# PCB_KioskMB_r3_3-05.net
KiCad netlist of a schematic drawn in EAGLE
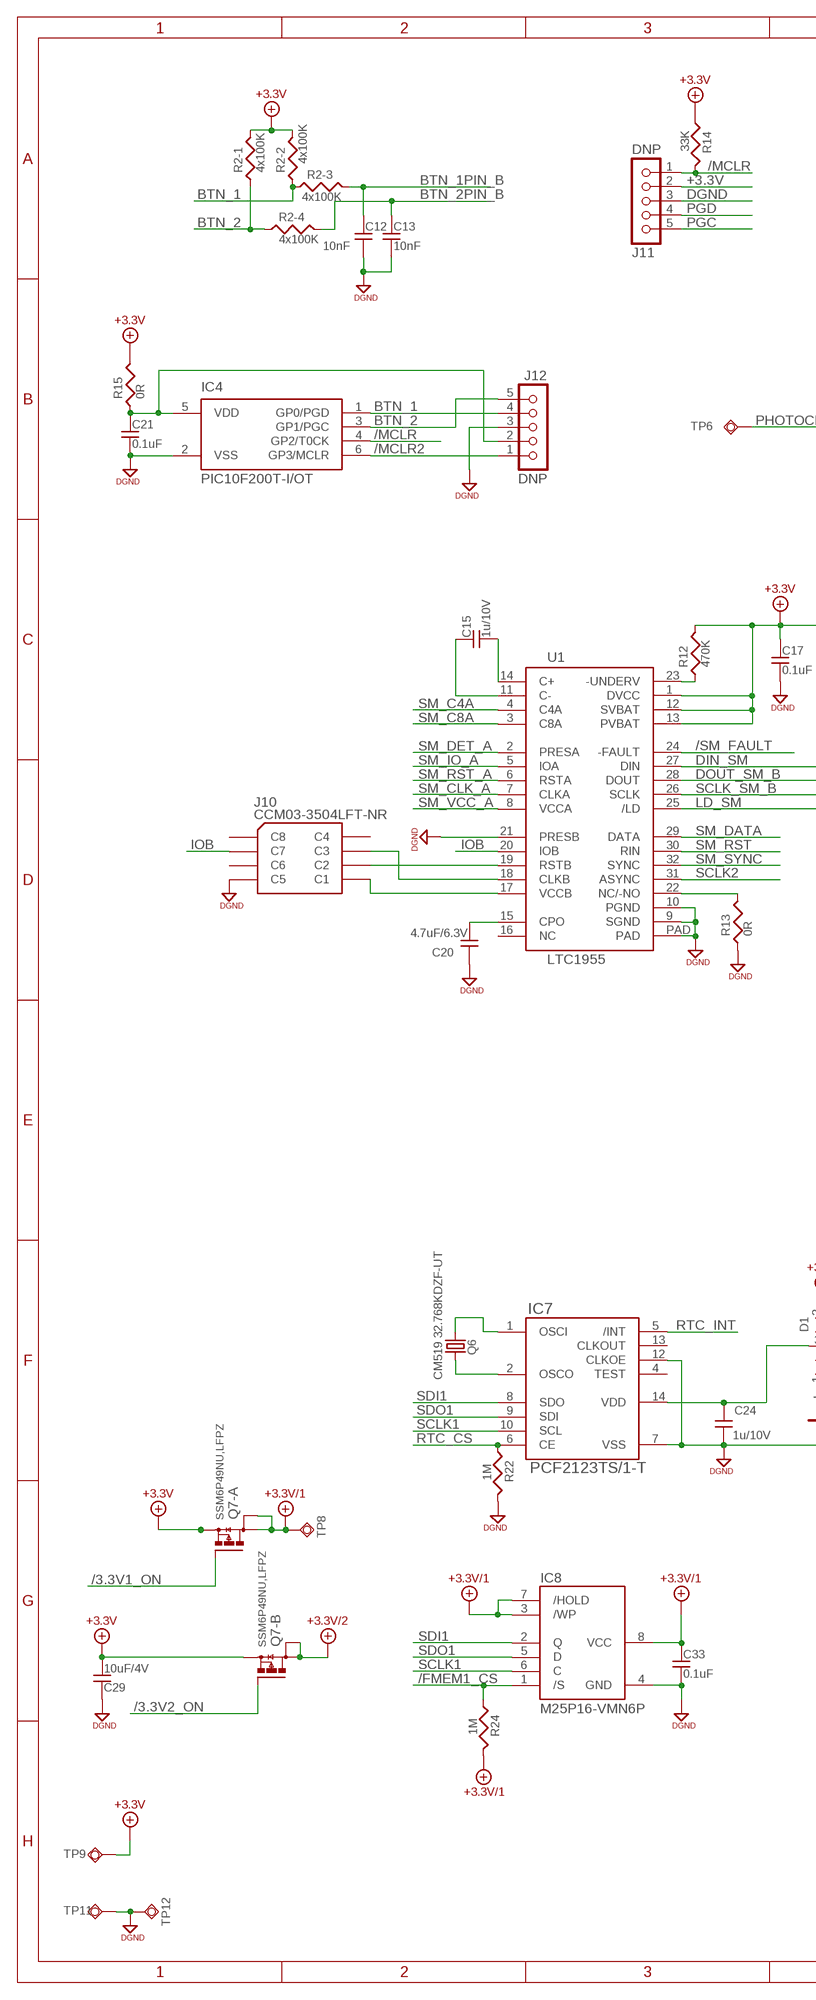
[diagram p0: schematic, sheet 1, part 1 of 2]
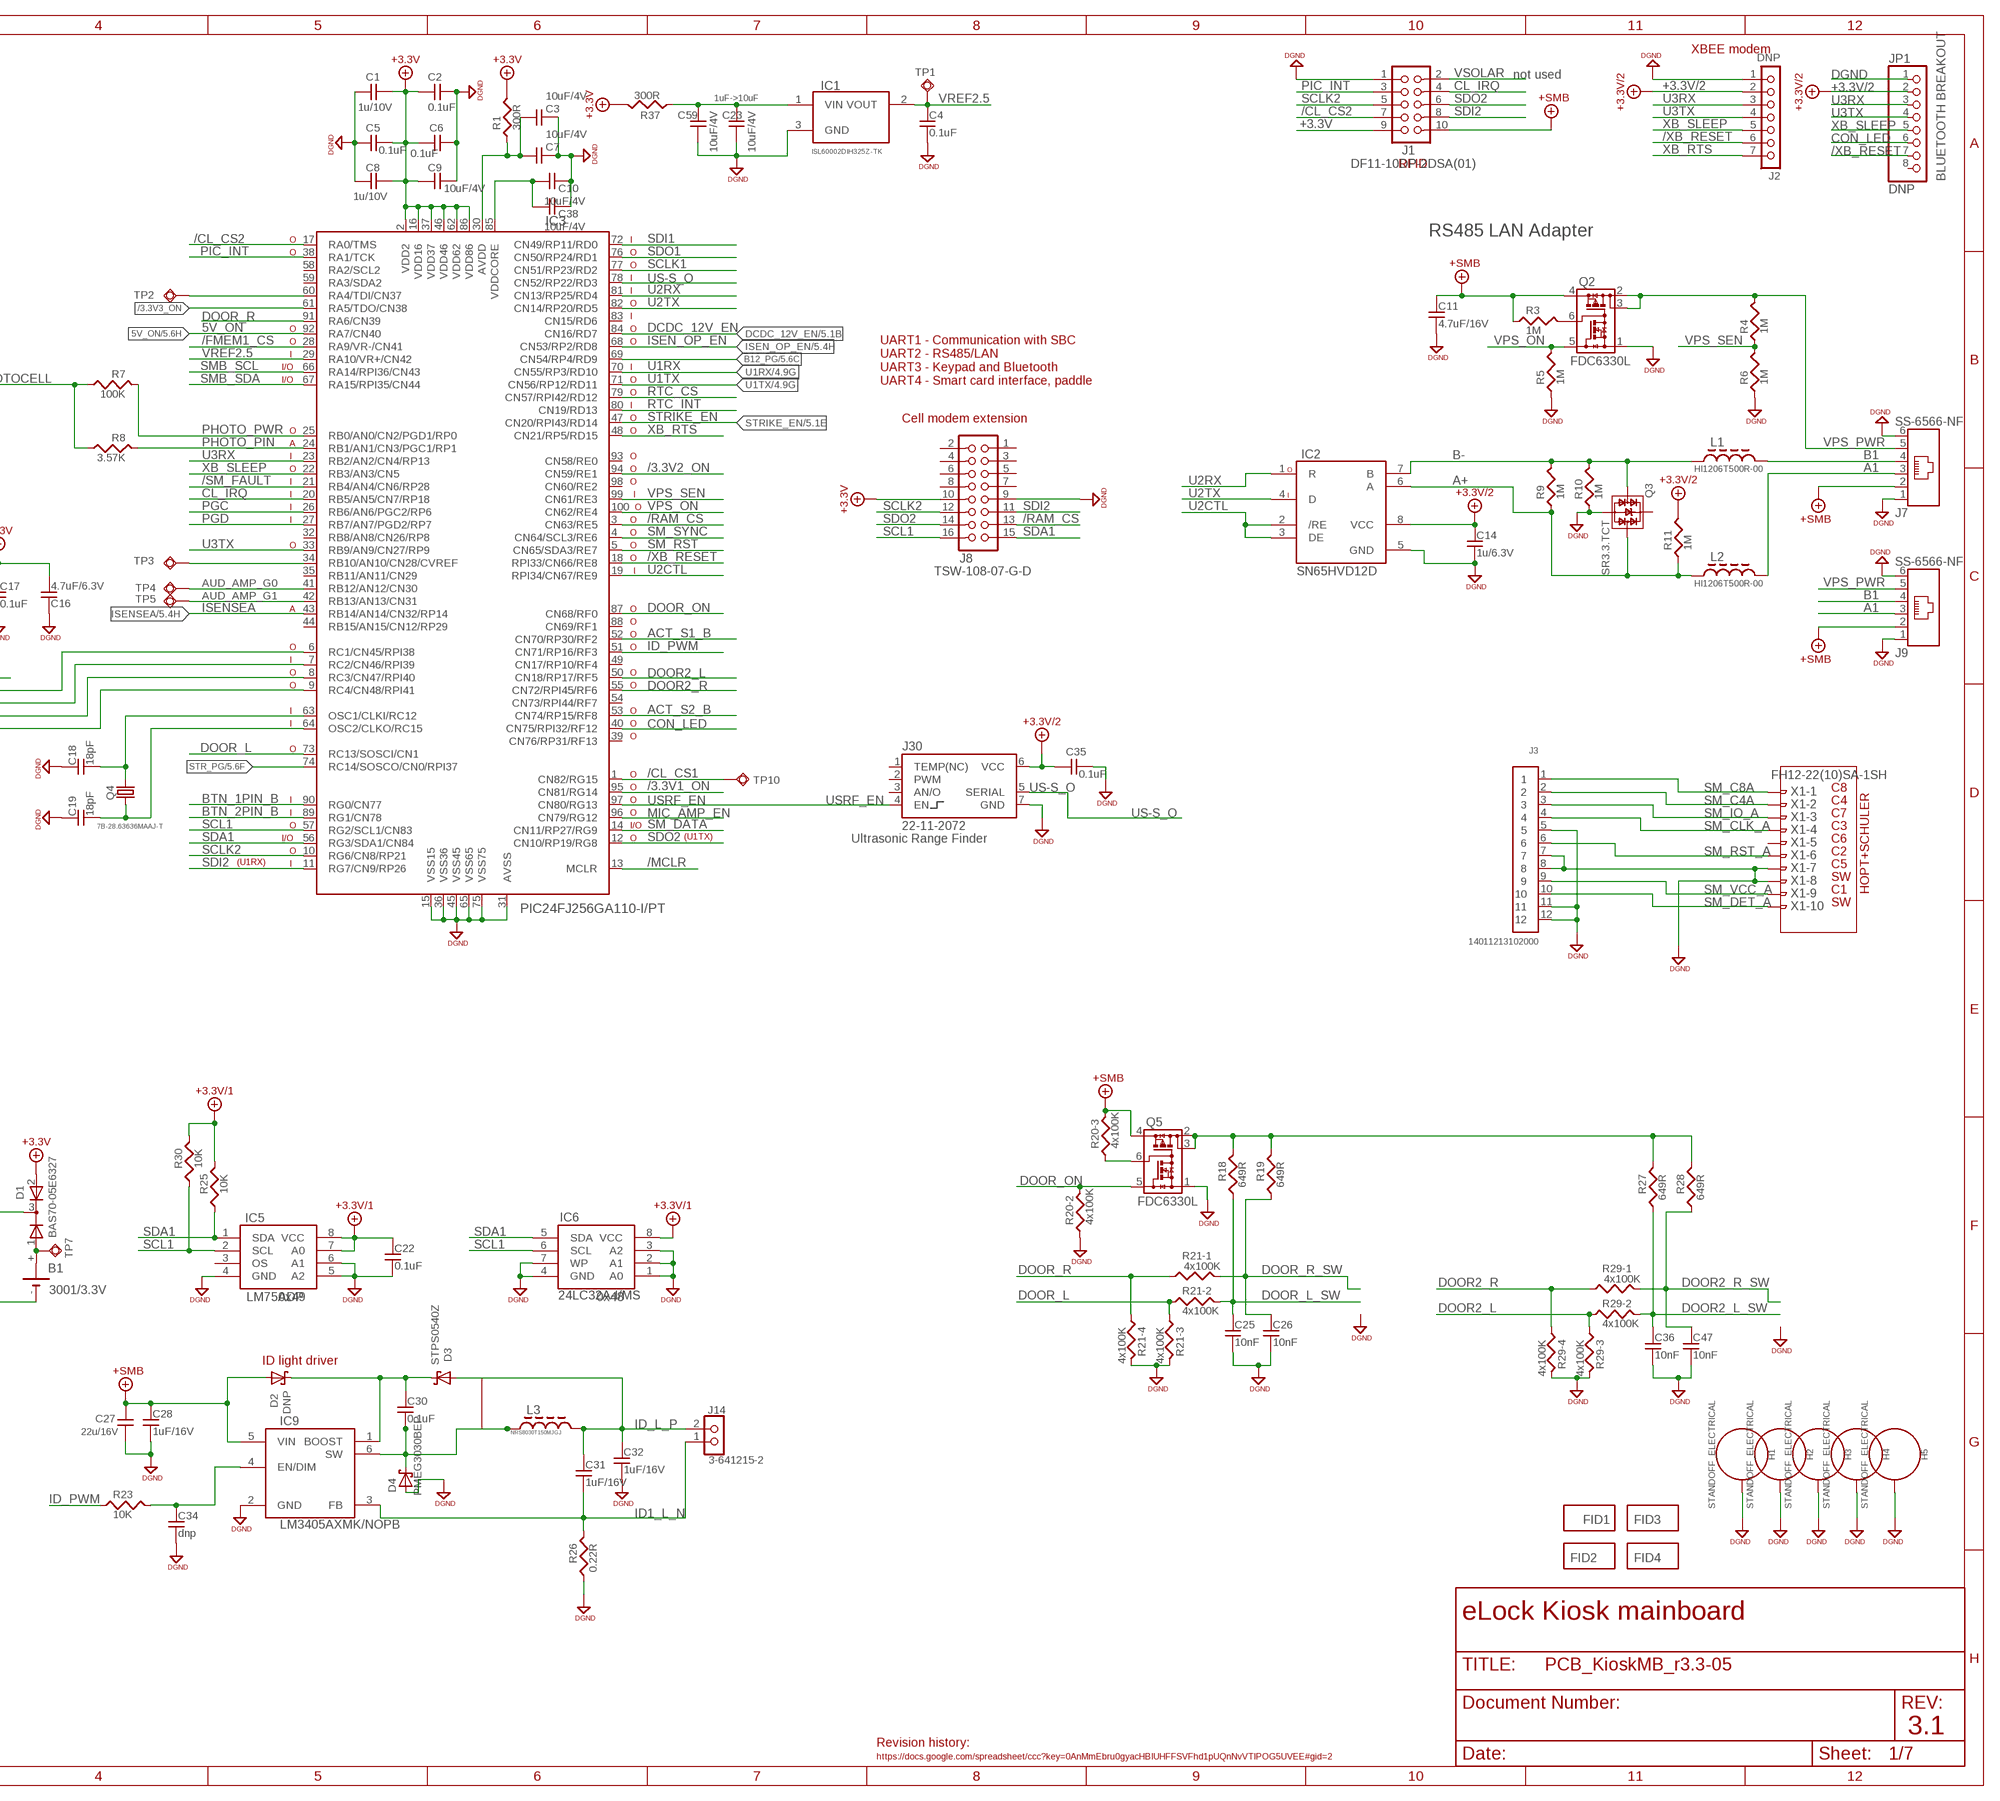
[diagram p1: schematic, sheet 1, part 2 of 2]
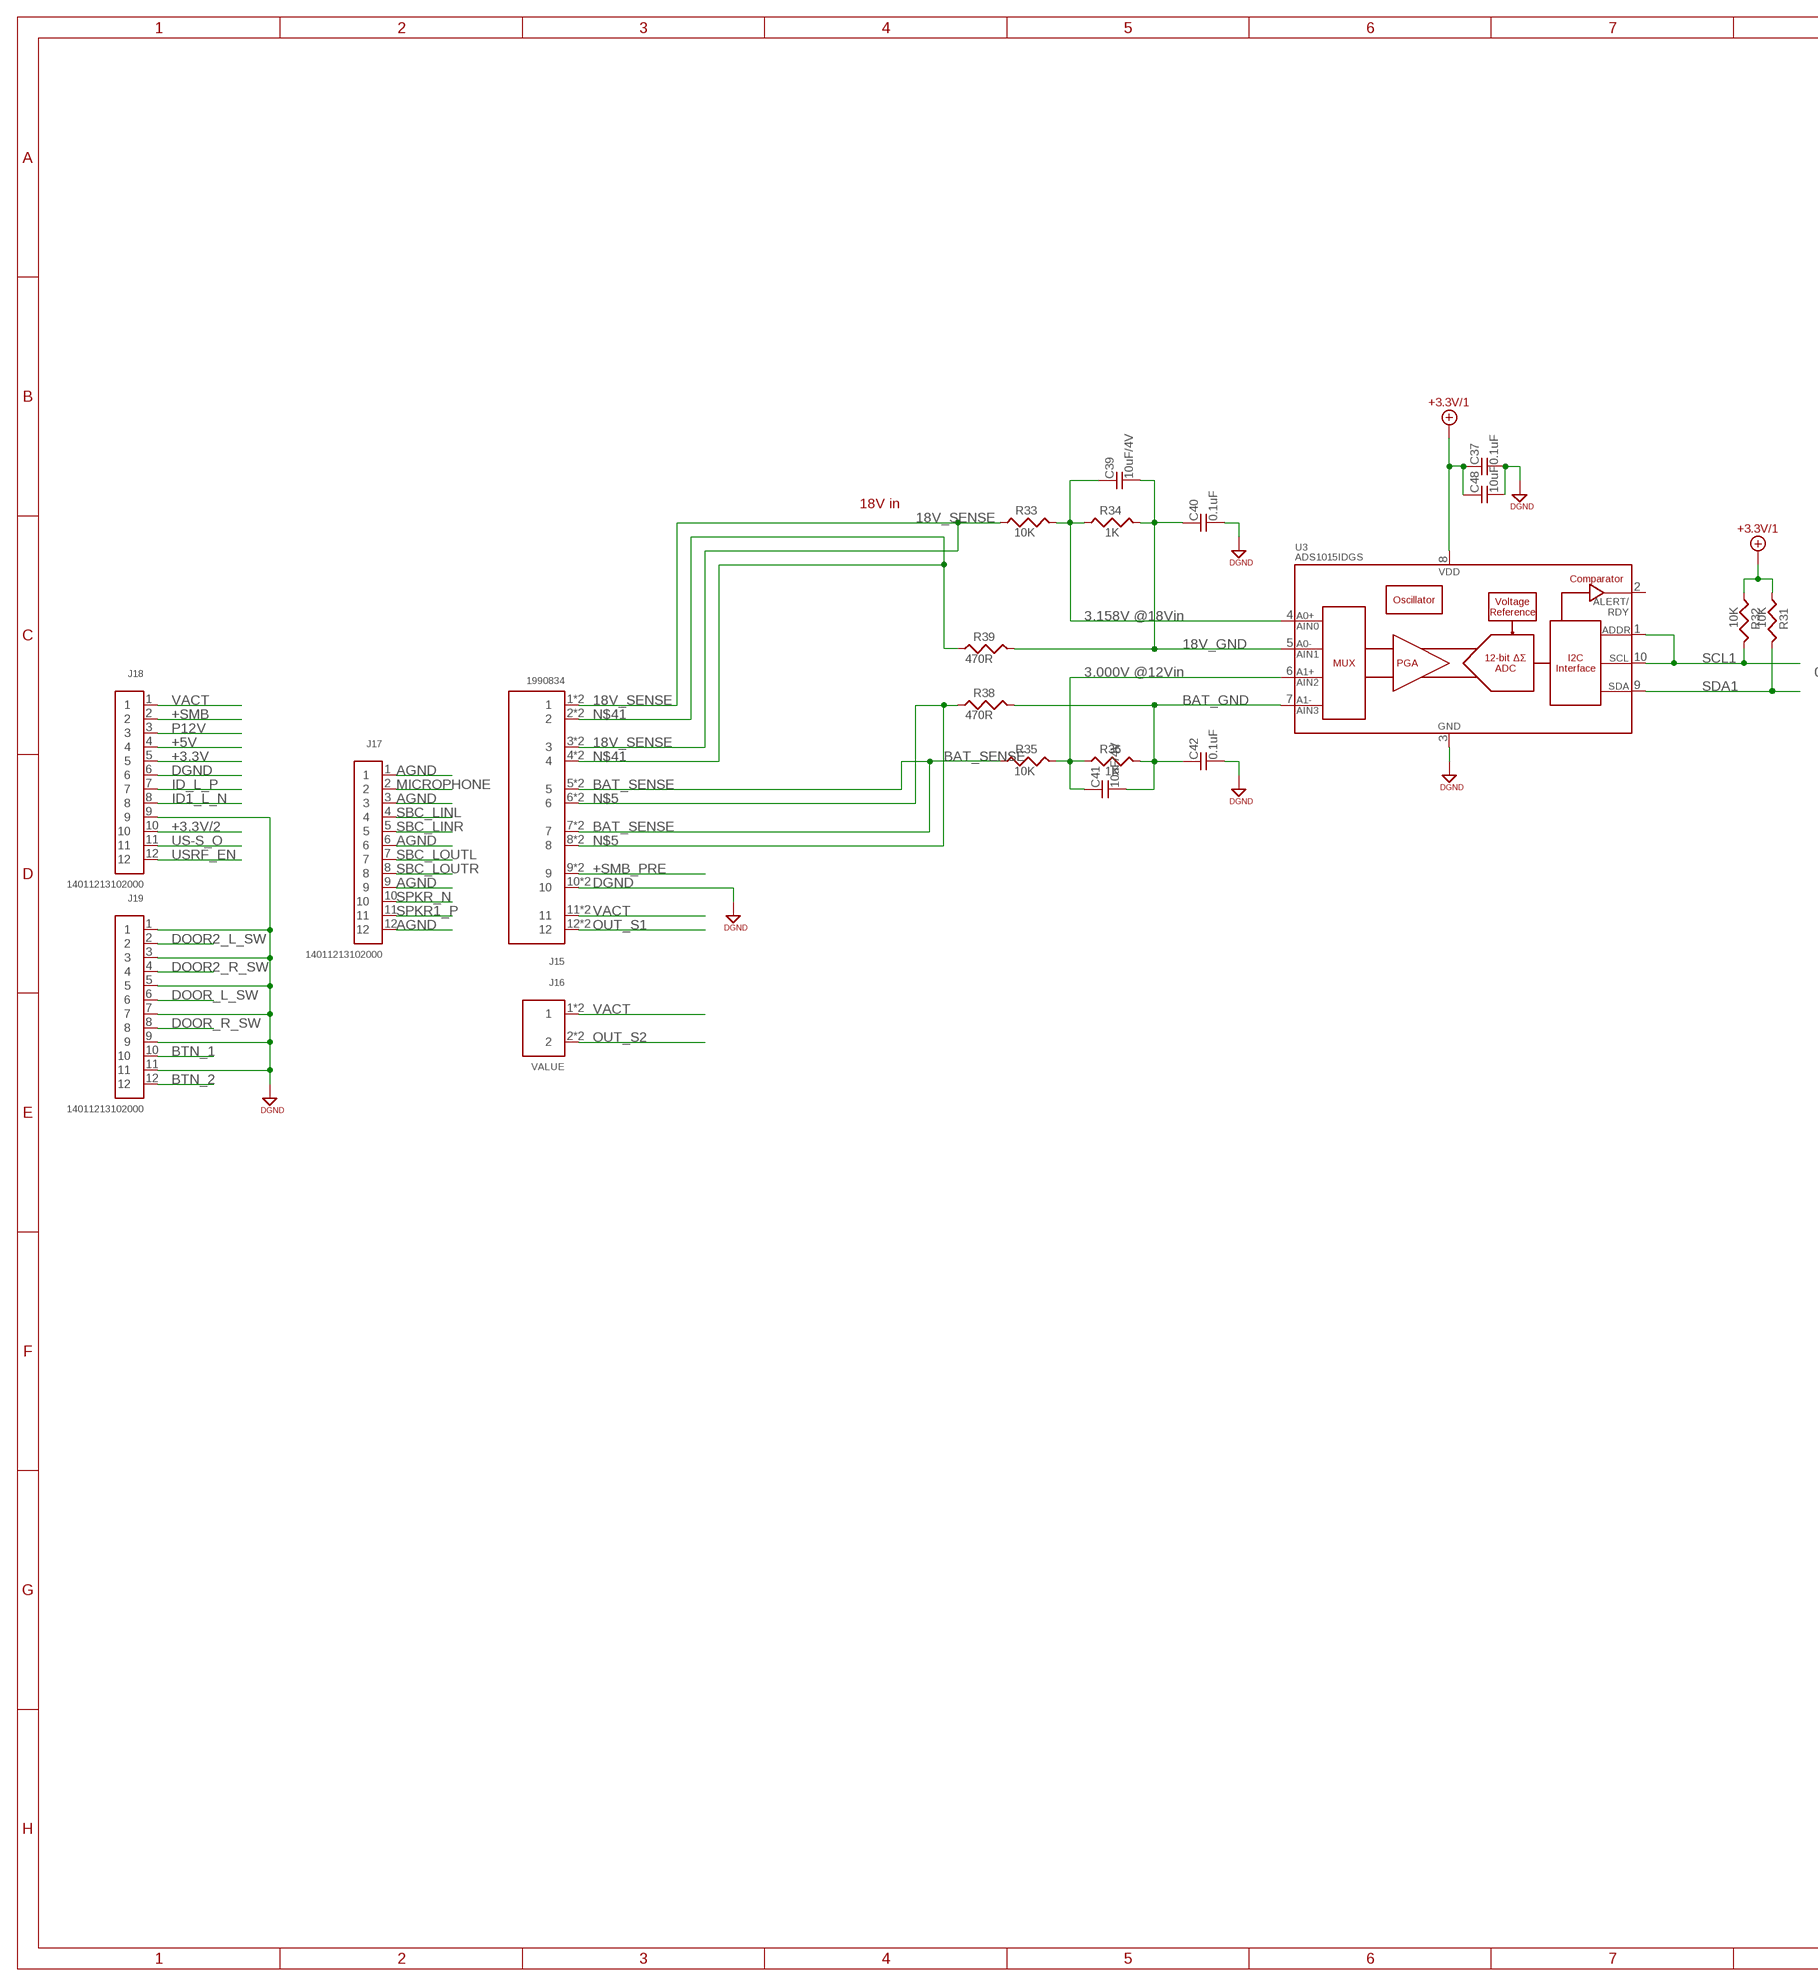
[diagram p2: schematic, sheet 2, part 1 of 2]
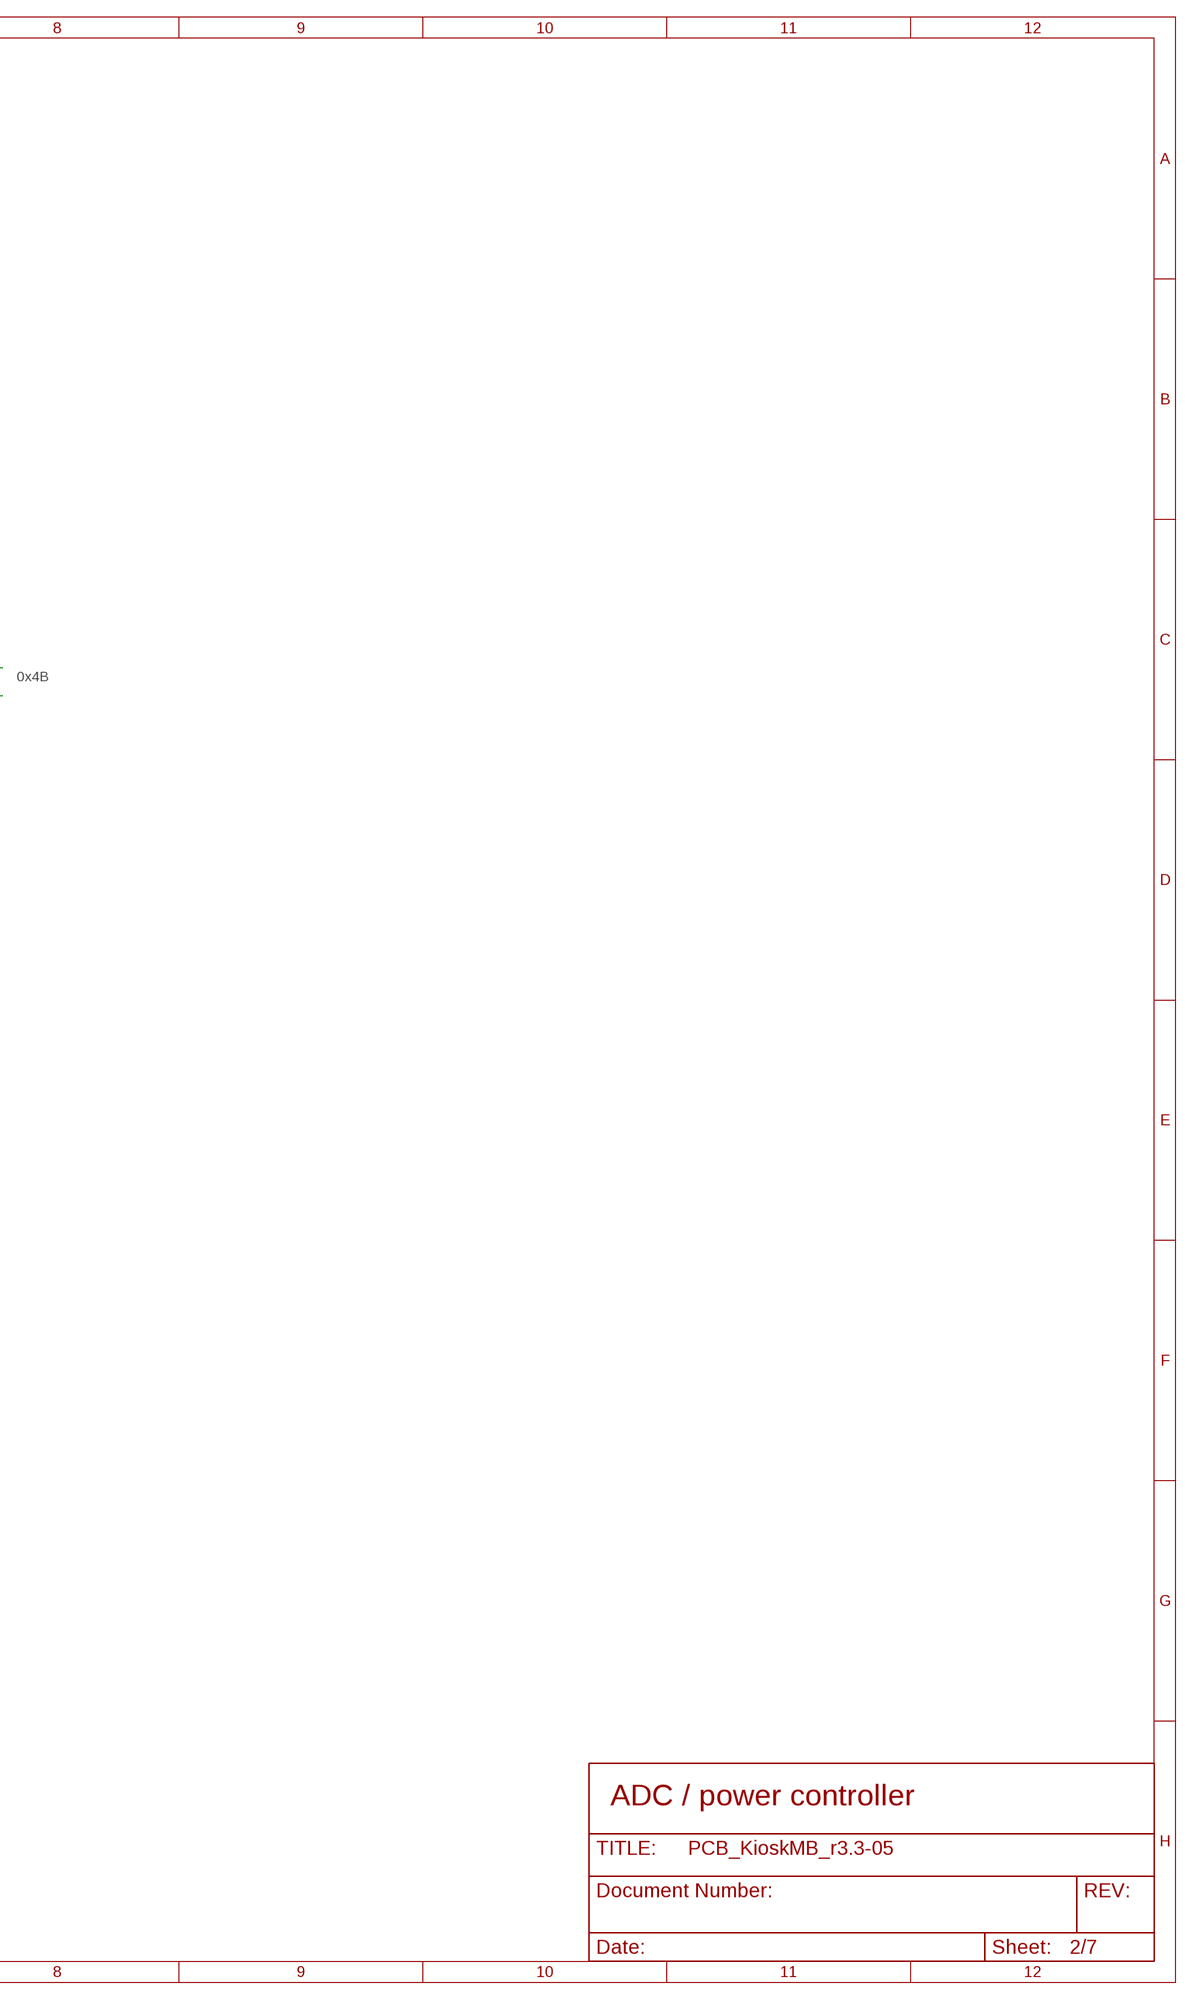
[diagram p3: schematic, sheet 2, part 2 of 2]
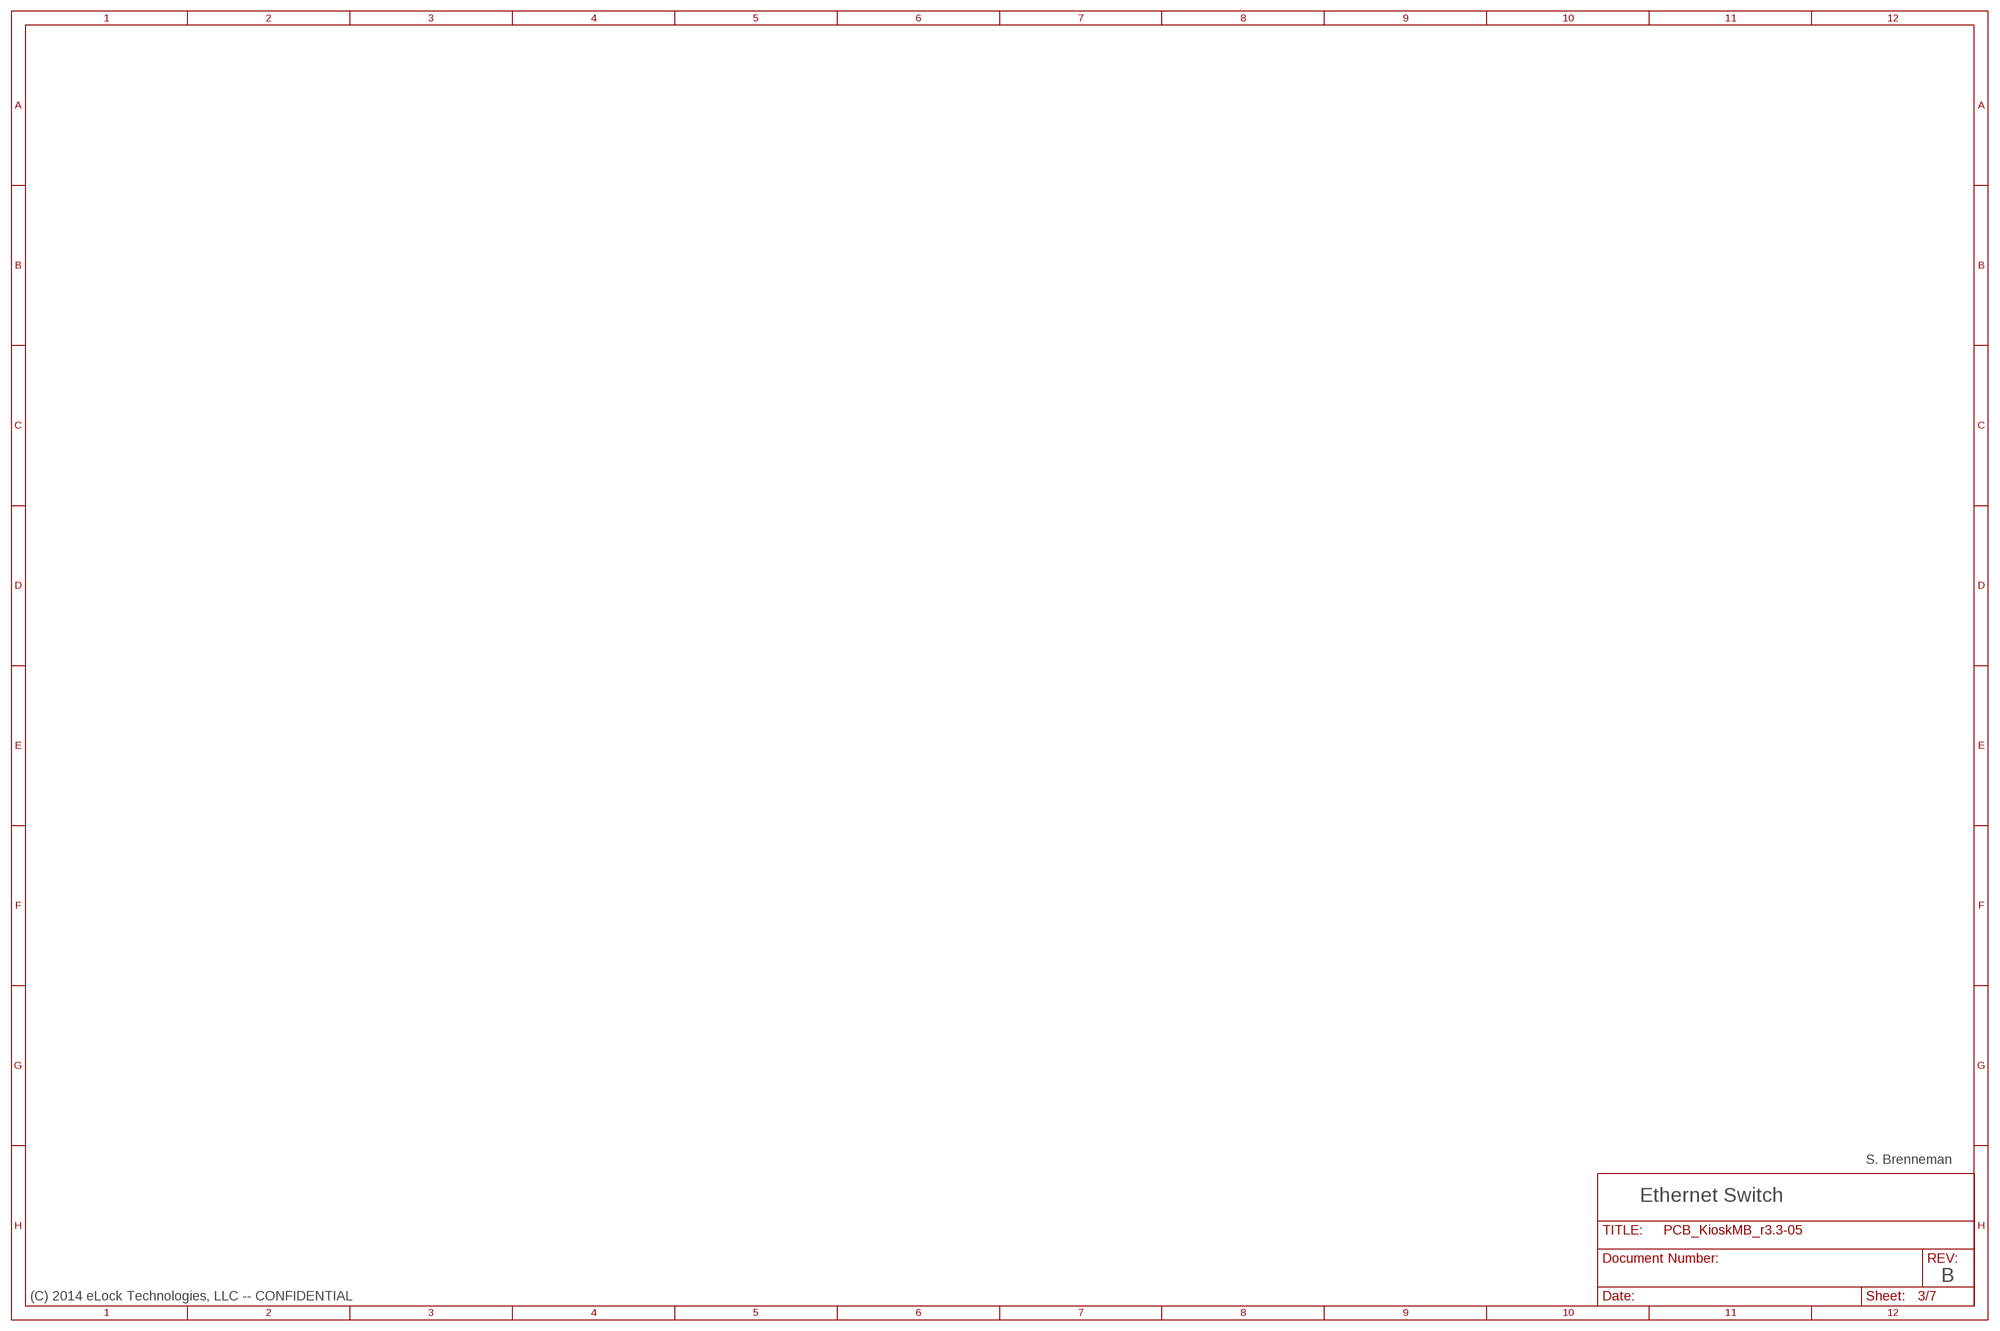
[diagram p4: schematic, sheet 3]
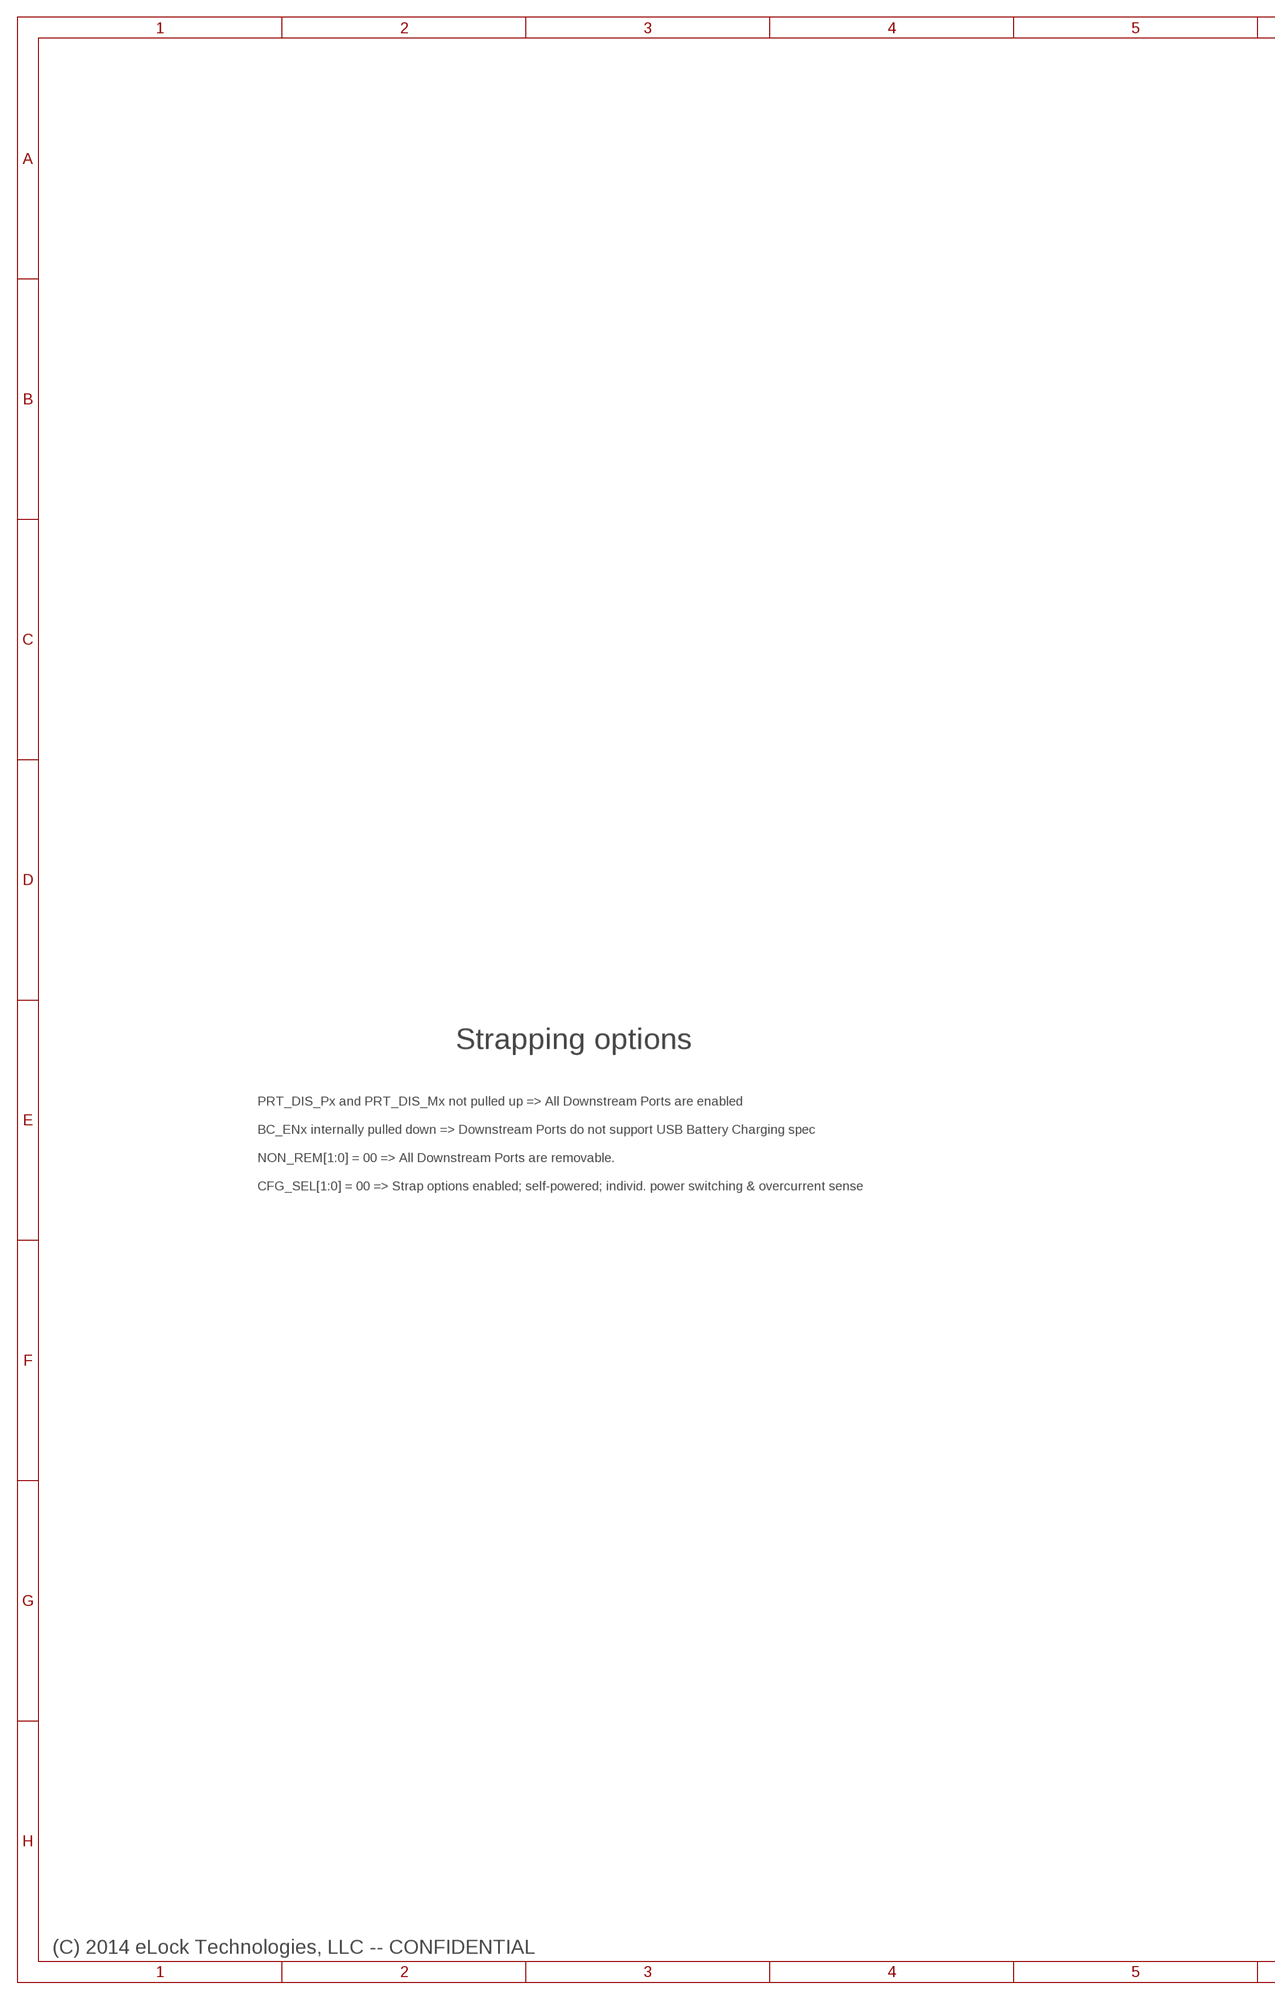
[diagram p5: schematic, sheet 4, part 1 of 2]
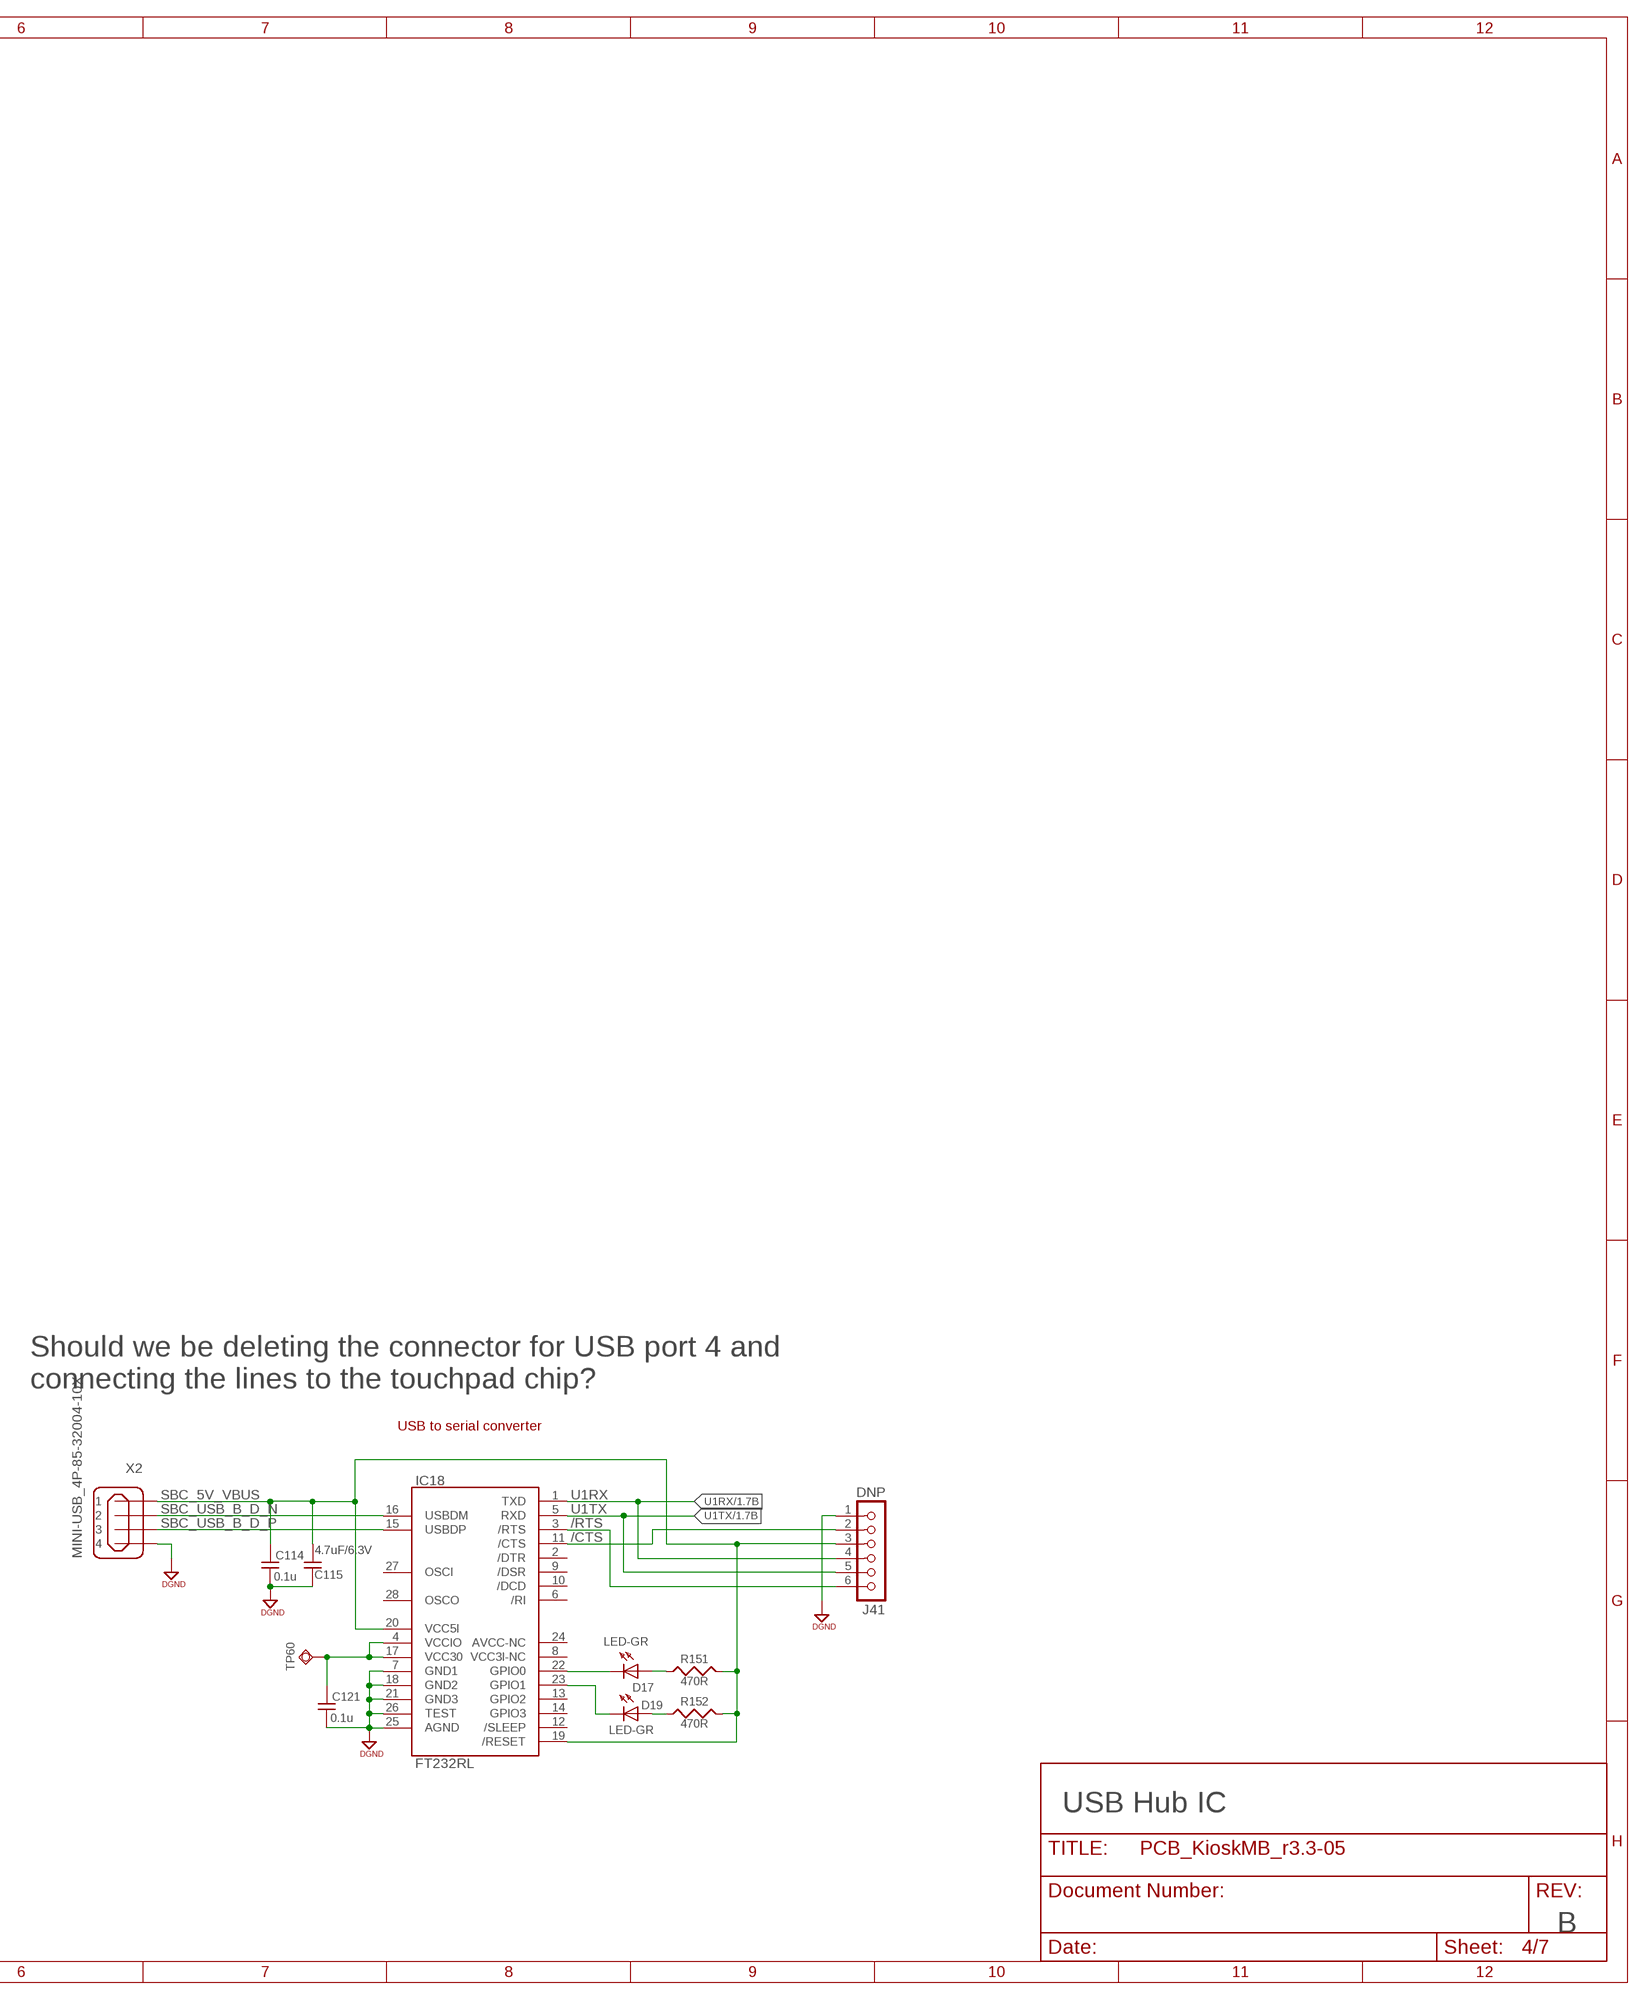
[diagram p6: schematic, sheet 4, part 2 of 2]
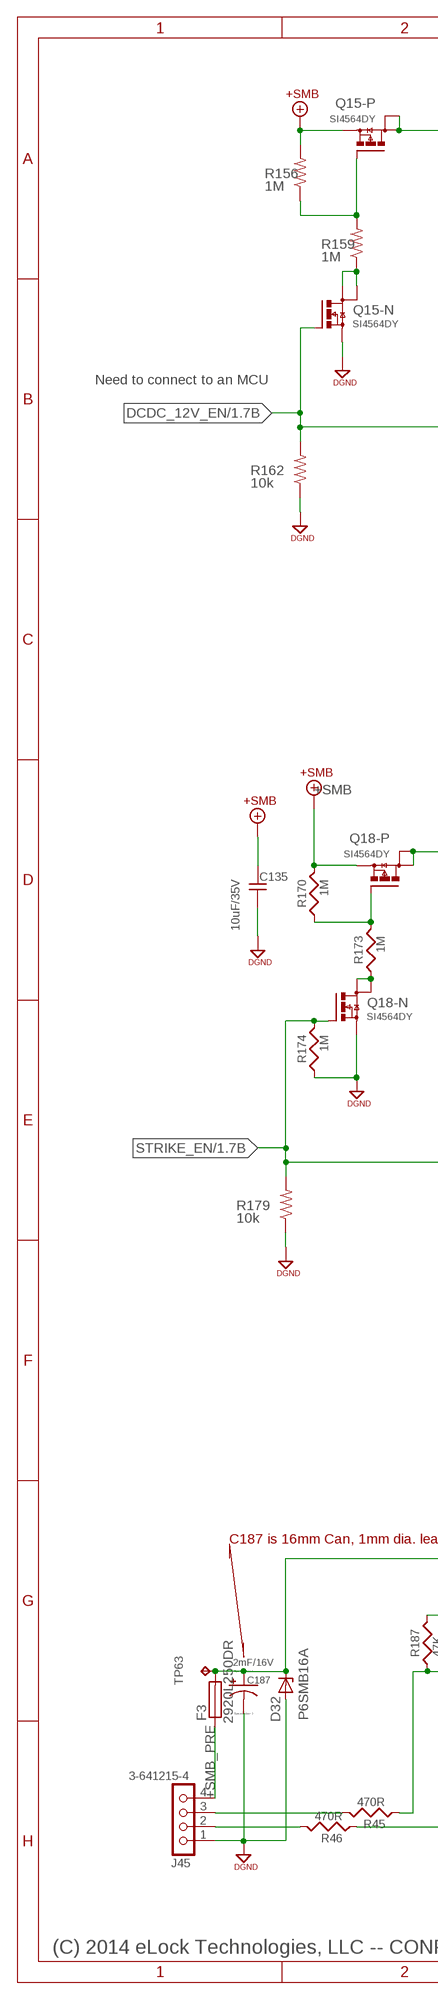
[diagram p7: schematic, sheet 5, part 1 of 2]
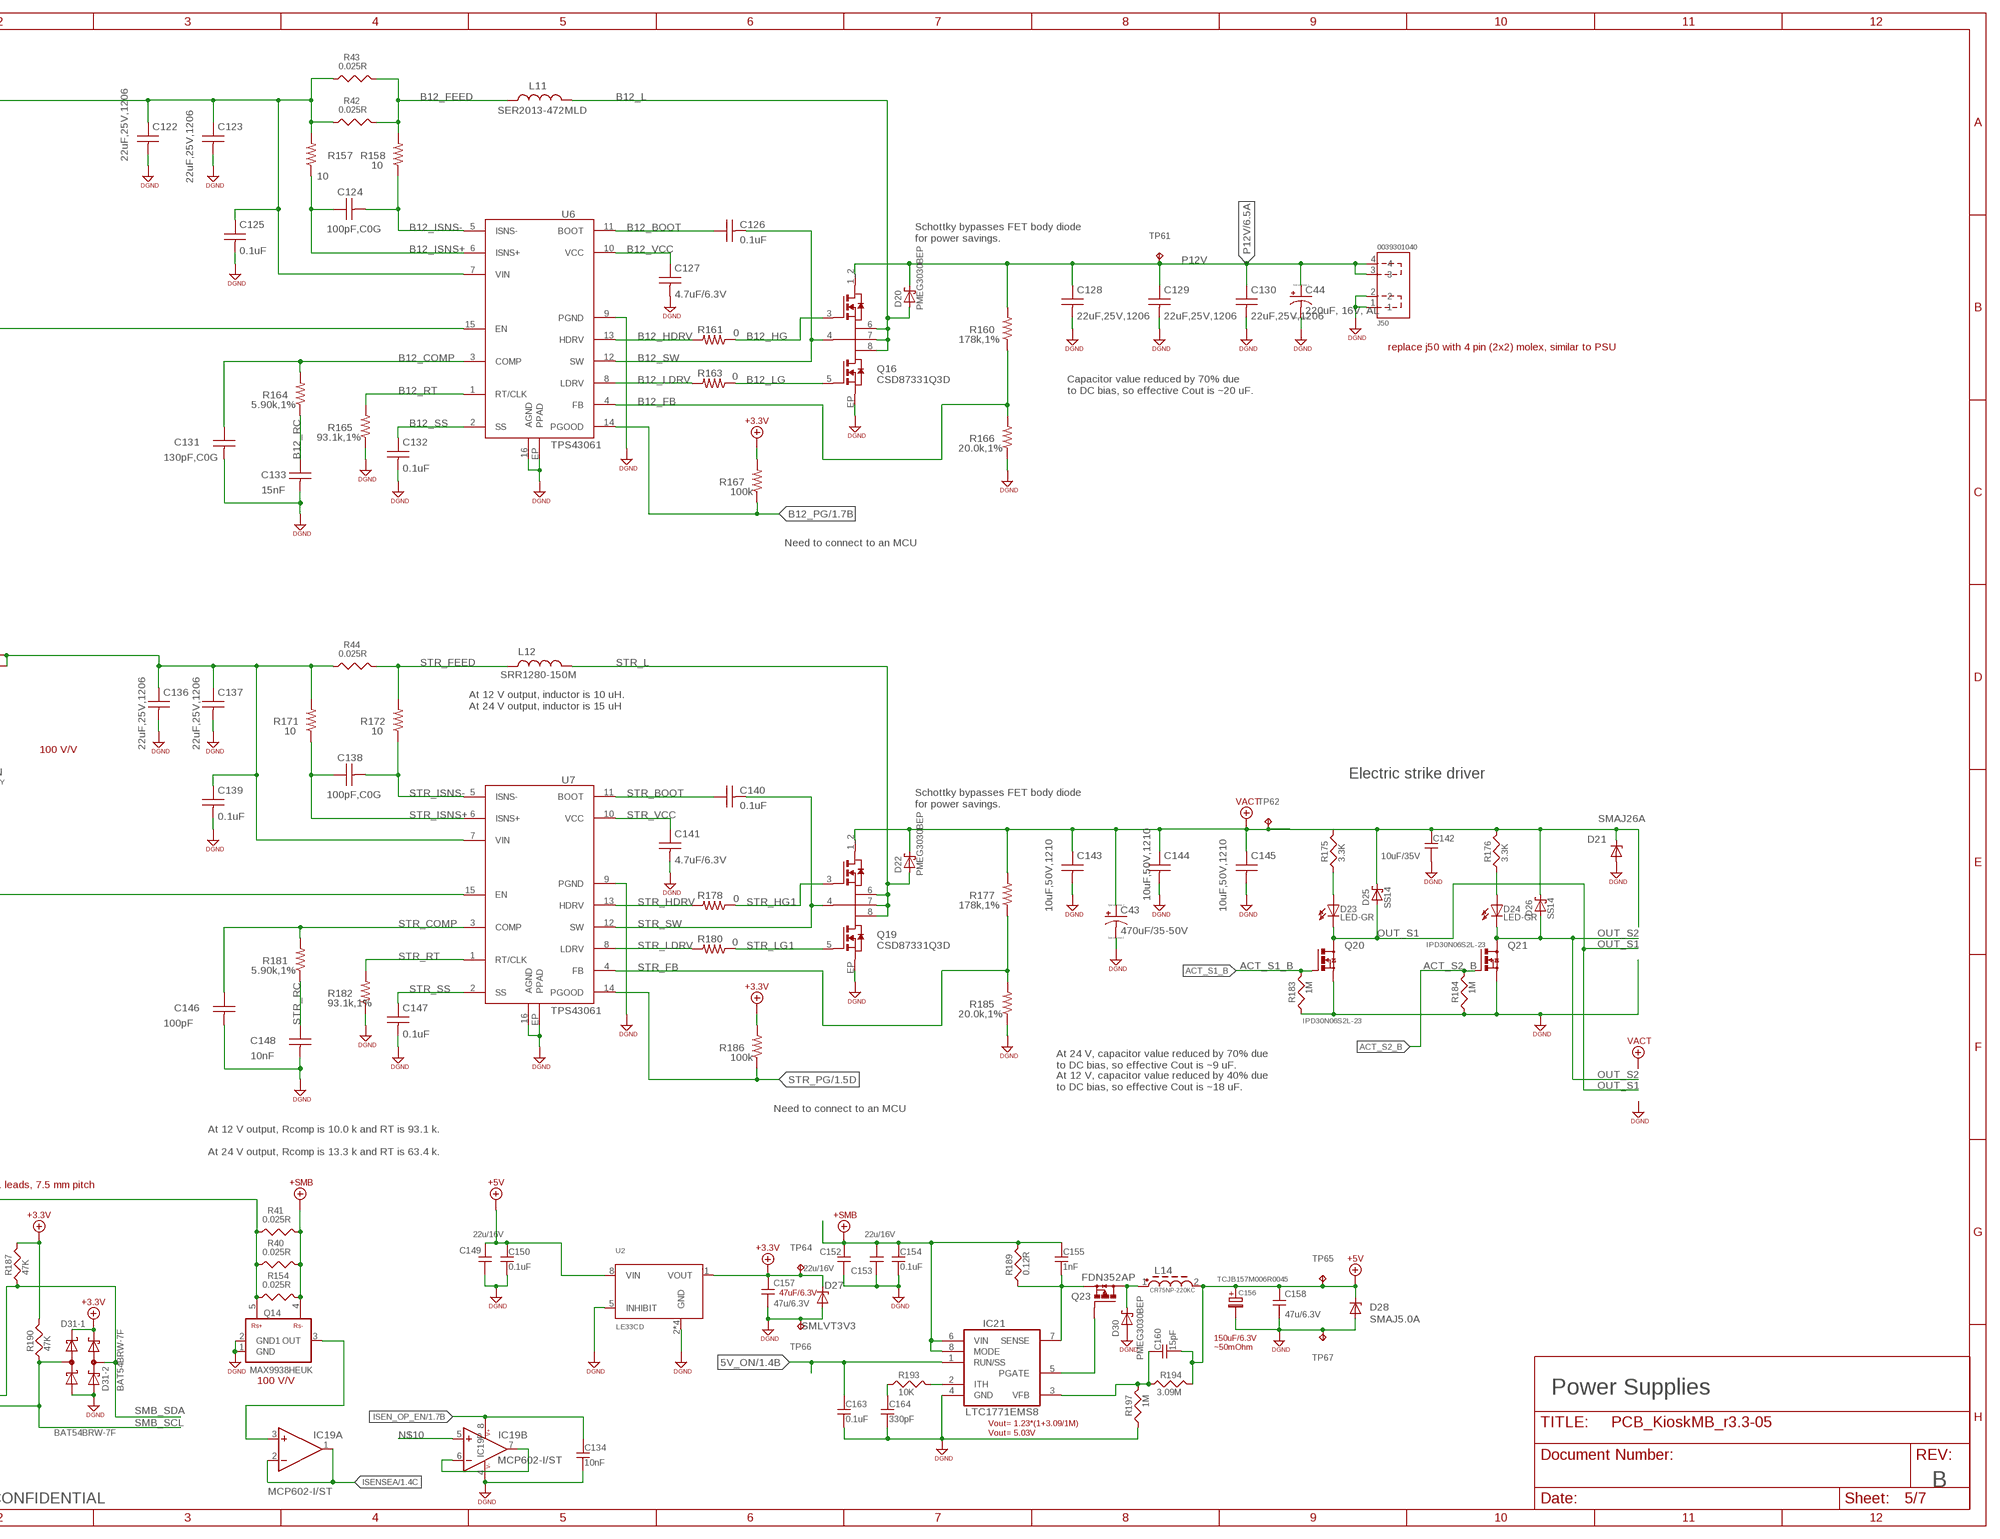
[diagram p8: schematic, sheet 5, part 2 of 2]
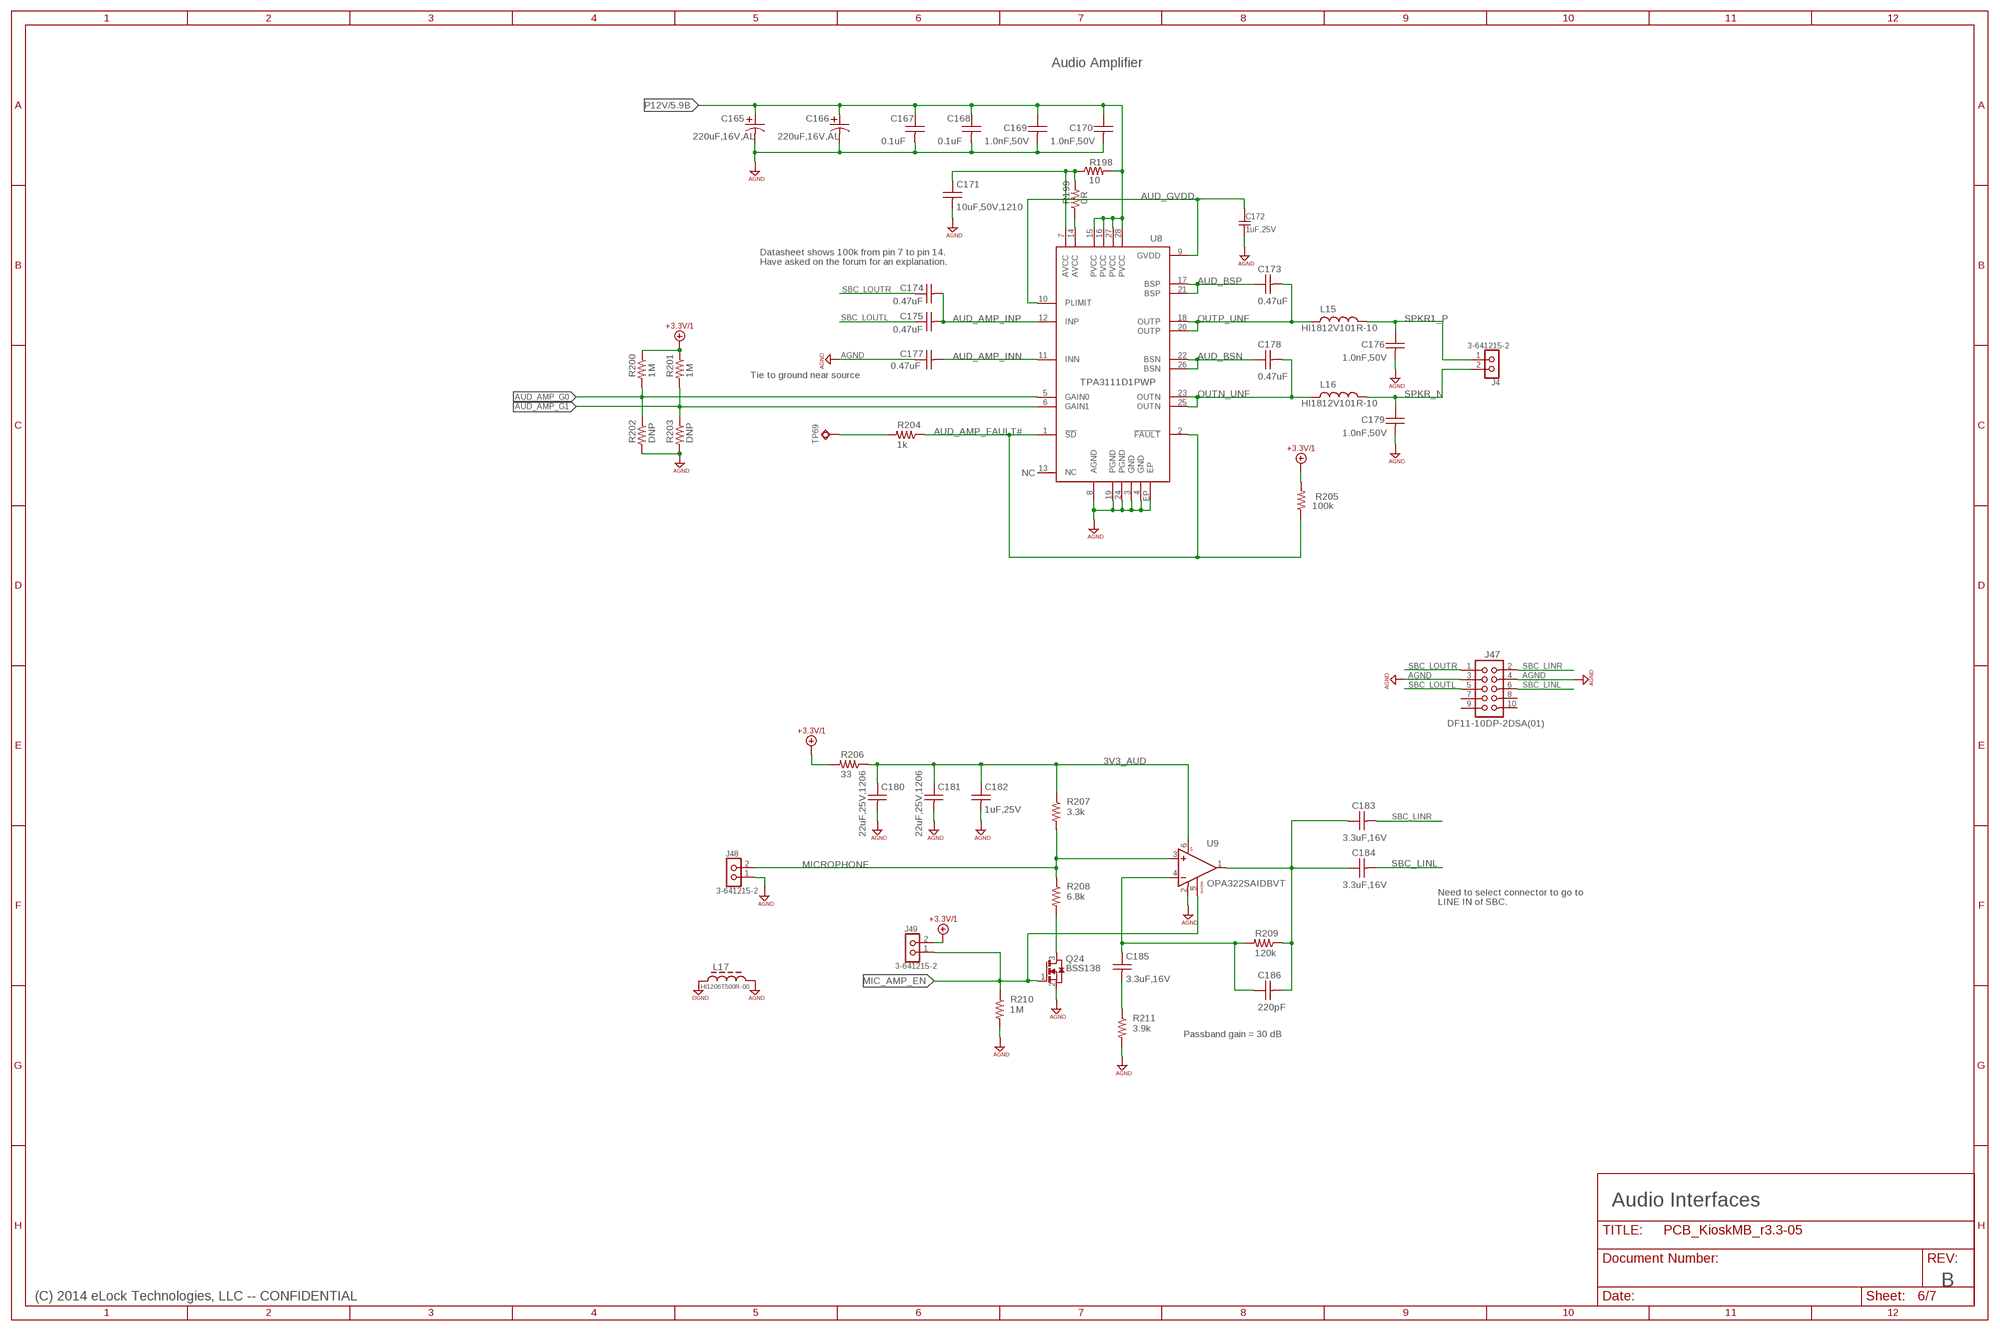
[diagram p9: schematic, sheet 6]
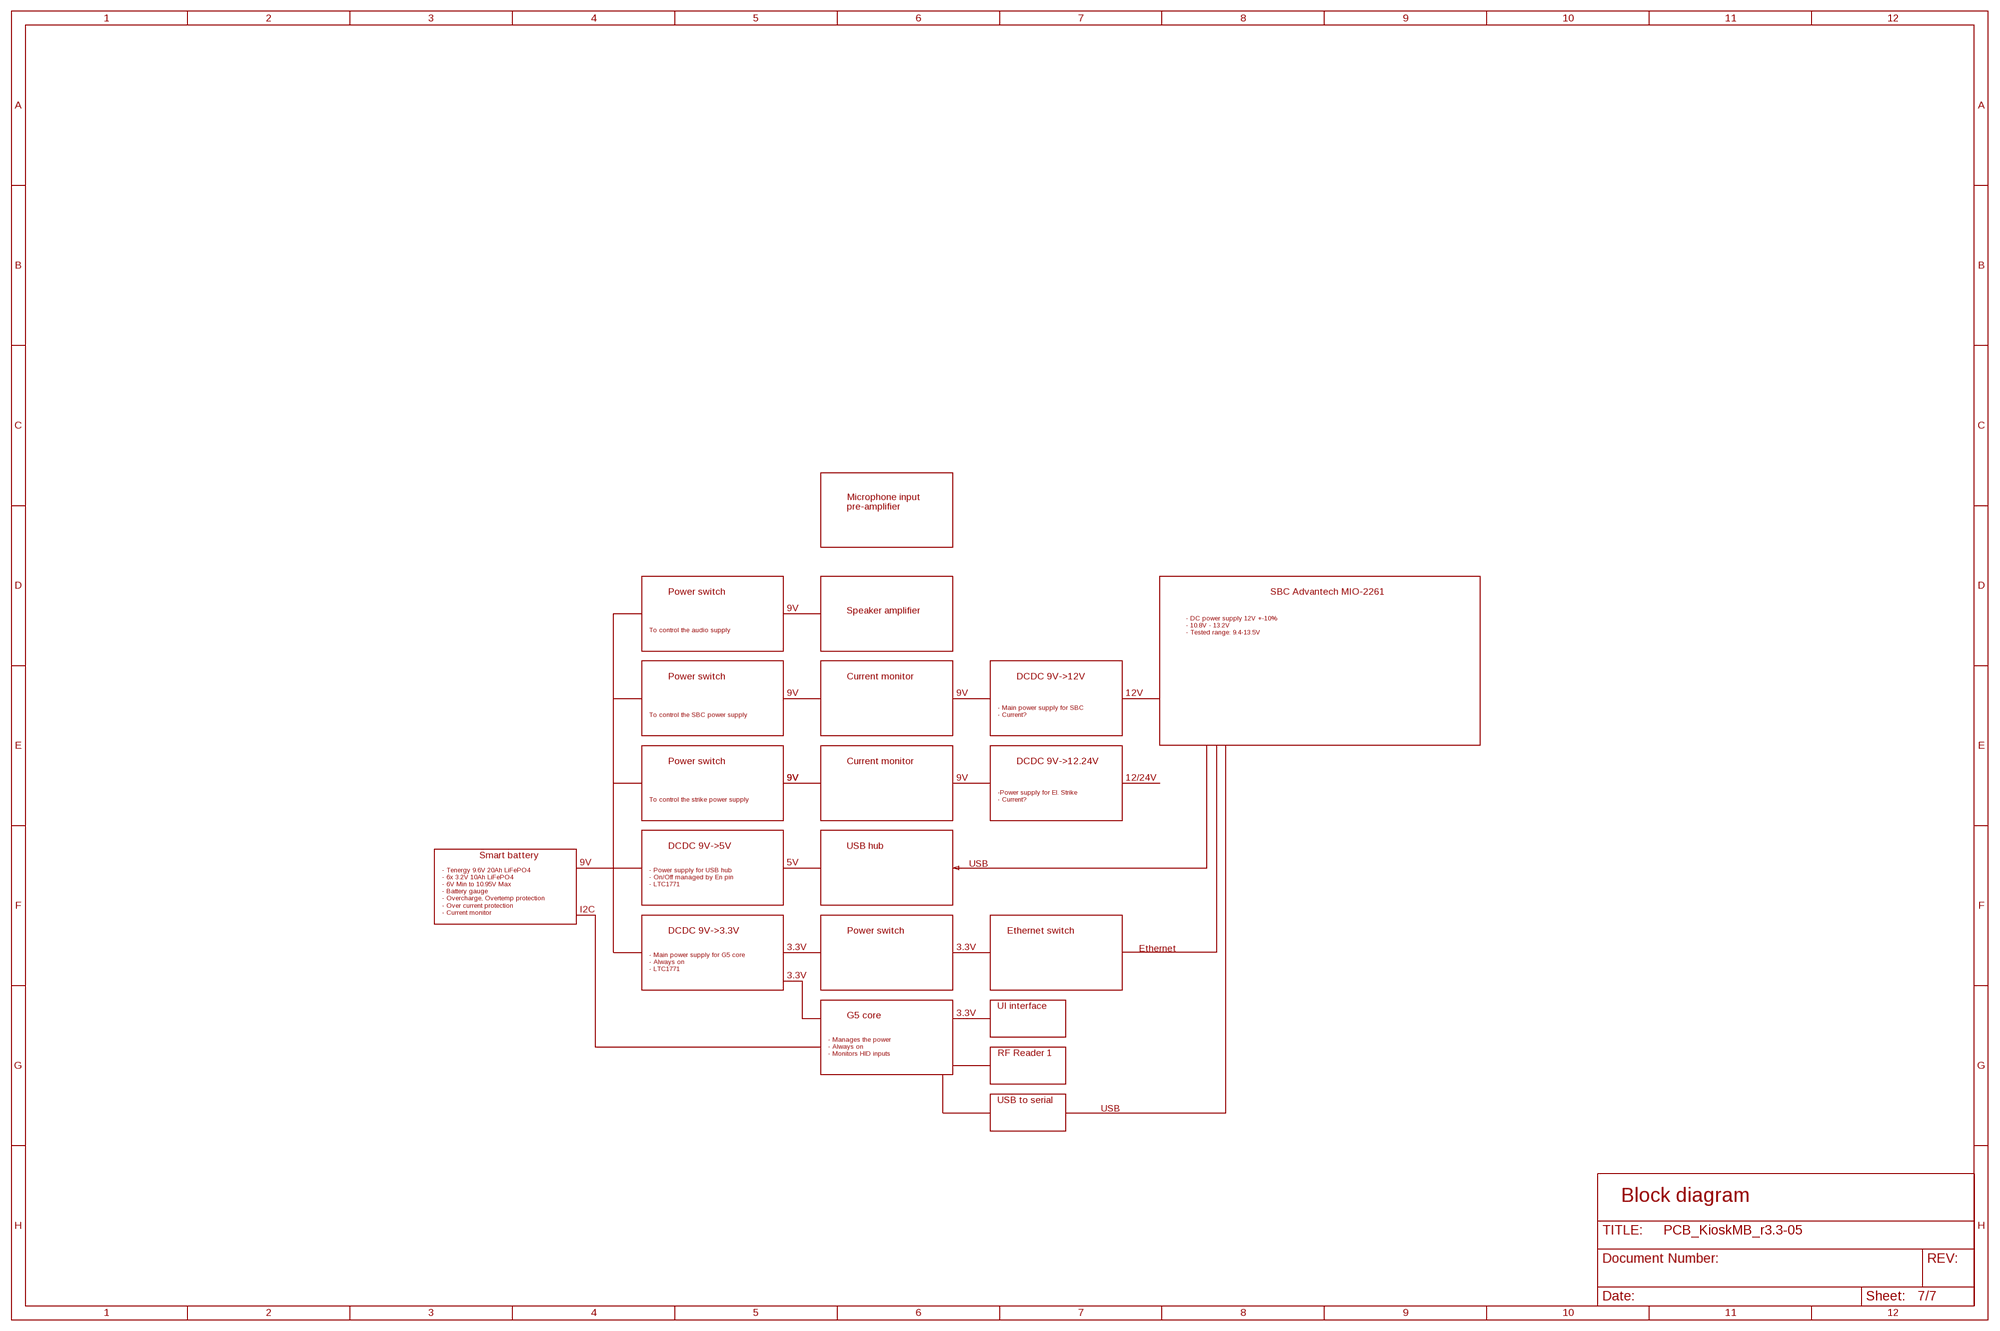
[diagram p10: schematic, sheet 7]

(export (version "E")
  (design (tool "Eeschema 10.0.6"))
  (components
    (comp (ref "C165")
      (value "220uF,16V,AL")
      (footprint "eagle-import:CAP_6.3MM_DIA_SMT")
      (fields (field (name "MANUFACTURER") "Kemet") (field (name "MFR_PN") "EEV227M016A9HAA"))
      (libsource (lib "eagle-import") (part "CAP_ELEC_6.3MM_SMD"))
    )
    (comp (ref "C166")
      (value "220uF,16V,AL")
      (footprint "eagle-import:CAP_6.3MM_DIA_SMT")
      (fields (field (name "MANUFACTURER") "Kemet") (field (name "MFR_PN") "EEV227M016A9HAA"))
      (libsource (lib "eagle-import") (part "CAP_ELEC_6.3MM_SMD"))
    )
    (comp (ref "C167")
      (value "0.1uF")
      (footprint "eagle-import:C0603")
      (libsource (lib "eagle-import") (part "C-US-NP0603"))
    )
    (comp (ref "C168")
      (value "0.1uF")
      (footprint "eagle-import:C0603")
      (libsource (lib "eagle-import") (part "C-US-NP0603"))
    )
    (comp (ref "C169")
      (value "1.0nF,50V")
      (footprint "eagle-import:C0603")
      (fields (field (name "MANUFACTURER") "Samsung"))
      (libsource (lib "eagle-import") (part "C-US-NP0603"))
    )
    (comp (ref "C170")
      (value "1.0nF,50V")
      (footprint "eagle-import:C0603")
      (fields (field (name "MANUFACTURER") "Samsung"))
      (libsource (lib "eagle-import") (part "C-US-NP0603"))
    )
    (comp (ref "C171")
      (value "10uF,50V,1210")
      (footprint "eagle-import:C1210")
      (fields (field (name "MANUFACTURER") "Samsung"))
      (libsource (lib "eagle-import") (part "C-US-NP1210"))
    )
    (comp (ref "C172")
      (value "1uF,25V")
      (footprint "eagle-import:0603")
      (libsource (lib "eagle-import") (part "C-0603"))
    )
    (comp (ref "C173")
      (value "0.47uF")
      (footprint "eagle-import:C0603")
      (fields (field (name "MANUFACTURER") "Taiyo Yuden"))
      (libsource (lib "eagle-import") (part "C-US-NP0603"))
    )
    (comp (ref "C174")
      (value "0.47uF")
      (footprint "eagle-import:C0603")
      (fields (field (name "MANUFACTURER") "Samsung"))
      (libsource (lib "eagle-import") (part "C-US-NP0603"))
    )
    (comp (ref "C175")
      (value "0.47uF")
      (footprint "eagle-import:C0603")
      (fields (field (name "MANUFACTURER") "Samsung"))
      (libsource (lib "eagle-import") (part "C-US-NP0603"))
    )
    (comp (ref "C176")
      (value "1.0nF,50V")
      (footprint "eagle-import:C0603")
      (fields (field (name "MANUFACTURER") "Samsung"))
      (libsource (lib "eagle-import") (part "C-US-NP0603"))
    )
    (comp (ref "C177")
      (value "0.47uF")
      (footprint "eagle-import:C0603")
      (fields (field (name "MANUFACTURER") "Samsung"))
      (libsource (lib "eagle-import") (part "C-US-NP0603"))
    )
    (comp (ref "C178")
      (value "0.47uF")
      (footprint "eagle-import:C0603")
      (fields (field (name "MANUFACTURER") "Taiyo Yuden"))
      (libsource (lib "eagle-import") (part "C-US-NP0603"))
    )
    (comp (ref "C179")
      (value "1.0nF,50V")
      (footprint "eagle-import:C0603")
      (fields (field (name "MANUFACTURER") "Samsung"))
      (libsource (lib "eagle-import") (part "C-US-NP0603"))
    )
    (comp (ref "C180")
      (value "22uF,25V,1206")
      (footprint "eagle-import:C1206")
      (fields (field (name "MANUFACTURER") "Samsung"))
      (libsource (lib "eagle-import") (part "C-US-NP1206"))
    )
    (comp (ref "C181")
      (value "22uF,25V,1206")
      (footprint "eagle-import:C1206")
      (fields (field (name "MANUFACTURER") "Samsung"))
      (libsource (lib "eagle-import") (part "C-US-NP1206"))
    )
    (comp (ref "C182")
      (value "1uF,25V")
      (footprint "eagle-import:C0603")
      (libsource (lib "eagle-import") (part "C-US-NP0603"))
    )
    (comp (ref "C183")
      (value "3.3uF,16V")
      (footprint "eagle-import:C0603")
      (libsource (lib "eagle-import") (part "C-US-NP0603"))
    )
    (comp (ref "C184")
      (value "3.3uF,16V")
      (footprint "eagle-import:C0603")
      (libsource (lib "eagle-import") (part "C-US-NP0603"))
    )
    (comp (ref "C185")
      (value "3.3uF,16V")
      (footprint "eagle-import:C0603")
      (libsource (lib "eagle-import") (part "C-US-NP0603"))
    )
    (comp (ref "C186")
      (value "220pF")
      (footprint "eagle-import:C0603")
      (libsource (lib "eagle-import") (part "C-US-NP0603"))
    )
    (comp (ref "J4")
      (value "3-641215-2")
      (footprint "eagle-import:3-641215-2")
      (libsource (lib "eagle-import") (part "3-641215-2"))
    )
    (comp (ref "J47")
      (value "DF11-10DP-2DSA(01)")
      (footprint "eagle-import:DF11-10DP-2DSA")
      (libsource (lib "eagle-import") (part "DF11-10DP-2DSA(01)"))
    )
    (comp (ref "J48")
      (value "3-641215-2")
      (footprint "eagle-import:3-641215-2")
      (libsource (lib "eagle-import") (part "3-641215-2"))
    )
    (comp (ref "J49")
      (value "3-641215-2")
      (footprint "eagle-import:3-641215-2")
      (libsource (lib "eagle-import") (part "3-641215-2"))
    )
    (comp (ref "L15")
      (value "HI1812V101R-10")
      (footprint "eagle-import:L1812")
      (fields (field (name "MANUFACTURER") "Laird") (field (name "MFR_PN") "HI1812V101R-10"))
      (libsource (lib "eagle-import") (part "L1812"))
    )
    (comp (ref "L16")
      (value "HI1812V101R-10")
      (footprint "eagle-import:L1812")
      (fields (field (name "MANUFACTURER") "Laird") (field (name "MFR_PN") "HI1812V101R-10"))
      (libsource (lib "eagle-import") (part "L1812"))
    )
    (comp (ref "L17")
      (value "HI1206T500R-00")
      (footprint "eagle-import:1206")
      (libsource (lib "eagle-import") (part "L-1206"))
    )
    (comp (ref "Q24")
      (value "BSS138")
      (footprint "eagle-import:SOT23")
      (libsource (lib "eagle-import") (part "BSS138"))
    )
    (comp (ref "R198")
      (value "10")
      (footprint "eagle-import:R0603")
      (fields (field (name "MANUFACTURER") "Rohm"))
      (libsource (lib "eagle-import") (part "R-US_R0603"))
    )
    (comp (ref "R199")
      (value "0R")
      (footprint "eagle-import:R0603")
      (fields (field (name "MANUFACTURER") "Rohm"))
      (libsource (lib "eagle-import") (part "R-US_R0603"))
    )
    (comp (ref "R200")
      (value "1M")
      (footprint "eagle-import:R0603")
      (libsource (lib "eagle-import") (part "R-US_R0603"))
    )
    (comp (ref "R201")
      (value "1M")
      (footprint "eagle-import:R0603")
      (libsource (lib "eagle-import") (part "R-US_R0603"))
    )
    (comp (ref "R202")
      (value "DNP")
      (footprint "eagle-import:R0603")
      (libsource (lib "eagle-import") (part "R-US_R0603"))
    )
    (comp (ref "R203")
      (value "DNP")
      (footprint "eagle-import:R0603")
      (libsource (lib "eagle-import") (part "R-US_R0603"))
    )
    (comp (ref "R204")
      (value "1k")
      (footprint "eagle-import:R0603")
      (libsource (lib "eagle-import") (part "R-US_R0603"))
    )
    (comp (ref "R205")
      (value "100k")
      (footprint "eagle-import:R0603")
      (libsource (lib "eagle-import") (part "R-US_R0603"))
    )
    (comp (ref "R206")
      (value "33")
      (footprint "eagle-import:R0603")
      (libsource (lib "eagle-import") (part "R-US_R0603"))
    )
    (comp (ref "R207")
      (value "3.3k")
      (footprint "eagle-import:R0603")
      (libsource (lib "eagle-import") (part "R-US_R0603"))
    )
    (comp (ref "R208")
      (value "6.8k")
      (footprint "eagle-import:R0603")
      (libsource (lib "eagle-import") (part "R-US_R0603"))
    )
    (comp (ref "R209")
      (value "120k")
      (footprint "eagle-import:R0603")
      (libsource (lib "eagle-import") (part "R-US_R0603"))
    )
    (comp (ref "R210")
      (value "1M")
      (footprint "eagle-import:R0603")
      (libsource (lib "eagle-import") (part "R-US_R0603"))
    )
    (comp (ref "R211")
      (value "3.9k")
      (footprint "eagle-import:R0603")
      (libsource (lib "eagle-import") (part "R-US_R0603"))
    )
    (comp (ref "TP69")
      (value "P1-13")
      (footprint "eagle-import:P1-13@1")
      (libsource (lib "eagle-import") (part "P1-13"))
    )
    (comp (ref "U8")
      (value "TPA3111D1PWP")
      (footprint "eagle-import:TSSOP28_EP")
      (fields (field (name "MANUFACTURER") "TI"))
      (libsource (lib "eagle-import") (part "IC_TI_TPA3111D1PWP"))
    )
    (comp (ref "U9")
      (value "OPA322SAIDBVT")
      (footprint "eagle-import:SOT23-6")
      (fields (field (name "MANUFACTURER") "TI"))
      (libsource (lib "eagle-import") (part "IC_TI_OPA322SDBVAI"))
    )
    (comp (ref "C37")
      (value "0.1uF")
      (footprint "eagle-import:0603")
      (libsource (lib "eagle-import") (part "C-0603"))
    )
    (comp (ref "C39")
      (value "10uF/4V")
      (footprint "eagle-import:0603")
      (libsource (lib "eagle-import") (part "C-0603"))
    )
    (comp (ref "C40")
      (value "0.1uF")
      (footprint "eagle-import:0603")
      (libsource (lib "eagle-import") (part "C-0603"))
    )
    (comp (ref "C41")
      (value "10uF/4V")
      (footprint "eagle-import:0603")
      (libsource (lib "eagle-import") (part "C-0603"))
    )
    (comp (ref "C42")
      (value "0.1uF")
      (footprint "eagle-import:0603")
      (libsource (lib "eagle-import") (part "C-0603"))
    )
    (comp (ref "C48")
      (value "10uF")
      (footprint "eagle-import:0603")
      (libsource (lib "eagle-import") (part "C-0603"))
    )
    (comp (ref "J15")
      (value "1990834")
      (footprint "eagle-import:1990834")
      (libsource (lib "eagle-import") (part "1990834"))
    )
    (comp (ref "J16")
      (value "1990737")
      (footprint "eagle-import:1990737")
      (libsource (lib "eagle-import") (part "1990737"))
    )
    (comp (ref "J17")
      (value "14011213102000")
      (footprint "eagle-import:14011213102000")
      (libsource (lib "eagle-import") (part "14011213102000"))
    )
    (comp (ref "J18")
      (value "14011213102000")
      (footprint "eagle-import:14011213102000")
      (libsource (lib "eagle-import") (part "14011213102000"))
    )
    (comp (ref "J19")
      (value "14011213102000")
      (footprint "eagle-import:14011213102000")
      (libsource (lib "eagle-import") (part "14011213102000"))
    )
    (comp (ref "R31")
      (value "10K")
      (footprint "eagle-import:0603")
      (libsource (lib "eagle-import") (part "R-0603"))
    )
    (comp (ref "R32")
      (value "10K")
      (footprint "eagle-import:0603")
      (libsource (lib "eagle-import") (part "R-0603"))
    )
    (comp (ref "R33")
      (value "10K")
      (footprint "eagle-import:0603")
      (libsource (lib "eagle-import") (part "R-0603"))
    )
    (comp (ref "R34")
      (value "1K")
      (footprint "eagle-import:0603")
      (libsource (lib "eagle-import") (part "R-0603"))
    )
    (comp (ref "R35")
      (value "10K")
      (footprint "eagle-import:0603")
      (libsource (lib "eagle-import") (part "R-0603"))
    )
    (comp (ref "R36")
      (value "1K")
      (footprint "eagle-import:0603")
      (libsource (lib "eagle-import") (part "R-0603"))
    )
    (comp (ref "R38")
      (value "470R")
      (footprint "eagle-import:0603")
      (libsource (lib "eagle-import") (part "R-0603"))
    )
    (comp (ref "R39")
      (value "470R")
      (footprint "eagle-import:0603")
      (libsource (lib "eagle-import") (part "R-0603"))
    )
    (comp (ref "U3")
      (value "ADS1015IDGS")
      (footprint "eagle-import:MSOP10")
      (libsource (lib "eagle-import") (part "ADS1015"))
    )
    (comp (ref "B1")
      (value "3001/3.3V")
      (footprint "eagle-import:3001")
      (libsource (lib "eagle-import") (part "3001"))
    )
    (comp (ref "C1")
      (value "1u/10V")
      (footprint "eagle-import:0603")
      (libsource (lib "eagle-import") (part "C-0603"))
    )
    (comp (ref "C2")
      (value "0.1uF")
      (footprint "eagle-import:0603")
      (libsource (lib "eagle-import") (part "C-0603"))
    )
    (comp (ref "C3")
      (value "10uF/4V")
      (footprint "eagle-import:0603")
      (libsource (lib "eagle-import") (part "C-0603"))
    )
    (comp (ref "C4")
      (value "0.1uF")
      (footprint "eagle-import:0603")
      (libsource (lib "eagle-import") (part "C-0603"))
    )
    (comp (ref "C5")
      (value "0.1uF")
      (footprint "eagle-import:0603")
      (libsource (lib "eagle-import") (part "C-0603"))
    )
    (comp (ref "C6")
      (value "0.1uF")
      (footprint "eagle-import:0603")
      (libsource (lib "eagle-import") (part "C-0603"))
    )
    (comp (ref "C7")
      (value "10uF/4V")
      (footprint "eagle-import:0603")
      (libsource (lib "eagle-import") (part "C-0603"))
    )
    (comp (ref "C8")
      (value "1u/10V")
      (footprint "eagle-import:0603")
      (libsource (lib "eagle-import") (part "C-0603"))
    )
    (comp (ref "C9")
      (value "10uF/4V")
      (footprint "eagle-import:0603")
      (libsource (lib "eagle-import") (part "C-0603"))
    )
    (comp (ref "C10")
      (value "10uF/4V")
      (footprint "eagle-import:0603")
      (libsource (lib "eagle-import") (part "C-0603"))
    )
    (comp (ref "C11")
      (value "4.7uF/16V")
      (footprint "eagle-import:0805")
      (libsource (lib "eagle-import") (part "C-0805"))
    )
    (comp (ref "C12")
      (value "10nF")
      (footprint "eagle-import:0603")
      (libsource (lib "eagle-import") (part "C-0603"))
    )
    (comp (ref "C13")
      (value "10nF")
      (footprint "eagle-import:0603")
      (libsource (lib "eagle-import") (part "C-0603"))
    )
    (comp (ref "C14")
      (value "1u/6.3V")
      (footprint "eagle-import:0603")
      (libsource (lib "eagle-import") (part "C-0603"))
    )
    (comp (ref "C15")
      (value "1u/10V")
      (footprint "eagle-import:0603")
      (libsource (lib "eagle-import") (part "C-0603"))
    )
    (comp (ref "C16")
      (value "4.7uF/6.3V")
      (footprint "eagle-import:0603")
      (libsource (lib "eagle-import") (part "C-0603"))
    )
    (comp (ref "C17")
      (value "0.1uF")
      (footprint "eagle-import:0603")
      (libsource (lib "eagle-import") (part "C-0603"))
    )
    (comp (ref "C18")
      (value "18pF")
      (footprint "eagle-import:0603")
      (libsource (lib "eagle-import") (part "C-0603"))
    )
    (comp (ref "C19")
      (value "18pF")
      (footprint "eagle-import:0603")
      (libsource (lib "eagle-import") (part "C-0603"))
    )
    (comp (ref "C20")
      (value "4.7uF/6.3V")
      (footprint "eagle-import:0603")
      (libsource (lib "eagle-import") (part "C-0603"))
    )
    (comp (ref "C21")
      (value "0.1uF")
      (footprint "eagle-import:0603")
      (libsource (lib "eagle-import") (part "C-0603"))
    )
    (comp (ref "C22")
      (value "0.1uF")
      (footprint "eagle-import:0603")
      (libsource (lib "eagle-import") (part "C-0603"))
    )
    (comp (ref "C23")
      (value "10uF/4V")
      (footprint "eagle-import:0603")
      (libsource (lib "eagle-import") (part "C-0603"))
    )
    (comp (ref "C24")
      (value "1u/10V")
      (footprint "eagle-import:0603")
      (libsource (lib "eagle-import") (part "C-0603"))
    )
    (comp (ref "C25")
      (value "10nF")
      (footprint "eagle-import:0603")
      (libsource (lib "eagle-import") (part "C-0603"))
    )
    (comp (ref "C26")
      (value "10nF")
      (footprint "eagle-import:0603")
      (libsource (lib "eagle-import") (part "C-0603"))
    )
    (comp (ref "C27")
      (value "22u/16V")
      (footprint "eagle-import:1210")
      (libsource (lib "eagle-import") (part "C-1210"))
    )
    (comp (ref "C28")
      (value "1uF/16V")
      (footprint "eagle-import:0603")
      (libsource (lib "eagle-import") (part "C-0603"))
    )
    (comp (ref "C29")
      (value "10uF/4V")
      (footprint "eagle-import:0603")
      (libsource (lib "eagle-import") (part "C-0603"))
    )
    (comp (ref "C30")
      (value "0.1uF")
      (footprint "eagle-import:0603")
      (libsource (lib "eagle-import") (part "C-0603"))
    )
    (comp (ref "C31")
      (value "1uF/16V")
      (footprint "eagle-import:0603")
      (libsource (lib "eagle-import") (part "C-0603"))
    )
    (comp (ref "C32")
      (value "1uF/16V")
      (footprint "eagle-import:0603")
      (libsource (lib "eagle-import") (part "C-0603"))
    )
    (comp (ref "C33")
      (value "0.1uF")
      (footprint "eagle-import:0603")
      (libsource (lib "eagle-import") (part "C-0603"))
    )
    (comp (ref "C34")
      (value "dnp")
      (footprint "eagle-import:0603")
      (libsource (lib "eagle-import") (part "C-0603"))
    )
    (comp (ref "C35")
      (value "0.1uF")
      (footprint "eagle-import:0603")
      (libsource (lib "eagle-import") (part "C-0603"))
    )
    (comp (ref "C36")
      (value "10nF")
      (footprint "eagle-import:0603")
      (libsource (lib "eagle-import") (part "C-0603"))
    )
    (comp (ref "C38")
      (value "10uF/4V")
      (footprint "eagle-import:0603")
      (libsource (lib "eagle-import") (part "C-0603"))
    )
    (comp (ref "C47")
      (value "10nF")
      (footprint "eagle-import:0603")
      (libsource (lib "eagle-import") (part "C-0603"))
    )
    (comp (ref "C59")
      (value "10uF/4V")
      (footprint "eagle-import:0603")
      (libsource (lib "eagle-import") (part "C-0603"))
    )
    (comp (ref "D1")
      (value "BAS70-05E6327")
      (footprint "eagle-import:SOT-23")
      (libsource (lib "eagle-import") (part "BAS70-05E6327"))
    )
    (comp (ref "D2")
      (value "DNP")
      (footprint "eagle-import:SOD-123")
      (libsource (lib "eagle-import") (part "STPS0540Z"))
    )
    (comp (ref "D3")
      (value "STPS0540Z")
      (footprint "eagle-import:SOD-123")
      (libsource (lib "eagle-import") (part "STPS0540Z"))
    )
    (comp (ref "D4")
      (value "PMEG3030BEP")
      (footprint "eagle-import:SOD-128")
      (libsource (lib "eagle-import") (part "PMEG3030BEP"))
    )
    (comp (ref "FID1")
      (value "REF")
      (footprint "eagle-import:REF")
      (libsource (lib "eagle-import") (part "REF"))
    )
    (comp (ref "FID2")
      (value "REF")
      (footprint "eagle-import:REF")
      (libsource (lib "eagle-import") (part "REF"))
    )
    (comp (ref "FID3")
      (value "REF")
      (footprint "eagle-import:REF")
      (libsource (lib "eagle-import") (part "REF"))
    )
    (comp (ref "FID4")
      (value "REF")
      (footprint "eagle-import:REF")
      (libsource (lib "eagle-import") (part "REF"))
    )
    (comp (ref "H1")
      (value "STANDOFF_ELECTRICAL")
      (footprint "eagle-import:STANDOFF-ELECTRICAL")
      (libsource (lib "eagle-import") (part "STANDOFF_ELECTRICAL"))
    )
    (comp (ref "H2")
      (value "STANDOFF_ELECTRICAL")
      (footprint "eagle-import:STANDOFF-ELECTRICAL")
      (libsource (lib "eagle-import") (part "STANDOFF_ELECTRICAL"))
    )
    (comp (ref "H3")
      (value "STANDOFF_ELECTRICAL")
      (footprint "eagle-import:STANDOFF-ELECTRICAL")
      (libsource (lib "eagle-import") (part "STANDOFF_ELECTRICAL"))
    )
    (comp (ref "H4")
      (value "STANDOFF_ELECTRICAL")
      (footprint "eagle-import:STANDOFF-ELECTRICAL")
      (libsource (lib "eagle-import") (part "STANDOFF_ELECTRICAL"))
    )
    (comp (ref "H5")
      (value "STANDOFF_ELECTRICAL")
      (footprint "eagle-import:STANDOFF-ELECTRICAL")
      (libsource (lib "eagle-import") (part "STANDOFF_ELECTRICAL"))
    )
    (comp (ref "IC1")
      (value "ISL60002DIH325Z-TK")
      (footprint "eagle-import:SOT-23")
      (libsource (lib "eagle-import") (part "ISL60002DIH325Z-TK"))
    )
    (comp (ref "IC2")
      (value "SN65HVD12D")
      (footprint "eagle-import:SO08")
      (libsource (lib "eagle-import") (part "SN65HVD3082ED"))
    )
    (comp (ref "IC3")
      (value "PIC24FJ256GA110-I/PT")
      (footprint "eagle-import:SQFP-S-12X12-100")
      (libsource (lib "eagle-import") (part "PIC24FJ256GA110-I/PT"))
    )
    (comp (ref "IC4")
      (value "PIC10F200T-I/OT")
      (footprint "eagle-import:SOT23-6")
      (libsource (lib "eagle-import") (part "PIC10F200T-I/OT"))
    )
    (comp (ref "IC5")
      (value "LM75ADP")
      (footprint "eagle-import:TSSOP08-3")
      (libsource (lib "eagle-import") (part "LM75ADP"))
    )
    (comp (ref "IC6")
      (value "24LC32A-I/MS")
      (footprint "eagle-import:MSOP-08")
      (libsource (lib "eagle-import") (part "24-I/MS"))
    )
    (comp (ref "IC7")
      (value "PCF2123TS/1-T")
      (footprint "eagle-import:TSSOP014")
      (libsource (lib "eagle-import") (part "PCF2123TS/1-T"))
    )
    (comp (ref "IC8")
      (value "M25P16-VMN6P")
      (footprint "eagle-import:SO-08")
      (libsource (lib "eagle-import") (part "M25P16-VMN6P"))
    )
    (comp (ref "IC9")
      (value "LM3405AXMK/NOPB")
      (footprint "eagle-import:SOT23-6")
      (libsource (lib "eagle-import") (part "LM3405AXMK/NOPB"))
    )
    (comp (ref "J1")
      (value "DF11-10DP-2DSA(01)")
      (footprint "eagle-import:DF11-10DP-2DSA")
      (libsource (lib "eagle-import") (part "DF11-10DP-2DSA(01)"))
    )
    (comp (ref "J2")
      (value "DNP")
      (footprint "eagle-import:MA07-1")
      (libsource (lib "eagle-import") (part "MA07-1"))
    )
    (comp (ref "J3")
      (value "14011213102000")
      (footprint "eagle-import:14011213102000")
      (libsource (lib "eagle-import") (part "14011213102000"))
    )
    (comp (ref "J7")
      (value "SS-6566-NF")
      (footprint "eagle-import:SS-6566-NF")
      (libsource (lib "eagle-import") (part "SS-6566-NF"))
    )
    (comp (ref "J8")
      (value "TSW-108-07-G-D")
      (footprint "eagle-import:MA08-2")
      (libsource (lib "eagle-import") (part "MA08-2"))
    )
    (comp (ref "J9")
      (value "SS-6566-NF")
      (footprint "eagle-import:SS-6566-NF")
      (libsource (lib "eagle-import") (part "SS-6566-NF"))
    )
    (comp (ref "J10")
      (value "CCM03-3504LFT-NR")
      (footprint "eagle-import:CCM03-3504LFT-NR")
      (libsource (lib "eagle-import") (part "CCM03-3504LFT-NR"))
    )
    (comp (ref "J11")
      (value "DNP")
      (footprint "eagle-import:MA05-1")
      (libsource (lib "eagle-import") (part "MA05-1"))
    )
    (comp (ref "J12")
      (value "DNP")
      (footprint "eagle-import:MA05-1")
      (libsource (lib "eagle-import") (part "MA05-1"))
    )
    (comp (ref "J14")
      (value "3-641215-2")
      (footprint "eagle-import:3-641215-2")
      (libsource (lib "eagle-import") (part "3-641215-2"))
    )
    (comp (ref "J30")
      (value "22-11-2072")
      (footprint "eagle-import:HRXL-MAXSONAR-WRC-MB7387")
      (libsource (lib "eagle-import") (part "HRXL-MAXSONAR-WRC-MB7387"))
    )
    (comp (ref "JP1")
      (value "DNP")
      (footprint "eagle-import:1X08-LOCK")
      (libsource (lib "eagle-import") (part "PINHD-1X8LOCK"))
    )
    (comp (ref "L1")
      (value "HI1206T500R-00")
      (footprint "eagle-import:1206")
      (libsource (lib "eagle-import") (part "L-1206"))
    )
    (comp (ref "L2")
      (value "HI1206T500R-00")
      (footprint "eagle-import:1206")
      (libsource (lib "eagle-import") (part "L-1206"))
    )
    (comp (ref "L3")
      (value "NRS8030T150MJGJ")
      (footprint "eagle-import:NRS8030")
      (libsource (lib "eagle-import") (part "NRS8030T150MJGJ"))
    )
    (comp (ref "Q2")
      (value "FDC6330L")
      (footprint "eagle-import:SSOT-6")
      (libsource (lib "eagle-import") (part "FDC6330L"))
    )
    (comp (ref "Q3")
      (value "SR3.3.TCT")
      (footprint "eagle-import:SOT-143")
      (libsource (lib "eagle-import") (part "SR05.TCT"))
    )
    (comp (ref "Q4")
      (value "7B-28.63636MAAJ-T")
      (footprint "eagle-import:7B")
      (libsource (lib "eagle-import") (part "7B-27.120MAAJ-T"))
    )
    (comp (ref "Q5")
      (value "FDC6330L")
      (footprint "eagle-import:SSOT-6")
      (libsource (lib "eagle-import") (part "FDC6324L"))
    )
    (comp (ref "Q6")
      (value "CM519 32.768KDZF-UT")
      (footprint "eagle-import:CM519")
      (libsource (lib "eagle-import") (part "CM519"))
    )
    (comp (ref "Q7")
      (value "SSM6P49NU,LFPZ")
      (footprint "eagle-import:MICRO_FET")
      (libsource (lib "eagle-import") (part "SSM6P49PZNU,LF"))
    )
    (comp (ref "R1")
      (value "300R")
      (footprint "eagle-import:0603")
      (libsource (lib "eagle-import") (part "R-0603"))
    )
    (comp (ref "R2")
      (value "4x100K")
      (footprint "eagle-import:0603-ARRAY")
      (libsource (lib "eagle-import") (part "EXB-38"))
    )
    (comp (ref "R3")
      (value "1M")
      (footprint "eagle-import:0603")
      (libsource (lib "eagle-import") (part "R-0603"))
    )
    (comp (ref "R4")
      (value "1M")
      (footprint "eagle-import:0603")
      (libsource (lib "eagle-import") (part "R-0603"))
    )
    (comp (ref "R5")
      (value "1M")
      (footprint "eagle-import:0603")
      (libsource (lib "eagle-import") (part "R-0603"))
    )
    (comp (ref "R6")
      (value "1M")
      (footprint "eagle-import:0603")
      (libsource (lib "eagle-import") (part "R-0603"))
    )
    (comp (ref "R7")
      (value "100K")
      (footprint "eagle-import:0603")
      (libsource (lib "eagle-import") (part "R-0603"))
    )
    (comp (ref "R8")
      (value "3.57K")
      (footprint "eagle-import:0603")
      (libsource (lib "eagle-import") (part "R-0603"))
    )
    (comp (ref "R9")
      (value "1M")
      (footprint "eagle-import:0603")
      (libsource (lib "eagle-import") (part "R-0603"))
    )
    (comp (ref "R10")
      (value "1M")
      (footprint "eagle-import:0603")
      (libsource (lib "eagle-import") (part "R-0603"))
    )
    (comp (ref "R11")
      (value "1M")
      (footprint "eagle-import:0603")
      (libsource (lib "eagle-import") (part "R-0603"))
    )
    (comp (ref "R12")
      (value "470K")
      (footprint "eagle-import:0603-0RTOP")
      (libsource (lib "eagle-import") (part "R-0603-0RTOP"))
    )
    (comp (ref "R13")
      (value "0R")
      (footprint "eagle-import:0603-0RTOP")
      (libsource (lib "eagle-import") (part "R-0603-0RTOP"))
    )
    (comp (ref "R14")
      (value "33K")
      (footprint "eagle-import:0603")
      (libsource (lib "eagle-import") (part "R-0603"))
    )
    (comp (ref "R15")
      (value "0R")
      (footprint "eagle-import:0603-0RTOP")
      (libsource (lib "eagle-import") (part "R-0603-0RTOP"))
    )
    (comp (ref "R18")
      (value "649R")
      (footprint "eagle-import:0603")
      (libsource (lib "eagle-import") (part "R-0603"))
    )
    (comp (ref "R19")
      (value "649R")
      (footprint "eagle-import:0603")
      (libsource (lib "eagle-import") (part "R-0603"))
    )
    (comp (ref "R20")
      (value "4x100K")
      (footprint "eagle-import:0603-ARRAY")
      (libsource (lib "eagle-import") (part "EXB-38"))
    )
    (comp (ref "R21")
      (value "4x100K")
      (footprint "eagle-import:0603-ARRAY")
      (libsource (lib "eagle-import") (part "EXB-38"))
    )
    (comp (ref "R22")
      (value "1M")
      (footprint "eagle-import:0603")
      (libsource (lib "eagle-import") (part "R-0603"))
    )
    (comp (ref "R23")
      (value "10K")
      (footprint "eagle-import:0603-0RTOP")
      (libsource (lib "eagle-import") (part "R-0603-0RTOP"))
    )
    (comp (ref "R24")
      (value "1M")
      (footprint "eagle-import:0603")
      (libsource (lib "eagle-import") (part "R-0603"))
    )
    (comp (ref "R25")
      (value "10K")
      (footprint "eagle-import:0603")
      (libsource (lib "eagle-import") (part "R-0603"))
    )
    (comp (ref "R26")
      (value "0.22R")
      (footprint "eagle-import:0603")
      (libsource (lib "eagle-import") (part "R-0603"))
    )
    (comp (ref "R27")
      (value "649R")
      (footprint "eagle-import:0603")
      (libsource (lib "eagle-import") (part "R-0603"))
    )
    (comp (ref "R28")
      (value "649R")
      (footprint "eagle-import:0603")
      (libsource (lib "eagle-import") (part "R-0603"))
    )
    (comp (ref "R29")
      (value "4x100K")
      (footprint "eagle-import:0603-ARRAY")
      (libsource (lib "eagle-import") (part "EXB-38"))
    )
    (comp (ref "R30")
      (value "10K")
      (footprint "eagle-import:0603")
      (libsource (lib "eagle-import") (part "R-0603"))
    )
    (comp (ref "R37")
      (value "300R")
      (footprint "eagle-import:0603")
      (libsource (lib "eagle-import") (part "R-0603"))
    )
    (comp (ref "TP1")
      (value "ROUND_SMD1MM")
      (footprint "eagle-import:SMD_ROUND_1MM")
      (libsource (lib "eagle-import") (part "ROUND_SMD1MM"))
    )
    (comp (ref "TP2")
      (value "ROUND_SMD1MM")
      (footprint "eagle-import:SMD_ROUND_1MM")
      (libsource (lib "eagle-import") (part "ROUND_SMD1MM"))
    )
    (comp (ref "TP3")
      (value "ROUND_SMD1MM")
      (footprint "eagle-import:SMD_ROUND_1MM")
      (libsource (lib "eagle-import") (part "ROUND_SMD1MM"))
    )
    (comp (ref "TP4")
      (value "ROUND_SMD1MM")
      (footprint "eagle-import:SMD_ROUND_1MM")
      (libsource (lib "eagle-import") (part "ROUND_SMD1MM"))
    )
    (comp (ref "TP5")
      (value "ROUND_SMD1MM")
      (footprint "eagle-import:SMD_ROUND_1MM")
      (libsource (lib "eagle-import") (part "ROUND_SMD1MM"))
    )
    (comp (ref "TP6")
      (value "ROUND_SMD1MM")
      (footprint "eagle-import:SMD_ROUND_1MM")
      (libsource (lib "eagle-import") (part "ROUND_SMD1MM"))
    )
    (comp (ref "TP7")
      (value "ROUND_SMD1MM")
      (footprint "eagle-import:SMD_ROUND_1MM")
      (libsource (lib "eagle-import") (part "ROUND_SMD1MM"))
    )
    (comp (ref "TP8")
      (value "ROUND_SMD1MM")
      (footprint "eagle-import:SMD_ROUND_1MM")
      (libsource (lib "eagle-import") (part "ROUND_SMD1MM"))
    )
    (comp (ref "TP9")
      (value "ROUND_SMD0.7MM")
      (footprint "eagle-import:SMD_ROUND_07MM")
      (libsource (lib "eagle-import") (part "ROUND_SMD0.7MM"))
    )
    (comp (ref "TP10")
      (value "ROUND_SMD1MM")
      (footprint "eagle-import:SMD_ROUND_1MM")
      (libsource (lib "eagle-import") (part "ROUND_SMD1MM"))
    )
    (comp (ref "TP11")
      (value "ROUND_SMD0.7MM")
      (footprint "eagle-import:SMD_ROUND_07MM")
      (libsource (lib "eagle-import") (part "ROUND_SMD0.7MM"))
    )
    (comp (ref "TP12")
      (value "TP_0812")
      (footprint "eagle-import:TP_0.8_1.2")
      (libsource (lib "eagle-import") (part "TP_0812"))
    )
    (comp (ref "U1")
      (value "LTC1955")
      (footprint "eagle-import:LFCSP_5X5_032")
      (libsource (lib "eagle-import") (part "LTC1955"))
    )
    (comp (ref "X1")
      (value "FH12-22(10)SA-1SH")
      (footprint "eagle-import:CON-FPC-1.0MM-10POS")
      (libsource (lib "eagle-import") (part "FH12-10S-0.5S1.00MM"))
    )
    (comp (ref "C43")
      (value "470uF/35-50V")
      (footprint "eagle-import:E5-13")
      (libsource (lib "eagle-import") (part "CPOL-USE5-13"))
    )
    (comp (ref "C44")
      (value "220uF, 16V, AL")
      (footprint "eagle-import:153CLV-0605")
      (libsource (lib "eagle-import") (part "CPOL-US153CLV-0605"))
    )
    (comp (ref "C122")
      (value "22uF,25V,1206")
      (footprint "eagle-import:C1206")
      (fields (field (name "MANUFACTURER") "Samsung"))
      (libsource (lib "eagle-import") (part "C-US-NP1206"))
    )
    (comp (ref "C123")
      (value "22uF,25V,1206")
      (footprint "eagle-import:C1206")
      (fields (field (name "MANUFACTURER") "Samsung"))
      (libsource (lib "eagle-import") (part "C-US-NP1206"))
    )
    (comp (ref "C124")
      (value "100pF,C0G")
      (footprint "eagle-import:C0603")
      (fields (field (name "MANUFACTURER") "Samsung"))
      (libsource (lib "eagle-import") (part "C-US-NP0603"))
    )
    (comp (ref "C125")
      (value "0.1uF")
      (footprint "eagle-import:C0603")
      (fields (field (name "MANUFACTURER") "Murata"))
      (libsource (lib "eagle-import") (part "C-US-NP0603"))
    )
    (comp (ref "C126")
      (value "0.1uF")
      (footprint "eagle-import:C0603")
      (fields (field (name "MANUFACTURER") "Murata"))
      (libsource (lib "eagle-import") (part "C-US-NP0603"))
    )
    (comp (ref "C127")
      (value "4.7uF/6.3V")
      (footprint "eagle-import:C0603")
      (fields (field (name "MANUFACTURER") "Samsung"))
      (libsource (lib "eagle-import") (part "C-US-NP0603"))
    )
    (comp (ref "C128")
      (value "22uF,25V,1206")
      (footprint "eagle-import:C1206")
      (fields (field (name "MANUFACTURER") "Samsung"))
      (libsource (lib "eagle-import") (part "C-US-NP1206"))
    )
    (comp (ref "C129")
      (value "22uF,25V,1206")
      (footprint "eagle-import:C1206")
      (fields (field (name "MANUFACTURER") "Samsung"))
      (libsource (lib "eagle-import") (part "C-US-NP1206"))
    )
    (comp (ref "C130")
      (value "22uF,25V,1206")
      (footprint "eagle-import:C1206")
      (fields (field (name "MANUFACTURER") "Samsung"))
      (libsource (lib "eagle-import") (part "C-US-NP1206"))
    )
    (comp (ref "C131")
      (value "130pF,C0G")
      (footprint "eagle-import:C0603")
      (fields (field (name "MANUFACTURER") "Samsung"))
      (libsource (lib "eagle-import") (part "C-US-NP0603"))
    )
    (comp (ref "C132")
      (value "0.1uF")
      (footprint "eagle-import:C0603")
      (fields (field (name "MANUFACTURER") "Murata"))
      (libsource (lib "eagle-import") (part "C-US-NP0603"))
    )
    (comp (ref "C133")
      (value "15nF")
      (footprint "eagle-import:C0603")
      (fields (field (name "MANUFACTURER") "Samsung"))
      (libsource (lib "eagle-import") (part "C-US-NP0603"))
    )
    (comp (ref "C134")
      (value "10nF")
      (footprint "eagle-import:0603")
      (libsource (lib "eagle-import") (part "C-0603"))
    )
    (comp (ref "C135")
      (value "10uF/35V")
      (footprint "eagle-import:1206")
      (libsource (lib "eagle-import") (part "C-1206"))
    )
    (comp (ref "C136")
      (value "22uF,25V,1206")
      (footprint "eagle-import:C1206")
      (fields (field (name "MANUFACTURER") "Samsung"))
      (libsource (lib "eagle-import") (part "C-US-NP1206"))
    )
    (comp (ref "C137")
      (value "22uF,25V,1206")
      (footprint "eagle-import:C1206")
      (fields (field (name "MANUFACTURER") "Samsung"))
      (libsource (lib "eagle-import") (part "C-US-NP1206"))
    )
    (comp (ref "C138")
      (value "100pF,C0G")
      (footprint "eagle-import:C0603")
      (fields (field (name "MANUFACTURER") "Samsung"))
      (libsource (lib "eagle-import") (part "C-US-NP0603"))
    )
    (comp (ref "C139")
      (value "0.1uF")
      (footprint "eagle-import:C0603")
      (fields (field (name "MANUFACTURER") "Murata"))
      (libsource (lib "eagle-import") (part "C-US-NP0603"))
    )
    (comp (ref "C140")
      (value "0.1uF")
      (footprint "eagle-import:C0603")
      (fields (field (name "MANUFACTURER") "Murata"))
      (libsource (lib "eagle-import") (part "C-US-NP0603"))
    )
    (comp (ref "C141")
      (value "4.7uF/6.3V")
      (footprint "eagle-import:C0603")
      (fields (field (name "MANUFACTURER") "Samsung"))
      (libsource (lib "eagle-import") (part "C-US-NP0603"))
    )
    (comp (ref "C142")
      (value "10uF/35V")
      (footprint "eagle-import:1206")
      (libsource (lib "eagle-import") (part "C-1206"))
    )
    (comp (ref "C143")
      (value "10uF,50V,1210")
      (footprint "eagle-import:C1210")
      (fields (field (name "MANUFACTURER") "Samsung"))
      (libsource (lib "eagle-import") (part "C-US-NP1210"))
    )
    (comp (ref "C144")
      (value "10uF,50V,1210")
      (footprint "eagle-import:C1210")
      (fields (field (name "MANUFACTURER") "Samsung"))
      (libsource (lib "eagle-import") (part "C-US-NP1210"))
    )
    (comp (ref "C145")
      (value "10uF,50V,1210")
      (footprint "eagle-import:C1210")
      (fields (field (name "MANUFACTURER") "Samsung"))
      (libsource (lib "eagle-import") (part "C-US-NP1210"))
    )
    (comp (ref "C146")
      (value "100pF")
      (footprint "eagle-import:C0603")
      (fields (field (name "MANUFACTURER") "Samsung"))
      (libsource (lib "eagle-import") (part "C-US-NP0603"))
    )
    (comp (ref "C147")
      (value "0.1uF")
      (footprint "eagle-import:C0603")
      (fields (field (name "MANUFACTURER") "Murata"))
      (libsource (lib "eagle-import") (part "C-US-NP0603"))
    )
    (comp (ref "C148")
      (value "10nF")
      (footprint "eagle-import:C0603")
      (fields (field (name "MANUFACTURER") "Samsung"))
      (libsource (lib "eagle-import") (part "C-US-NP0603"))
    )
    (comp (ref "C149")
      (value "22u/16V")
      (footprint "eagle-import:1210")
      (libsource (lib "eagle-import") (part "C-1210"))
    )
    (comp (ref "C150")
      (value "0.1uF")
      (footprint "eagle-import:0603")
      (libsource (lib "eagle-import") (part "C-0603"))
    )
    (comp (ref "C152")
      (value "22u/16V")
      (footprint "eagle-import:1210")
      (libsource (lib "eagle-import") (part "C-1210"))
    )
    (comp (ref "C153")
      (value "22u/16V")
      (footprint "eagle-import:1210")
      (libsource (lib "eagle-import") (part "C-1210"))
    )
    (comp (ref "C154")
      (value "0.1uF")
      (footprint "eagle-import:0603")
      (libsource (lib "eagle-import") (part "C-0603"))
    )
    (comp (ref "C155")
      (value "1nF")
      (footprint "eagle-import:0603")
      (libsource (lib "eagle-import") (part "C-0603"))
    )
    (comp (ref "C156")
      (value "TCJB157M006R0045")
      (footprint "eagle-import:3528-POL")
      (libsource (lib "eagle-import") (part "C-POL-3528"))
    )
    (comp (ref "C157")
      (value "47u/6.3V")
      (footprint "eagle-import:1210")
      (libsource (lib "eagle-import") (part "C-1210"))
    )
    (comp (ref "C158")
      (value "47u/6.3V")
      (footprint "eagle-import:1210")
      (libsource (lib "eagle-import") (part "C-1210"))
    )
    (comp (ref "C160")
      (value "15pF")
      (footprint "eagle-import:0603")
      (libsource (lib "eagle-import") (part "C-0603"))
    )
    (comp (ref "C163")
      (value "0.1uF")
      (footprint "eagle-import:0603")
      (libsource (lib "eagle-import") (part "C-0603"))
    )
    (comp (ref "C164")
      (value "330pF")
      (footprint "eagle-import:0603")
      (libsource (lib "eagle-import") (part "C-0603"))
    )
    (comp (ref "C187")
      (value "2mF/16V")
      (footprint "eagle-import:E7,5-18")
      (libsource (lib "eagle-import") (part "CPOL-USE7.5-18"))
    )
    (comp (ref "D20")
      (value "PMEG3030BEP")
      (footprint "eagle-import:SOD-128")
      (libsource (lib "eagle-import") (part "PMEG3030BEP"))
    )
    (comp (ref "D21")
      (value "SMAJ26A")
      (footprint "eagle-import:SMA")
      (libsource (lib "eagle-import") (part "SMAJ5.0A"))
    )
    (comp (ref "D22")
      (value "PMEG3030BEP")
      (footprint "eagle-import:SOD-128")
      (libsource (lib "eagle-import") (part "PMEG3030BEP"))
    )
    (comp (ref "D23")
      (value "LED-GR")
      (footprint "eagle-import:0805-POL")
      (libsource (lib "eagle-import") (part "LED-0805"))
    )
    (comp (ref "D24")
      (value "LED-GR")
      (footprint "eagle-import:0805-POL")
      (libsource (lib "eagle-import") (part "LED-0805"))
    )
    (comp (ref "D25")
      (value "SS14")
      (footprint "eagle-import:SMA")
      (libsource (lib "eagle-import") (part "SS14"))
    )
    (comp (ref "D26")
      (value "SS14")
      (footprint "eagle-import:SMA")
      (libsource (lib "eagle-import") (part "SS14"))
    )
    (comp (ref "D27")
      (value "SMLVT3V3")
      (footprint "eagle-import:SMA")
      (libsource (lib "eagle-import") (part "SMLVT3V3"))
    )
    (comp (ref "D28")
      (value "SMAJ5.0A")
      (footprint "eagle-import:SMA")
      (libsource (lib "eagle-import") (part "SMAJ5.0A"))
    )
    (comp (ref "D30")
      (value "PMEG3030BEP")
      (footprint "eagle-import:SOD-128")
      (libsource (lib "eagle-import") (part "PMEG3030BEP"))
    )
    (comp (ref "D31")
      (value "BAT54BRW-7F")
      (footprint "eagle-import:SOT-363")
      (libsource (lib "eagle-import") (part "BAT54BRW-7F"))
    )
    (comp (ref "D32")
      (value "P6SMB16A")
      (footprint "eagle-import:SMB")
      (libsource (lib "eagle-import") (part "P6SMB16A"))
    )
    (comp (ref "F3")
      (value "2920L250DR")
      (footprint "eagle-import:1812")
      (libsource (lib "eagle-import") (part "1812L014DR"))
    )
    (comp (ref "IC19")
      (value "MCP602-I/ST")
      (footprint "eagle-import:TSSOP8")
      (libsource (lib "eagle-import") (part "MCP6022-I/ST"))
    )
    (comp (ref "IC21")
      (value "LTC1771EMS8")
      (footprint "eagle-import:MSOP-08")
      (libsource (lib "eagle-import") (part "LTC1771EMS8"))
    )
    (comp (ref "J45")
      (value "3-641215-4")
      (footprint "eagle-import:3-641215-4")
      (libsource (lib "eagle-import") (part "3-641215-4"))
    )
    (comp (ref "J50")
      (value "0039301040")
      (footprint "eagle-import:0039301040")
      (libsource (lib "eagle-import") (part "0039301040"))
    )
    (comp (ref "L11")
      (value "SER2013-472MLD")
      (footprint "eagle-import:L_SER20XX")
      (fields (field (name "MANUFACTURER") "Coilcraft"))
      (libsource (lib "eagle-import") (part "LSER20XX"))
    )
    (comp (ref "L12")
      (value "SRR1280-150M")
      (footprint "eagle-import:L_SRR1280")
      (fields (field (name "MANUFACTURER") "Bourns") (field (name "MFR_PN") "SRR1280-1x0M"))
      (libsource (lib "eagle-import") (part "LSRR1280"))
    )
    (comp (ref "L14")
      (value "CR75NP-220KC")
      (footprint "eagle-import:CR75")
      (libsource (lib "eagle-import") (part "CR75-330KC"))
    )
    (comp (ref "Q14")
      (value "MAX9938HEUK")
      (footprint "eagle-import:SOT23-5")
      (libsource (lib "eagle-import") (part "TSM9938HEUK+T"))
    )
    (comp (ref "Q15")
      (value "SI4564DY")
      (footprint "eagle-import:SO-08")
      (libsource (lib "eagle-import") (part "SI4564DY"))
    )
    (comp (ref "Q16")
      (value "CSD87331Q3D")
      (footprint "eagle-import:SON8_3.3X3.3_TI")
      (fields (field (name "MANUFACTURER") "TI") (field (name "MFR_PN") "CSD87331Q3D"))
      (libsource (lib "eagle-import") (part "TRANS_DUAL_NFET_HALF-BRQ3D"))
    )
    (comp (ref "Q18")
      (value "SI4564DY")
      (footprint "eagle-import:SO-08")
      (libsource (lib "eagle-import") (part "SI4564DY"))
    )
    (comp (ref "Q19")
      (value "CSD87331Q3D")
      (footprint "eagle-import:SON8_3.3X3.3_TI")
      (fields (field (name "MANUFACTURER") "TI") (field (name "MFR_PN") "CSD87331Q3D"))
      (libsource (lib "eagle-import") (part "TRANS_DUAL_NFET_HALF-BRQ3D"))
    )
    (comp (ref "Q20")
      (value "IPD30N06S2L-23")
      (footprint "eagle-import:TO252")
      (libsource (lib "eagle-import") (part "IPD30N06S2L-23"))
    )
    (comp (ref "Q21")
      (value "IPD30N06S2L-23")
      (footprint "eagle-import:TO252")
      (libsource (lib "eagle-import") (part "IPD30N06S2L-23"))
    )
    (comp (ref "Q23")
      (value "FDN352AP")
      (footprint "eagle-import:SOT-23")
      (libsource (lib "eagle-import") (part "FDN352AP"))
    )
    (comp (ref "R40")
      (value "0.025R")
      (footprint "eagle-import:0805")
      (libsource (lib "eagle-import") (part "R-0805"))
    )
    (comp (ref "R41")
      (value "0.025R")
      (footprint "eagle-import:0805")
      (libsource (lib "eagle-import") (part "R-0805"))
    )
    (comp (ref "R42")
      (value "0.025R")
      (footprint "eagle-import:0805")
      (libsource (lib "eagle-import") (part "R-0805"))
    )
    (comp (ref "R43")
      (value "0.025R")
      (footprint "eagle-import:0805")
      (libsource (lib "eagle-import") (part "R-0805"))
    )
    (comp (ref "R44")
      (value "0.025R")
      (footprint "eagle-import:0805")
      (libsource (lib "eagle-import") (part "R-0805"))
    )
    (comp (ref "R45")
      (value "470R")
      (footprint "eagle-import:0603")
      (libsource (lib "eagle-import") (part "R-0603"))
    )
    (comp (ref "R46")
      (value "470R")
      (footprint "eagle-import:0603")
      (libsource (lib "eagle-import") (part "R-0603"))
    )
    (comp (ref "R154")
      (value "0.025R")
      (footprint "eagle-import:0805")
      (libsource (lib "eagle-import") (part "R-0805"))
    )
    (comp (ref "R156")
      (value "1M")
      (footprint "eagle-import:R0603")
      (fields (field (name "MANUFACTURER") "Panasonic"))
      (libsource (lib "eagle-import") (part "R-US_R0603"))
    )
    (comp (ref "R157")
      (value "10")
      (footprint "eagle-import:R0603")
      (fields (field (name "MANUFACTURER") "Rohm"))
      (libsource (lib "eagle-import") (part "R-US_R0603"))
    )
    (comp (ref "R158")
      (value "10")
      (footprint "eagle-import:R0603")
      (fields (field (name "MANUFACTURER") "Rohm"))
      (libsource (lib "eagle-import") (part "R-US_R0603"))
    )
    (comp (ref "R159")
      (value "1M")
      (footprint "eagle-import:R0603")
      (fields (field (name "MANUFACTURER") "Panasonic"))
      (libsource (lib "eagle-import") (part "R-US_R0603"))
    )
    (comp (ref "R160")
      (value "178k,1%")
      (footprint "eagle-import:R0603")
      (fields (field (name "MANUFACTURER") "Panasonic"))
      (libsource (lib "eagle-import") (part "R-US_R0603"))
    )
    (comp (ref "R161")
      (value "0")
      (footprint "eagle-import:R0603")
      (fields (field (name "MANUFACTURER") "Panasonic"))
      (libsource (lib "eagle-import") (part "R-US_R0603"))
    )
    (comp (ref "R162")
      (value "10k")
      (footprint "eagle-import:R0603")
      (fields (field (name "MANUFACTURER") "Panasonic"))
      (libsource (lib "eagle-import") (part "R-US_R0603"))
    )
    (comp (ref "R163")
      (value "0")
      (footprint "eagle-import:R0603")
      (fields (field (name "MANUFACTURER") "Panasonic"))
      (libsource (lib "eagle-import") (part "R-US_R0603"))
    )
    (comp (ref "R164")
      (value "5.90k,1%")
      (footprint "eagle-import:R0603")
      (fields (field (name "MANUFACTURER") "Panasonic"))
      (libsource (lib "eagle-import") (part "R-US_R0603"))
    )
    (comp (ref "R165")
      (value "93.1k,1%")
      (footprint "eagle-import:R0603")
      (fields (field (name "MANUFACTURER") "Panasonic"))
      (libsource (lib "eagle-import") (part "R-US_R0603"))
    )
    (comp (ref "R166")
      (value "20.0k,1%")
      (footprint "eagle-import:R0603")
      (fields (field (name "MANUFACTURER") "Panasonic"))
      (libsource (lib "eagle-import") (part "R-US_R0603"))
    )
    (comp (ref "R167")
      (value "100k")
      (footprint "eagle-import:R0603")
      (fields (field (name "MANUFACTURER") "Panasonic"))
      (libsource (lib "eagle-import") (part "R-US_R0603"))
    )
    (comp (ref "R170")
      (value "1M")
      (footprint "eagle-import:0603")
      (libsource (lib "eagle-import") (part "R-0603"))
    )
    (comp (ref "R171")
      (value "10")
      (footprint "eagle-import:R0603")
      (fields (field (name "MANUFACTURER") "Rohm"))
      (libsource (lib "eagle-import") (part "R-US_R0603"))
    )
    (comp (ref "R172")
      (value "10")
      (footprint "eagle-import:R0603")
      (fields (field (name "MANUFACTURER") "Rohm"))
      (libsource (lib "eagle-import") (part "R-US_R0603"))
    )
    (comp (ref "R173")
      (value "1M")
      (footprint "eagle-import:0603")
      (libsource (lib "eagle-import") (part "R-0603"))
    )
    (comp (ref "R174")
      (value "1M")
      (footprint "eagle-import:0603")
      (libsource (lib "eagle-import") (part "R-0603"))
    )
    (comp (ref "R175")
      (value "3.3K")
      (footprint "eagle-import:0805")
      (libsource (lib "eagle-import") (part "R-0805"))
    )
    (comp (ref "R176")
      (value "3.3K")
      (footprint "eagle-import:0805")
      (libsource (lib "eagle-import") (part "R-0805"))
    )
    (comp (ref "R177")
      (value "178k,1%")
      (footprint "eagle-import:R0603")
      (fields (field (name "MANUFACTURER") "Panasonic"))
      (libsource (lib "eagle-import") (part "R-US_R0603"))
    )
    (comp (ref "R178")
      (value "0")
      (footprint "eagle-import:R0603")
      (fields (field (name "MANUFACTURER") "Panasonic"))
      (libsource (lib "eagle-import") (part "R-US_R0603"))
    )
    (comp (ref "R179")
      (value "10k")
      (footprint "eagle-import:R0603")
      (fields (field (name "MANUFACTURER") "Panasonic"))
      (libsource (lib "eagle-import") (part "R-US_R0603"))
    )
    (comp (ref "R180")
      (value "0")
      (footprint "eagle-import:R0603")
      (fields (field (name "MANUFACTURER") "Panasonic"))
      (libsource (lib "eagle-import") (part "R-US_R0603"))
    )
    (comp (ref "R181")
      (value "5.90k,1%")
      (footprint "eagle-import:R0603")
      (fields (field (name "MANUFACTURER") "Panasonic"))
      (libsource (lib "eagle-import") (part "R-US_R0603"))
    )
    (comp (ref "R182")
      (value "93.1k,1%")
      (footprint "eagle-import:R0603")
      (fields (field (name "MANUFACTURER") "Panasonic"))
      (libsource (lib "eagle-import") (part "R-US_R0603"))
    )
    (comp (ref "R183")
      (value "1M")
      (footprint "eagle-import:0603")
      (libsource (lib "eagle-import") (part "R-0603"))
    )
    (comp (ref "R184")
      (value "1M")
      (footprint "eagle-import:0603")
      (libsource (lib "eagle-import") (part "R-0603"))
    )
    (comp (ref "R185")
      (value "20.0k,1%")
      (footprint "eagle-import:R0603")
      (fields (field (name "MANUFACTURER") "Panasonic"))
      (libsource (lib "eagle-import") (part "R-US_R0603"))
    )
    (comp (ref "R186")
      (value "100k")
      (footprint "eagle-import:R0603")
      (fields (field (name "MANUFACTURER") "Panasonic"))
      (libsource (lib "eagle-import") (part "R-US_R0603"))
    )
    (comp (ref "R187")
      (value "47K")
      (footprint "eagle-import:0603")
      (libsource (lib "eagle-import") (part "R-0603"))
    )
    (comp (ref "R189")
      (value "0.12R")
      (footprint "eagle-import:0805")
      (libsource (lib "eagle-import") (part "R-0805"))
    )
    (comp (ref "R190")
      (value "47K")
      (footprint "eagle-import:0603")
      (libsource (lib "eagle-import") (part "R-0603"))
    )
    (comp (ref "R193")
      (value "10K")
      (footprint "eagle-import:0603")
      (libsource (lib "eagle-import") (part "R-0603"))
    )
    (comp (ref "R194")
      (value "3.09M")
      (footprint "eagle-import:0603")
      (libsource (lib "eagle-import") (part "R-0603"))
    )
    (comp (ref "R197")
      (value "1M")
      (footprint "eagle-import:0603")
      (libsource (lib "eagle-import") (part "R-0603"))
    )
    (comp (ref "TP61")
      (value "TPB1,27")
      (footprint "eagle-import:B1,27")
      (libsource (lib "eagle-import") (part "TPB1,27"))
    )
    (comp (ref "TP62")
      (value "TPB1,27")
      (footprint "eagle-import:B1,27")
      (libsource (lib "eagle-import") (part "TPB1,27"))
    )
    (comp (ref "TP63")
      (value "TPB1,27")
      (footprint "eagle-import:B1,27")
      (libsource (lib "eagle-import") (part "TPB1,27"))
    )
    (comp (ref "TP64")
      (value "TPB1,27")
      (footprint "eagle-import:B1,27")
      (libsource (lib "eagle-import") (part "TPB1,27"))
    )
    (comp (ref "TP65")
      (value "TPB1,27")
      (footprint "eagle-import:B1,27")
      (libsource (lib "eagle-import") (part "TPB1,27"))
    )
    (comp (ref "TP66")
      (value "TPB1,27")
      (footprint "eagle-import:B1,27")
      (libsource (lib "eagle-import") (part "TPB1,27"))
    )
    (comp (ref "TP67")
      (value "TPB1,27")
      (footprint "eagle-import:B1,27")
      (libsource (lib "eagle-import") (part "TPB1,27"))
    )
    (comp (ref "U2")
      (value "LE33CD")
      (footprint "eagle-import:LE33")
      (libsource (lib "eagle-import") (part "LE33"))
    )
    (comp (ref "U6")
      (value "TPS43061")
      (footprint "eagle-import:QFN16_3X3_EP")
      (fields (field (name "MANUFACTURER") "TI"))
      (libsource (lib "eagle-import") (part "IC_TI_TPS43061RTE"))
    )
    (comp (ref "U7")
      (value "TPS43061")
      (footprint "eagle-import:QFN16_3X3_EP")
      (fields (field (name "MANUFACTURER") "TI"))
      (libsource (lib "eagle-import") (part "IC_TI_TPS43061RTE"))
    )
    (comp (ref "C114")
      (value "0.1u")
      (footprint "eagle-import:0603")
      (libsource (lib "eagle-import") (part "C-0603"))
    )
    (comp (ref "C115")
      (value "4.7uF/6.3V")
      (footprint "eagle-import:0603")
      (libsource (lib "eagle-import") (part "C-0603"))
    )
    (comp (ref "C121")
      (value "0.1u")
      (footprint "eagle-import:0603")
      (libsource (lib "eagle-import") (part "C-0603"))
    )
    (comp (ref "D17")
      (value "LED-GR")
      (footprint "eagle-import:0805-POL")
      (libsource (lib "eagle-import") (part "LED-0805"))
    )
    (comp (ref "D19")
      (value "LED-GR")
      (footprint "eagle-import:0805-POL")
      (libsource (lib "eagle-import") (part "LED-0805"))
    )
    (comp (ref "IC18")
      (value "FT232RL")
      (footprint "eagle-import:SSOP28DB")
      (libsource (lib "eagle-import") (part "FT232RL"))
    )
    (comp (ref "J41")
      (value "DNP")
      (footprint "eagle-import:MA06-1")
      (libsource (lib "eagle-import") (part "MA06-1"))
    )
    (comp (ref "R151")
      (value "470R")
      (footprint "eagle-import:0603")
      (libsource (lib "eagle-import") (part "R-0603"))
    )
    (comp (ref "R152")
      (value "470R")
      (footprint "eagle-import:0603")
      (libsource (lib "eagle-import") (part "R-0603"))
    )
    (comp (ref "TP60")
      (value "ROUND_SMD0.7MM")
      (footprint "eagle-import:SMD_ROUND_07MM")
      (libsource (lib "eagle-import") (part "ROUND_SMD0.7MM"))
    )
    (comp (ref "X2")
      (value "MINI-USB_4P-85-32004-10X")
      (footprint "eagle-import:85-32004-10X")
      (libsource (lib "eagle-import") (part "MINI-USB_4P-85-32004-10X"))
    )
  )
  (nets
    (net (code "1") (name "+3.3V") (class "Default")
      (node (ref "C1") (pin "1") (pinfunction "1_1") (pintype "passive"))
      (node (ref "C157") (pin "1") (pinfunction "1_1") (pintype "passive"))
      (node (ref "C16") (pin "2") (pinfunction "2_2") (pintype "passive"))
      (node (ref "C17") (pin "1") (pinfunction "1_1") (pintype "passive"))
      (node (ref "C2") (pin "1") (pinfunction "1_1") (pintype "passive"))
      (node (ref "C29") (pin "2") (pinfunction "2_2") (pintype "passive"))
      (node (ref "C5") (pin "1") (pinfunction "1_1") (pintype "passive"))
      (node (ref "C6") (pin "1") (pinfunction "1_1") (pintype "passive"))
      (node (ref "C8") (pin "1") (pinfunction "1_1") (pintype "passive"))
      (node (ref "C9") (pin "1") (pinfunction "1_1") (pintype "passive"))
      (node (ref "D1") (pin "2") (pinfunction "A2_2") (pintype "passive"))
      (node (ref "D27") (pin "+") (pinfunction "C_+") (pintype "passive"))
      (node (ref "D31") (pin "4") (pinfunction "K_4") (pintype "passive"))
      (node (ref "D31") (pin "5") (pinfunction "K_5") (pintype "passive"))
      (node (ref "IC3") (pin "16") (pinfunction "VDD16_16") (pintype "power_in"))
      (node (ref "IC3") (pin "2") (pinfunction "VDD2_2") (pintype "power_in"))
      (node (ref "IC3") (pin "37") (pinfunction "VDD37_37") (pintype "power_in"))
      (node (ref "IC3") (pin "46") (pinfunction "VDD46_46") (pintype "power_in"))
      (node (ref "IC3") (pin "62") (pinfunction "VDD62_62") (pintype "power_in"))
      (node (ref "IC3") (pin "86") (pinfunction "VDD86_86") (pintype "power_in"))
      (node (ref "J1") (pin "9") (pinfunction "9_9") (pintype "passive"))
      (node (ref "J11") (pin "2") (pinfunction "2_2") (pintype "passive"))
      (node (ref "J18") (pin "5") (pinfunction "5_5") (pintype "bidirectional"))
      (node (ref "J8") (pin "10") (pinfunction "10_10") (pintype "passive"))
      (node (ref "Q7") (pin "1") (pinfunction "S_1") (pintype "passive"))
      (node (ref "Q7") (pin "4") (pinfunction "S_4") (pintype "passive"))
      (node (ref "R1") (pin "2") (pinfunction "2_2") (pintype "passive"))
      (node (ref "R12") (pin "2") (pinfunction "2_2") (pintype "passive"))
      (node (ref "R14") (pin "2") (pinfunction "2_2") (pintype "passive"))
      (node (ref "R15") (pin "2") (pinfunction "2_2") (pintype "passive"))
      (node (ref "R167") (pin "2") (pinfunction "2_2") (pintype "passive"))
      (node (ref "R186") (pin "2") (pinfunction "2_2") (pintype "passive"))
      (node (ref "R187") (pin "2") (pinfunction "2_2") (pintype "passive"))
      (node (ref "R190") (pin "2") (pinfunction "2_2") (pintype "passive"))
      (node (ref "R2") (pin "7") (pinfunction "2_7") (pintype "passive"))
      (node (ref "R2") (pin "8") (pinfunction "2_8") (pintype "passive"))
      (node (ref "R37") (pin "2") (pinfunction "2_2") (pintype "passive"))
      (node (ref "TP64") (pin "TP") (pinfunction "TP_TP") (pintype "input"))
      (node (ref "TP9") (pin "P$1") (pinfunction "TP_P$1") (pintype "passive"))
      (node (ref "U1") (pin "1") (pinfunction "DVCC_1") (pintype "bidirectional"))
      (node (ref "U1") (pin "12") (pinfunction "SVBAT_12") (pintype "bidirectional"))
      (node (ref "U1") (pin "13") (pinfunction "PVBAT_13") (pintype "bidirectional"))
      (node (ref "U2") (pin "1") (pinfunction "VOUT_1") (pintype "bidirectional"))
    )
    (net (code "2") (name "+3.3V{slash}1") (class "Default")
      (node (ref "C22") (pin "1") (pinfunction "1_1") (pintype "passive"))
      (node (ref "C33") (pin "1") (pinfunction "1_1") (pintype "passive"))
      (node (ref "C37") (pin "1") (pinfunction "1_1") (pintype "passive"))
      (node (ref "C48") (pin "1") (pinfunction "1_1") (pintype "passive"))
      (node (ref "IC5") (pin "7") (pinfunction "A0_7") (pintype "input"))
      (node (ref "IC5") (pin "8") (pinfunction "VCC_8") (pintype "power_in"))
      (node (ref "IC6") (pin "8") (pinfunction "VCC_8") (pintype "power_in"))
      (node (ref "IC8") (pin "3") (pinfunction "/WP_3") (pintype "input"))
      (node (ref "IC8") (pin "7") (pinfunction "/HOLD_7") (pintype "input"))
      (node (ref "IC8") (pin "8") (pinfunction "VCC_8") (pintype "power_in"))
      (node (ref "J49") (pin "2") (pinfunction "2_2") (pintype "passive"))
      (node (ref "Q7") (pin "6") (pinfunction "D_6") (pintype "passive"))
      (node (ref "Q7") (pin "P1") (pinfunction "D1_P1") (pintype "passive"))
      (node (ref "R200") (pin "1") (pinfunction "1_1") (pintype "passive"))
      (node (ref "R201") (pin "1") (pinfunction "1_1") (pintype "passive"))
      (node (ref "R205") (pin "2") (pinfunction "2_2") (pintype "passive"))
      (node (ref "R206") (pin "2") (pinfunction "2_2") (pintype "passive"))
      (node (ref "R24") (pin "1") (pinfunction "1_1") (pintype "passive"))
      (node (ref "R25") (pin "1") (pinfunction "1_1") (pintype "passive"))
      (node (ref "R30") (pin "1") (pinfunction "1_1") (pintype "passive"))
      (node (ref "R31") (pin "2") (pinfunction "2_2") (pintype "passive"))
      (node (ref "R32") (pin "2") (pinfunction "2_2") (pintype "passive"))
      (node (ref "TP8") (pin "P$1") (pinfunction "TP_P$1") (pintype "passive"))
      (node (ref "U3") (pin "8") (pinfunction "VDD_8") (pintype "bidirectional"))
    )
    (net (code "3") (name "+3.3V{slash}2") (class "Default")
      (node (ref "C14") (pin "1") (pinfunction "1_1") (pintype "passive"))
      (node (ref "C35") (pin "2") (pinfunction "2_2") (pintype "passive"))
      (node (ref "IC2") (pin "8") (pinfunction "VCC_8") (pintype "power_in"))
      (node (ref "J18") (pin "10") (pinfunction "10_10") (pintype "bidirectional"))
      (node (ref "J2") (pin "2") (pinfunction "2_2") (pintype "passive"))
      (node (ref "J30") (pin "6") (pinfunction "VCC_6") (pintype "bidirectional"))
      (node (ref "JP1") (pin "2") (pinfunction "2_2") (pintype "passive"))
      (node (ref "Q7") (pin "3") (pinfunction "D_3") (pintype "passive"))
      (node (ref "Q7") (pin "P2") (pinfunction "D1_P2") (pintype "passive"))
      (node (ref "R11") (pin "2") (pinfunction "2_2") (pintype "passive"))
    )
    (net (code "4") (name "+5V") (class "Default")
      (node (ref "C149") (pin "1") (pinfunction "1_1") (pintype "passive"))
      (node (ref "C150") (pin "1") (pinfunction "1_1") (pintype "passive"))
      (node (ref "C156") (pin "1") (pinfunction "PIN+_1") (pintype "passive"))
      (node (ref "C158") (pin "1") (pinfunction "1_1") (pintype "passive"))
      (node (ref "C160") (pin "2") (pinfunction "2_2") (pintype "passive"))
      (node (ref "D28") (pin "+") (pinfunction "C_+") (pintype "passive"))
      (node (ref "J18") (pin "4") (pinfunction "4_4") (pintype "bidirectional"))
      (node (ref "L14") (pin "2") (pinfunction "2_2") (pintype "passive"))
      (node (ref "R194") (pin "1") (pinfunction "1_1") (pintype "passive"))
      (node (ref "TP65") (pin "TP") (pinfunction "TP_TP") (pintype "input"))
      (node (ref "U2") (pin "8") (pinfunction "VIN_8") (pintype "bidirectional"))
    )
    (net (code "5") (name "+SMB") (class "Default")
      (node (ref "C11") (pin "1") (pinfunction "1_1") (pintype "passive"))
      (node (ref "C135") (pin "1") (pinfunction "1_1") (pintype "passive"))
      (node (ref "C152") (pin "1") (pinfunction "1_1") (pintype "passive"))
      (node (ref "C153") (pin "1") (pinfunction "1_1") (pintype "passive"))
      (node (ref "C154") (pin "1") (pinfunction "1_1") (pintype "passive"))
      (node (ref "C155") (pin "1") (pinfunction "1_1") (pintype "passive"))
      (node (ref "C27") (pin "1") (pinfunction "1_1") (pintype "passive"))
      (node (ref "C28") (pin "1") (pinfunction "1_1") (pintype "passive"))
      (node (ref "D2") (pin "A") (pinfunction "A_A") (pintype "passive"))
      (node (ref "IC21") (pin "6") (pinfunction "VIN_6") (pintype "power_in"))
      (node (ref "IC21") (pin "8") (pinfunction "MODE_8") (pintype "input"))
      (node (ref "IC9") (pin "5") (pinfunction "VIN_5") (pintype "power_in"))
      (node (ref "J1") (pin "10") (pinfunction "10_10") (pintype "passive"))
      (node (ref "J18") (pin "2") (pinfunction "2_2") (pintype "bidirectional"))
      (node (ref "J7") (pin "2") (pinfunction "2_2") (pintype "passive"))
      (node (ref "J9") (pin "2") (pinfunction "2_2") (pintype "passive"))
      (node (ref "Q14") (pin "4") (pinfunction "VIN-_4") (pintype "input"))
      (node (ref "Q15") (pin "3") (pinfunction "S_3") (pintype "passive"))
      (node (ref "Q18") (pin "3") (pinfunction "S_3") (pintype "passive"))
      (node (ref "Q2") (pin "4") (pinfunction "Q2S_4") (pintype "bidirectional"))
      (node (ref "Q5") (pin "4") (pinfunction "Q2S_4") (pintype "bidirectional"))
      (node (ref "R154") (pin "2") (pinfunction "2_2") (pintype "passive"))
      (node (ref "R156") (pin "2") (pinfunction "2_2") (pintype "passive"))
      (node (ref "R170") (pin "1") (pinfunction "1_1") (pintype "passive"))
      (node (ref "R189") (pin "2") (pinfunction "2_2") (pintype "passive"))
      (node (ref "R20") (pin "6") (pinfunction "2_6") (pintype "passive"))
      (node (ref "R3") (pin "1") (pinfunction "1_1") (pintype "passive"))
      (node (ref "R40") (pin "2") (pinfunction "2_2") (pintype "passive"))
      (node (ref "R41") (pin "2") (pinfunction "2_2") (pintype "passive"))
    )
    (net (code "6") (name "+SMB_PRE") (class "Default")
      (node (ref "F3") (pin "1") (pinfunction "1_1") (pintype "passive"))
      (node (ref "J15") (pin "9") (pinfunction "9_9") (pintype "bidirectional"))
      (node (ref "J15") (pin "9A") (pinfunction "9_9A") (pintype "bidirectional"))
      (node (ref "J45") (pin "4") (pinfunction "4_4") (pintype "passive"))
    )
    (net (code "7") (name "3V3_AUD") (class "Default")
      (node (ref "C180") (pin "1") (pinfunction "1_1") (pintype "passive"))
      (node (ref "C181") (pin "1") (pinfunction "1_1") (pintype "passive"))
      (node (ref "C182") (pin "1") (pinfunction "1_1") (pintype "passive"))
      (node (ref "R206") (pin "1") (pinfunction "1_1") (pintype "passive"))
      (node (ref "R207") (pin "1") (pinfunction "1_1") (pintype "passive"))
      (node (ref "U9") (pin "6") (pinfunction "V+_6") (pintype "power_in"))
    )
    (net (code "8") (name "5V_ON") (class "Default")
      (node (ref "C163") (pin "1") (pinfunction "1_1") (pintype "passive"))
      (node (ref "IC21") (pin "1") (pinfunction "RUN/SS_1") (pintype "input"))
      (node (ref "IC3") (pin "92") (pinfunction "RA7/CN40_92") (pintype "bidirectional"))
    )
    (net (code "9") (name "18V_GND") (class "Default")
      (node (ref "C39") (pin "2") (pinfunction "2_2") (pintype "passive"))
      (node (ref "C40") (pin "1") (pinfunction "1_1") (pintype "passive"))
      (node (ref "R34") (pin "1") (pinfunction "1_1") (pintype "passive"))
      (node (ref "R39") (pin "1") (pinfunction "1_1") (pintype "passive"))
      (node (ref "U3") (pin "5") (pinfunction "AIN1_5") (pintype "bidirectional"))
    )
    (net (code "10") (name "18V_SENSE") (class "Default")
      (node (ref "J15") (pin "1") (pinfunction "1_1") (pintype "bidirectional"))
      (node (ref "J15") (pin "1A") (pinfunction "1_1A") (pintype "bidirectional"))
      (node (ref "J15") (pin "3") (pinfunction "3_3") (pintype "bidirectional"))
      (node (ref "J15") (pin "3A") (pinfunction "3_3A") (pintype "bidirectional"))
      (node (ref "R33") (pin "2") (pinfunction "2_2") (pintype "passive"))
    )
    (net (code "11") (name "A+") (class "Default")
      (node (ref "IC2") (pin "6") (pinfunction "A_6") (pintype "bidirectional"))
      (node (ref "L2") (pin "1") (pinfunction "1_1") (pintype "passive"))
      (node (ref "Q3") (pin "3") (pinfunction "3_3") (pintype "passive"))
      (node (ref "R11") (pin "1") (pinfunction "1_1") (pintype "passive"))
      (node (ref "R9") (pin "1") (pinfunction "1_1") (pintype "passive"))
    )
    (net (code "12") (name "A1") (class "Default")
      (node (ref "J7") (pin "3") (pinfunction "3_3") (pintype "passive"))
      (node (ref "J9") (pin "3") (pinfunction "3_3") (pintype "passive"))
      (node (ref "L2") (pin "2") (pinfunction "2_2") (pintype "passive"))
    )
    (net (code "13") (name "ACT_S1_B") (class "Default")
      (node (ref "IC3") (pin "52") (pinfunction "CN70/RP30/RF2_52") (pintype "bidirectional"))
      (node (ref "Q20") (pin "1") (pinfunction "G_1") (pintype "passive"))
      (node (ref "R183") (pin "1") (pinfunction "1_1") (pintype "passive"))
    )
    (net (code "14") (name "ACT_S2_B") (class "Default")
      (node (ref "IC3") (pin "53") (pinfunction "CN74/RP15/RF8_53") (pintype "bidirectional"))
      (node (ref "Q21") (pin "1") (pinfunction "G_1") (pintype "passive"))
      (node (ref "R184") (pin "1") (pinfunction "1_1") (pintype "passive"))
    )
    (net (code "15") (name "AGND") (class "Default")
      (node (ref "C165") (pin "2") (pinfunction "2_2") (pintype "passive"))
      (node (ref "C166") (pin "2") (pinfunction "2_2") (pintype "passive"))
      (node (ref "C167") (pin "2") (pinfunction "2_2") (pintype "passive"))
      (node (ref "C168") (pin "2") (pinfunction "2_2") (pintype "passive"))
      (node (ref "C169") (pin "2") (pinfunction "2_2") (pintype "passive"))
      (node (ref "C170") (pin "2") (pinfunction "2_2") (pintype "passive"))
      (node (ref "C171") (pin "2") (pinfunction "2_2") (pintype "passive"))
      (node (ref "C172") (pin "2") (pinfunction "2_2") (pintype "passive"))
      (node (ref "C176") (pin "2") (pinfunction "2_2") (pintype "passive"))
      (node (ref "C177") (pin "1") (pinfunction "1_1") (pintype "passive"))
      (node (ref "C179") (pin "2") (pinfunction "2_2") (pintype "passive"))
      (node (ref "C180") (pin "2") (pinfunction "2_2") (pintype "passive"))
      (node (ref "C181") (pin "2") (pinfunction "2_2") (pintype "passive"))
      (node (ref "C182") (pin "2") (pinfunction "2_2") (pintype "passive"))
      (node (ref "J17") (pin "1") (pinfunction "1_1") (pintype "bidirectional"))
      (node (ref "J17") (pin "12") (pinfunction "12_12") (pintype "bidirectional"))
      (node (ref "J17") (pin "3") (pinfunction "3_3") (pintype "bidirectional"))
      (node (ref "J17") (pin "6") (pinfunction "6_6") (pintype "bidirectional"))
      (node (ref "J17") (pin "9") (pinfunction "9_9") (pintype "bidirectional"))
      (node (ref "J47") (pin "3") (pinfunction "3_3") (pintype "passive"))
      (node (ref "J47") (pin "4") (pinfunction "4_4") (pintype "passive"))
      (node (ref "J48") (pin "1") (pinfunction "1_1") (pintype "passive"))
      (node (ref "L17") (pin "2") (pinfunction "2_2") (pintype "passive"))
      (node (ref "Q24") (pin "2") (pinfunction "S_2") (pintype "passive"))
      (node (ref "R202") (pin "2") (pinfunction "2_2") (pintype "passive"))
      (node (ref "R203") (pin "2") (pinfunction "2_2") (pintype "passive"))
      (node (ref "R210") (pin "2") (pinfunction "2_2") (pintype "passive"))
      (node (ref "R211") (pin "2") (pinfunction "2_2") (pintype "passive"))
      (node (ref "U8") (pin "19") (pinfunction "PGND_19") (pintype "power_in"))
      (node (ref "U8") (pin "24") (pinfunction "PGND_24") (pintype "power_in"))
      (node (ref "U8") (pin "3") (pinfunction "GND_3") (pintype "power_in"))
      (node (ref "U8") (pin "4") (pinfunction "GND_4") (pintype "power_in"))
      (node (ref "U8") (pin "8") (pinfunction "AGND_8") (pintype "power_in"))
      (node (ref "U8") (pin "EP") (pinfunction "EP_EP") (pintype "power_in"))
      (node (ref "U9") (pin "2") (pinfunction "V-_2") (pintype "power_in"))
    )
    (net (code "16") (name "AUD_AMP_FAULT#") (class "Default")
      (node (ref "R204") (pin "1") (pinfunction "1_1") (pintype "passive"))
      (node (ref "R205") (pin "1") (pinfunction "1_1") (pintype "passive"))
      (node (ref "U8") (pin "1") (pinfunction "~{SD}_1") (pintype "input"))
      (node (ref "U8") (pin "2") (pinfunction "~{FAULT}_2") (pintype "output"))
    )
    (net (code "17") (name "AUD_AMP_G0") (class "Default")
      (node (ref "IC3") (pin "41") (pinfunction "RB12/AN12/CN30_41") (pintype "bidirectional"))
      (node (ref "R200") (pin "2") (pinfunction "2_2") (pintype "passive"))
      (node (ref "R202") (pin "1") (pinfunction "1_1") (pintype "passive"))
      (node (ref "TP4") (pin "P$1") (pinfunction "TP_P$1") (pintype "passive"))
      (node (ref "U8") (pin "5") (pinfunction "GAIN0_5") (pintype "input"))
    )
    (net (code "18") (name "AUD_AMP_G1") (class "Default")
      (node (ref "IC3") (pin "42") (pinfunction "RB13/AN13/CN31_42") (pintype "bidirectional"))
      (node (ref "R201") (pin "2") (pinfunction "2_2") (pintype "passive"))
      (node (ref "R203") (pin "1") (pinfunction "1_1") (pintype "passive"))
      (node (ref "TP5") (pin "P$1") (pinfunction "TP_P$1") (pintype "passive"))
      (node (ref "U8") (pin "6") (pinfunction "GAIN1_6") (pintype "input"))
    )
    (net (code "19") (name "AUD_AMP_INN") (class "Default")
      (node (ref "C177") (pin "2") (pinfunction "2_2") (pintype "passive"))
      (node (ref "U8") (pin "11") (pinfunction "INN_11") (pintype "input"))
    )
    (net (code "20") (name "AUD_AMP_INP") (class "Default")
      (node (ref "C174") (pin "2") (pinfunction "2_2") (pintype "passive"))
      (node (ref "C175") (pin "2") (pinfunction "2_2") (pintype "passive"))
      (node (ref "U8") (pin "12") (pinfunction "INP_12") (pintype "input"))
    )
    (net (code "21") (name "AUD_BSN") (class "Default")
      (node (ref "C178") (pin "1") (pinfunction "1_1") (pintype "passive"))
      (node (ref "U8") (pin "22") (pinfunction "BSN_22") (pintype "input"))
      (node (ref "U8") (pin "26") (pinfunction "BSN_26") (pintype "input"))
    )
    (net (code "22") (name "AUD_BSP") (class "Default")
      (node (ref "C173") (pin "1") (pinfunction "1_1") (pintype "passive"))
      (node (ref "U8") (pin "17") (pinfunction "BSP_17") (pintype "input"))
      (node (ref "U8") (pin "21") (pinfunction "BSP_21") (pintype "input"))
    )
    (net (code "23") (name "AUD_GVDD") (class "Default")
      (node (ref "C172") (pin "1") (pinfunction "1_1") (pintype "passive"))
      (node (ref "U8") (pin "10") (pinfunction "PLIMIT_10") (pintype "input"))
      (node (ref "U8") (pin "9") (pinfunction "GVDD_9") (pintype "output"))
    )
    (net (code "24") (name "B-") (class "Default")
      (node (ref "IC2") (pin "7") (pinfunction "B_7") (pintype "bidirectional"))
      (node (ref "L1") (pin "1") (pinfunction "1_1") (pintype "passive"))
      (node (ref "Q3") (pin "2") (pinfunction "2_2") (pintype "passive"))
      (node (ref "R10") (pin "2") (pinfunction "2_2") (pintype "passive"))
      (node (ref "R9") (pin "2") (pinfunction "2_2") (pintype "passive"))
    )
    (net (code "25") (name "B1") (class "Default")
      (node (ref "J7") (pin "4") (pinfunction "4_4") (pintype "passive"))
      (node (ref "J9") (pin "4") (pinfunction "4_4") (pintype "passive"))
      (node (ref "L1") (pin "2") (pinfunction "2_2") (pintype "passive"))
    )
    (net (code "26") (name "B12_BOOT") (class "Default")
      (node (ref "C126") (pin "1") (pinfunction "1_1") (pintype "passive"))
      (node (ref "U6") (pin "11") (pinfunction "BOOT_11") (pintype "passive"))
    )
    (net (code "27") (name "B12_COMP") (class "Default")
      (node (ref "C131") (pin "1") (pinfunction "1_1") (pintype "passive"))
      (node (ref "R164") (pin "2") (pinfunction "2_2") (pintype "passive"))
      (node (ref "U6") (pin "3") (pinfunction "COMP_3") (pintype "passive"))
    )
    (net (code "28") (name "B12_FB") (class "Default")
      (node (ref "R160") (pin "1") (pinfunction "1_1") (pintype "passive"))
      (node (ref "R166") (pin "2") (pinfunction "2_2") (pintype "passive"))
      (node (ref "U6") (pin "4") (pinfunction "FB_4") (pintype "input"))
    )
    (net (code "29") (name "B12_FEED") (class "Default")
      (node (ref "L11") (pin "2") (pinfunction "2_2") (pintype "passive"))
      (node (ref "R158") (pin "2") (pinfunction "2_2") (pintype "passive"))
      (node (ref "R42") (pin "2") (pinfunction "2_2") (pintype "passive"))
      (node (ref "R43") (pin "2") (pinfunction "2_2") (pintype "passive"))
    )
    (net (code "30") (name "B12_HDRV") (class "Default")
      (node (ref "R161") (pin "2") (pinfunction "2_2") (pintype "passive"))
      (node (ref "U6") (pin "13") (pinfunction "HDRV_13") (pintype "output"))
    )
    (net (code "31") (name "B12_HG") (class "Default")
      (node (ref "Q16") (pin "3") (pinfunction "TG_3") (pintype "passive"))
      (node (ref "R161") (pin "1") (pinfunction "1_1") (pintype "passive"))
    )
    (net (code "32") (name "B12_ISNS+") (class "Default")
      (node (ref "C124") (pin "1") (pinfunction "1_1") (pintype "passive"))
      (node (ref "R157") (pin "1") (pinfunction "1_1") (pintype "passive"))
      (node (ref "U6") (pin "6") (pinfunction "ISNS+_6") (pintype "input"))
    )
    (net (code "33") (name "B12_ISNS-") (class "Default")
      (node (ref "C124") (pin "2") (pinfunction "2_2") (pintype "passive"))
      (node (ref "R158") (pin "1") (pinfunction "1_1") (pintype "passive"))
      (node (ref "U6") (pin "5") (pinfunction "ISNS-_5") (pintype "input"))
    )
    (net (code "34") (name "B12_L") (class "Default")
      (node (ref "D20") (pin "A") (pinfunction "A_A") (pintype "passive"))
      (node (ref "L11") (pin "1") (pinfunction "1_1") (pintype "passive"))
      (node (ref "Q16") (pin "6") (pinfunction "VSW_6") (pintype "passive"))
      (node (ref "Q16") (pin "7") (pinfunction "VSW_7") (pintype "passive"))
      (node (ref "Q16") (pin "8") (pinfunction "VSW_8") (pintype "passive"))
    )
    (net (code "35") (name "B12_LDRV") (class "Default")
      (node (ref "R163") (pin "2") (pinfunction "2_2") (pintype "passive"))
      (node (ref "U6") (pin "8") (pinfunction "LDRV_8") (pintype "output"))
    )
    (net (code "36") (name "B12_LG") (class "Default")
      (node (ref "Q16") (pin "5") (pinfunction "BG_5") (pintype "passive"))
      (node (ref "R163") (pin "1") (pinfunction "1_1") (pintype "passive"))
    )
    (net (code "37") (name "B12_PG") (class "Default")
      (node (ref "IC3") (pin "69") (pinfunction "CN54/RP4/RD9_69") (pintype "bidirectional"))
      (node (ref "R167") (pin "1") (pinfunction "1_1") (pintype "passive"))
      (node (ref "U6") (pin "14") (pinfunction "PGOOD_14") (pintype "open_collector"))
    )
    (net (code "38") (name "B12_RC") (class "Default")
      (node (ref "C133") (pin "1") (pinfunction "1_1") (pintype "passive"))
      (node (ref "R164") (pin "1") (pinfunction "1_1") (pintype "passive"))
    )
    (net (code "39") (name "B12_RT") (class "Default")
      (node (ref "R165") (pin "2") (pinfunction "2_2") (pintype "passive"))
      (node (ref "U6") (pin "1") (pinfunction "RT/CLK_1") (pintype "passive"))
    )
    (net (code "40") (name "B12_SS") (class "Default")
      (node (ref "C132") (pin "1") (pinfunction "1_1") (pintype "passive"))
      (node (ref "U6") (pin "2") (pinfunction "SS_2") (pintype "passive"))
    )
    (net (code "41") (name "B12_SW") (class "Default")
      (node (ref "C126") (pin "2") (pinfunction "2_2") (pintype "passive"))
      (node (ref "Q16") (pin "4") (pinfunction "TGR_4") (pintype "passive"))
      (node (ref "U6") (pin "12") (pinfunction "SW_12") (pintype "output"))
    )
    (net (code "42") (name "B12_VCC") (class "Default")
      (node (ref "C127") (pin "1") (pinfunction "1_1") (pintype "passive"))
      (node (ref "U6") (pin "10") (pinfunction "VCC_10") (pintype "output"))
    )
    (net (code "43") (name "BAT_GND") (class "Default")
      (node (ref "C41") (pin "2") (pinfunction "2_2") (pintype "passive"))
      (node (ref "C42") (pin "1") (pinfunction "1_1") (pintype "passive"))
      (node (ref "R36") (pin "1") (pinfunction "1_1") (pintype "passive"))
      (node (ref "R38") (pin "1") (pinfunction "1_1") (pintype "passive"))
      (node (ref "U3") (pin "7") (pinfunction "AIN3_7") (pintype "bidirectional"))
    )
    (net (code "44") (name "BAT_SENSE") (class "Default")
      (node (ref "J15") (pin "5") (pinfunction "5_5") (pintype "bidirectional"))
      (node (ref "J15") (pin "5A") (pinfunction "5_5A") (pintype "bidirectional"))
      (node (ref "J15") (pin "7") (pinfunction "7_7") (pintype "bidirectional"))
      (node (ref "J15") (pin "7A") (pinfunction "7_7A") (pintype "bidirectional"))
      (node (ref "R35") (pin "2") (pinfunction "2_2") (pintype "passive"))
    )
    (net (code "45") (name "BTN_1") (class "Default")
      (node (ref "IC4") (pin "1") (pinfunction "GP0/PGD_1") (pintype "bidirectional"))
      (node (ref "J12") (pin "4") (pinfunction "4_4") (pintype "passive"))
      (node (ref "J19") (pin "10") (pinfunction "10_10") (pintype "bidirectional"))
      (node (ref "R2") (pin "2") (pinfunction "1_2") (pintype "passive"))
      (node (ref "R2") (pin "3") (pinfunction "1_3") (pintype "passive"))
    )
    (net (code "46") (name "BTN_1PIN_B") (class "Default")
      (node (ref "C12") (pin "1") (pinfunction "1_1") (pintype "passive"))
      (node (ref "IC3") (pin "90") (pinfunction "RG0/CN77_90") (pintype "bidirectional"))
      (node (ref "R2") (pin "6") (pinfunction "2_6") (pintype "passive"))
    )
    (net (code "47") (name "BTN_2") (class "Default")
      (node (ref "IC4") (pin "3") (pinfunction "GP1/PGC_3") (pintype "bidirectional"))
      (node (ref "J12") (pin "5") (pinfunction "5_5") (pintype "passive"))
      (node (ref "J19") (pin "12") (pinfunction "12_12") (pintype "bidirectional"))
      (node (ref "R2") (pin "1") (pinfunction "1_1") (pintype "passive"))
      (node (ref "R2") (pin "4") (pinfunction "1_4") (pintype "passive"))
    )
    (net (code "48") (name "BTN_2PIN_B") (class "Default")
      (node (ref "C13") (pin "1") (pinfunction "1_1") (pintype "passive"))
      (node (ref "IC3") (pin "89") (pinfunction "RG1/CN78_89") (pintype "bidirectional"))
      (node (ref "R2") (pin "5") (pinfunction "2_5") (pintype "passive"))
    )
    (net (code "49") (name "CL_IRQ") (class "Default")
      (node (ref "IC3") (pin "20") (pinfunction "RB5/AN5/CN7/RP18_20") (pintype "bidirectional"))
      (node (ref "J1") (pin "4") (pinfunction "4_4") (pintype "passive"))
    )
    (net (code "50") (name "CON_LED") (class "Default")
      (node (ref "IC3") (pin "40") (pinfunction "CN75/RPI32/RF12_40") (pintype "bidirectional"))
      (node (ref "JP1") (pin "6") (pinfunction "6_6") (pintype "passive"))
    )
    (net (code "51") (name "DCDC_12V_EN") (class "Default")
      (node (ref "IC3") (pin "84") (pinfunction "CN16/RD7_84") (pintype "bidirectional"))
      (node (ref "Q15") (pin "2") (pinfunction "G_2") (pintype "passive"))
      (node (ref "R162") (pin "2") (pinfunction "2_2") (pintype "passive"))
      (node (ref "U6") (pin "15") (pinfunction "EN_15") (pintype "input"))
    )
    (net (code "52") (name "DGND") (class "Default")
      (node (ref "B1") (pin "-") (pinfunction "-_-") (pintype "passive"))
      (node (ref "C1") (pin "2") (pinfunction "2_2") (pintype "passive"))
      (node (ref "C10") (pin "1") (pinfunction "1_1") (pintype "passive"))
      (node (ref "C11") (pin "2") (pinfunction "2_2") (pintype "passive"))
      (node (ref "C114") (pin "1") (pinfunction "1_1") (pintype "passive"))
      (node (ref "C115") (pin "1") (pinfunction "1_1") (pintype "passive"))
      (node (ref "C12") (pin "2") (pinfunction "2_2") (pintype "passive"))
      (node (ref "C121") (pin "1") (pinfunction "1_1") (pintype "passive"))
      (node (ref "C122") (pin "2") (pinfunction "2_2") (pintype "passive"))
      (node (ref "C123") (pin "2") (pinfunction "2_2") (pintype "passive"))
      (node (ref "C125") (pin "2") (pinfunction "2_2") (pintype "passive"))
      (node (ref "C127") (pin "2") (pinfunction "2_2") (pintype "passive"))
      (node (ref "C128") (pin "2") (pinfunction "2_2") (pintype "passive"))
      (node (ref "C129") (pin "2") (pinfunction "2_2") (pintype "passive"))
      (node (ref "C13") (pin "2") (pinfunction "2_2") (pintype "passive"))
      (node (ref "C130") (pin "2") (pinfunction "2_2") (pintype "passive"))
      (node (ref "C131") (pin "2") (pinfunction "2_2") (pintype "passive"))
      (node (ref "C132") (pin "2") (pinfunction "2_2") (pintype "passive"))
      (node (ref "C133") (pin "2") (pinfunction "2_2") (pintype "passive"))
      (node (ref "C134") (pin "2") (pinfunction "2_2") (pintype "passive"))
      (node (ref "C135") (pin "2") (pinfunction "2_2") (pintype "passive"))
      (node (ref "C136") (pin "2") (pinfunction "2_2") (pintype "passive"))
      (node (ref "C137") (pin "2") (pinfunction "2_2") (pintype "passive"))
      (node (ref "C139") (pin "2") (pinfunction "2_2") (pintype "passive"))
      (node (ref "C14") (pin "2") (pinfunction "2_2") (pintype "passive"))
      (node (ref "C141") (pin "2") (pinfunction "2_2") (pintype "passive"))
      (node (ref "C142") (pin "2") (pinfunction "2_2") (pintype "passive"))
      (node (ref "C143") (pin "2") (pinfunction "2_2") (pintype "passive"))
      (node (ref "C144") (pin "2") (pinfunction "2_2") (pintype "passive"))
      (node (ref "C145") (pin "2") (pinfunction "2_2") (pintype "passive"))
      (node (ref "C146") (pin "2") (pinfunction "2_2") (pintype "passive"))
      (node (ref "C147") (pin "2") (pinfunction "2_2") (pintype "passive"))
      (node (ref "C148") (pin "2") (pinfunction "2_2") (pintype "passive"))
      (node (ref "C149") (pin "2") (pinfunction "2_2") (pintype "passive"))
      (node (ref "C150") (pin "2") (pinfunction "2_2") (pintype "passive"))
      (node (ref "C152") (pin "2") (pinfunction "2_2") (pintype "passive"))
      (node (ref "C153") (pin "2") (pinfunction "2_2") (pintype "passive"))
      (node (ref "C154") (pin "2") (pinfunction "2_2") (pintype "passive"))
      (node (ref "C156") (pin "2") (pinfunction "PIN-_2") (pintype "passive"))
      (node (ref "C157") (pin "2") (pinfunction "2_2") (pintype "passive"))
      (node (ref "C158") (pin "2") (pinfunction "2_2") (pintype "passive"))
      (node (ref "C16") (pin "1") (pinfunction "1_1") (pintype "passive"))
      (node (ref "C163") (pin "2") (pinfunction "2_2") (pintype "passive"))
      (node (ref "C164") (pin "2") (pinfunction "2_2") (pintype "passive"))
      (node (ref "C17") (pin "2") (pinfunction "2_2") (pintype "passive"))
      (node (ref "C18") (pin "1") (pinfunction "1_1") (pintype "passive"))
      (node (ref "C187") (pin "-") (pinfunction "-_-") (pintype "passive"))
      (node (ref "C19") (pin "1") (pinfunction "1_1") (pintype "passive"))
      (node (ref "C2") (pin "2") (pinfunction "2_2") (pintype "passive"))
      (node (ref "C20") (pin "1") (pinfunction "1_1") (pintype "passive"))
      (node (ref "C21") (pin "2") (pinfunction "2_2") (pintype "passive"))
      (node (ref "C22") (pin "2") (pinfunction "2_2") (pintype "passive"))
      (node (ref "C23") (pin "2") (pinfunction "2_2") (pintype "passive"))
      (node (ref "C24") (pin "2") (pinfunction "2_2") (pintype "passive"))
      (node (ref "C25") (pin "2") (pinfunction "2_2") (pintype "passive"))
      (node (ref "C26") (pin "2") (pinfunction "2_2") (pintype "passive"))
      (node (ref "C27") (pin "2") (pinfunction "2_2") (pintype "passive"))
      (node (ref "C28") (pin "2") (pinfunction "2_2") (pintype "passive"))
      (node (ref "C29") (pin "1") (pinfunction "1_1") (pintype "passive"))
      (node (ref "C3") (pin "2") (pinfunction "2_2") (pintype "passive"))
      (node (ref "C32") (pin "2") (pinfunction "2_2") (pintype "passive"))
      (node (ref "C33") (pin "2") (pinfunction "2_2") (pintype "passive"))
      (node (ref "C34") (pin "2") (pinfunction "2_2") (pintype "passive"))
      (node (ref "C35") (pin "1") (pinfunction "1_1") (pintype "passive"))
      (node (ref "C36") (pin "2") (pinfunction "2_2") (pintype "passive"))
      (node (ref "C37") (pin "2") (pinfunction "2_2") (pintype "passive"))
      (node (ref "C38") (pin "1") (pinfunction "1_1") (pintype "passive"))
      (node (ref "C4") (pin "2") (pinfunction "2_2") (pintype "passive"))
      (node (ref "C40") (pin "2") (pinfunction "2_2") (pintype "passive"))
      (node (ref "C42") (pin "2") (pinfunction "2_2") (pintype "passive"))
      (node (ref "C43") (pin "-") (pinfunction "-_-") (pintype "passive"))
      (node (ref "C44") (pin "-") (pinfunction "-_-") (pintype "passive"))
      (node (ref "C47") (pin "2") (pinfunction "2_2") (pintype "passive"))
      (node (ref "C48") (pin "2") (pinfunction "2_2") (pintype "passive"))
      (node (ref "C5") (pin "2") (pinfunction "2_2") (pintype "passive"))
      (node (ref "C59") (pin "2") (pinfunction "2_2") (pintype "passive"))
      (node (ref "C6") (pin "2") (pinfunction "2_2") (pintype "passive"))
      (node (ref "C7") (pin "2") (pinfunction "2_2") (pintype "passive"))
      (node (ref "C8") (pin "2") (pinfunction "2_2") (pintype "passive"))
      (node (ref "C9") (pin "2") (pinfunction "2_2") (pintype "passive"))
      (node (ref "D21") (pin "-") (pinfunction "A_-") (pintype "passive"))
      (node (ref "D27") (pin "-") (pinfunction "A_-") (pintype "passive"))
      (node (ref "D28") (pin "-") (pinfunction "A_-") (pintype "passive"))
      (node (ref "D30") (pin "A") (pinfunction "A_A") (pintype "passive"))
      (node (ref "D31") (pin "1") (pinfunction "A_1") (pintype "passive"))
      (node (ref "D31") (pin "2") (pinfunction "A_2") (pintype "passive"))
      (node (ref "D32") (pin "A") (pinfunction "A_A") (pintype "passive"))
      (node (ref "D4") (pin "A") (pinfunction "A_A") (pintype "passive"))
      (node (ref "H1") (pin "P1") (pinfunction "P$1_P1") (pintype "bidirectional"))
      (node (ref "H2") (pin "P1") (pinfunction "P$1_P1") (pintype "bidirectional"))
      (node (ref "H3") (pin "P1") (pinfunction "P$1_P1") (pintype "bidirectional"))
      (node (ref "H4") (pin "P1") (pinfunction "P$1_P1") (pintype "bidirectional"))
      (node (ref "H5") (pin "P1") (pinfunction "P$1_P1") (pintype "bidirectional"))
      (node (ref "IC1") (pin "3") (pinfunction "GND_3") (pintype "power_in"))
      (node (ref "IC18") (pin "18") (pinfunction "GND2_18") (pintype "power_in"))
      (node (ref "IC18") (pin "21") (pinfunction "GND3_21") (pintype "power_in"))
      (node (ref "IC18") (pin "25") (pinfunction "AGND_25") (pintype "power_in"))
      (node (ref "IC18") (pin "26") (pinfunction "TEST_26") (pintype "bidirectional"))
      (node (ref "IC18") (pin "7") (pinfunction "GND1_7") (pintype "power_in"))
      (node (ref "IC19") (pin "4") (pinfunction "V-_4") (pintype "power_in"))
      (node (ref "IC2") (pin "5") (pinfunction "GND_5") (pintype "power_in"))
      (node (ref "IC21") (pin "4") (pinfunction "GND_4") (pintype "power_in"))
      (node (ref "IC3") (pin "15") (pinfunction "VSS15_15") (pintype "power_in"))
      (node (ref "IC3") (pin "31") (pinfunction "AVSS_31") (pintype "power_in"))
      (node (ref "IC3") (pin "36") (pinfunction "VSS36_36") (pintype "power_in"))
      (node (ref "IC3") (pin "45") (pinfunction "VSS45_45") (pintype "power_in"))
      (node (ref "IC3") (pin "65") (pinfunction "VSS65_65") (pintype "power_in"))
      (node (ref "IC3") (pin "75") (pinfunction "VSS75_75") (pintype "power_in"))
      (node (ref "IC4") (pin "2") (pinfunction "VSS_2") (pintype "power_in"))
      (node (ref "IC5") (pin "4") (pinfunction "GND_4") (pintype "power_in"))
      (node (ref "IC5") (pin "5") (pinfunction "A2_5") (pintype "input"))
      (node (ref "IC5") (pin "6") (pinfunction "A1_6") (pintype "input"))
      (node (ref "IC6") (pin "1") (pinfunction "A0_1") (pintype "input"))
      (node (ref "IC6") (pin "2") (pinfunction "A1_2") (pintype "input"))
      (node (ref "IC6") (pin "3") (pinfunction "A2_3") (pintype "input"))
      (node (ref "IC6") (pin "4") (pinfunction "GND_4") (pintype "power_in"))
      (node (ref "IC6") (pin "7") (pinfunction "WP_7") (pintype "input"))
      (node (ref "IC7") (pin "12") (pinfunction "CLKOE_12") (pintype "input"))
      (node (ref "IC7") (pin "7") (pinfunction "VSS_7") (pintype "power_in"))
      (node (ref "IC8") (pin "4") (pinfunction "GND_4") (pintype "power_in"))
      (node (ref "IC9") (pin "2") (pinfunction "GND_2") (pintype "power_in"))
      (node (ref "J1") (pin "1") (pinfunction "1_1") (pintype "passive"))
      (node (ref "J10") (pin "C5") (pinfunction "C5_C5") (pintype "bidirectional"))
      (node (ref "J11") (pin "3") (pinfunction "3_3") (pintype "passive"))
      (node (ref "J12") (pin "3") (pinfunction "3_3") (pintype "passive"))
      (node (ref "J15") (pin "10") (pinfunction "10_10") (pintype "bidirectional"))
      (node (ref "J15") (pin "10A") (pinfunction "10_10A") (pintype "bidirectional"))
      (node (ref "J18") (pin "6") (pinfunction "6_6") (pintype "bidirectional"))
      (node (ref "J18") (pin "9") (pinfunction "9_9") (pintype "bidirectional"))
      (node (ref "J19") (pin "1") (pinfunction "1_1") (pintype "bidirectional"))
      (node (ref "J19") (pin "11") (pinfunction "11_11") (pintype "bidirectional"))
      (node (ref "J19") (pin "3") (pinfunction "3_3") (pintype "bidirectional"))
      (node (ref "J19") (pin "5") (pinfunction "5_5") (pintype "bidirectional"))
      (node (ref "J19") (pin "7") (pinfunction "7_7") (pintype "bidirectional"))
      (node (ref "J19") (pin "9") (pinfunction "9_9") (pintype "bidirectional"))
      (node (ref "J2") (pin "1") (pinfunction "1_1") (pintype "passive"))
      (node (ref "J3") (pin "11") (pinfunction "11_11") (pintype "bidirectional"))
      (node (ref "J3") (pin "12") (pinfunction "12_12") (pintype "bidirectional"))
      (node (ref "J3") (pin "5") (pinfunction "5_5") (pintype "bidirectional"))
      (node (ref "J3") (pin "7") (pinfunction "7_7") (pintype "bidirectional"))
      (node (ref "J3") (pin "8") (pinfunction "8_8") (pintype "bidirectional"))
      (node (ref "J30") (pin "7") (pinfunction "GND_7") (pintype "bidirectional"))
      (node (ref "J41") (pin "1") (pinfunction "1_1") (pintype "passive"))
      (node (ref "J45") (pin "1") (pinfunction "1_1") (pintype "passive"))
      (node (ref "J50") (pin "1") (pinfunction "1_1") (pintype "bidirectional"))
      (node (ref "J50") (pin "2") (pinfunction "2_2") (pintype "bidirectional"))
      (node (ref "J7") (pin "1") (pinfunction "1_1") (pintype "passive"))
      (node (ref "J7") (pin "6") (pinfunction "6_6") (pintype "passive"))
      (node (ref "J8") (pin "9") (pinfunction "9_9") (pintype "passive"))
      (node (ref "J9") (pin "1") (pinfunction "1_1") (pintype "passive"))
      (node (ref "J9") (pin "6") (pinfunction "6_6") (pintype "passive"))
      (node (ref "JP1") (pin "1") (pinfunction "1_1") (pintype "passive"))
      (node (ref "L17") (pin "1") (pinfunction "1_1") (pintype "passive"))
      (node (ref "Q14") (pin "1") (pinfunction "GND_1") (pintype "power_in"))
      (node (ref "Q14") (pin "2") (pinfunction "GND1_2") (pintype "power_in"))
      (node (ref "Q15") (pin "1") (pinfunction "S_1") (pintype "passive"))
      (node (ref "Q16") (pin "EP") (pinfunction "PGND_EP") (pintype "passive"))
      (node (ref "Q18") (pin "1") (pinfunction "S_1") (pintype "passive"))
      (node (ref "Q19") (pin "EP") (pinfunction "PGND_EP") (pintype "passive"))
      (node (ref "Q2") (pin "1") (pinfunction "Q1S_1") (pintype "bidirectional"))
      (node (ref "Q20") (pin "2") (pinfunction "S_2") (pintype "passive"))
      (node (ref "Q21") (pin "2") (pinfunction "S_2") (pintype "passive"))
      (node (ref "Q3") (pin "1") (pinfunction "1_1") (pintype "passive"))
      (node (ref "Q5") (pin "1") (pinfunction "Q1S_1") (pintype "bidirectional"))
      (node (ref "R10") (pin "1") (pinfunction "1_1") (pintype "passive"))
      (node (ref "R13") (pin "1") (pinfunction "1_1") (pintype "passive"))
      (node (ref "R162") (pin "1") (pinfunction "1_1") (pintype "passive"))
      (node (ref "R165") (pin "1") (pinfunction "1_1") (pintype "passive"))
      (node (ref "R166") (pin "1") (pinfunction "1_1") (pintype "passive"))
      (node (ref "R174") (pin "2") (pinfunction "2_2") (pintype "passive"))
      (node (ref "R179") (pin "1") (pinfunction "1_1") (pintype "passive"))
      (node (ref "R182") (pin "1") (pinfunction "1_1") (pintype "passive"))
      (node (ref "R183") (pin "2") (pinfunction "2_2") (pintype "passive"))
      (node (ref "R184") (pin "2") (pinfunction "2_2") (pintype "passive"))
      (node (ref "R185") (pin "1") (pinfunction "1_1") (pintype "passive"))
      (node (ref "R197") (pin "2") (pinfunction "2_2") (pintype "passive"))
      (node (ref "R20") (pin "2") (pinfunction "1_2") (pintype "passive"))
      (node (ref "R21") (pin "5") (pinfunction "2_5") (pintype "passive"))
      (node (ref "R21") (pin "6") (pinfunction "2_6") (pintype "passive"))
      (node (ref "R22") (pin "1") (pinfunction "1_1") (pintype "passive"))
      (node (ref "R26") (pin "2") (pinfunction "2_2") (pintype "passive"))
      (node (ref "R29") (pin "5") (pinfunction "2_5") (pintype "passive"))
      (node (ref "R29") (pin "6") (pinfunction "2_6") (pintype "passive"))
      (node (ref "R5") (pin "1") (pinfunction "1_1") (pintype "passive"))
      (node (ref "R6") (pin "1") (pinfunction "1_1") (pintype "passive"))
      (node (ref "TP11") (pin "P$1") (pinfunction "TP_P$1") (pintype "passive"))
      (node (ref "TP12") (pin "1") (pinfunction "TP_1") (pintype "passive"))
      (node (ref "TP66") (pin "TP") (pinfunction "TP_TP") (pintype "input"))
      (node (ref "TP67") (pin "TP") (pinfunction "TP_TP") (pintype "input"))
      (node (ref "U1") (pin "10") (pinfunction "PGND_10") (pintype "bidirectional"))
      (node (ref "U1") (pin "21") (pinfunction "PRESB_21") (pintype "bidirectional"))
      (node (ref "U1") (pin "9") (pinfunction "SGND_9") (pintype "bidirectional"))
      (node (ref "U1") (pin "PAD") (pinfunction "PAD_PAD") (pintype "bidirectional"))
      (node (ref "U2") (pin "2") (pinfunction "GND_2") (pintype "bidirectional"))
      (node (ref "U2") (pin "3") (pinfunction "GND_3") (pintype "bidirectional"))
      (node (ref "U2") (pin "5") (pinfunction "INHIBIT_5") (pintype "bidirectional"))
      (node (ref "U2") (pin "6") (pinfunction "GND_6") (pintype "bidirectional"))
      (node (ref "U2") (pin "7") (pinfunction "GND_7") (pintype "bidirectional"))
      (node (ref "U3") (pin "3") (pinfunction "VSS_3") (pintype "bidirectional"))
      (node (ref "U6") (pin "16") (pinfunction "AGND_16") (pintype "power_in"))
      (node (ref "U6") (pin "9") (pinfunction "PGND_9") (pintype "power_in"))
      (node (ref "U6") (pin "EP") (pinfunction "PPAD_EP") (pintype "power_in"))
      (node (ref "U7") (pin "16") (pinfunction "AGND_16") (pintype "power_in"))
      (node (ref "U7") (pin "9") (pinfunction "PGND_9") (pintype "power_in"))
      (node (ref "U7") (pin "EP") (pinfunction "PPAD_EP") (pintype "power_in"))
      (node (ref "X1") (pin "7") (pinfunction "1_7") (pintype "passive"))
      (node (ref "X1") (pin "8") (pinfunction "1_8") (pintype "passive"))
      (node (ref "X2") (pin "4") (pinfunction "4_4") (pintype "passive"))
    )
    (net (code "53") (name "DIN_SM") (class "Default")
      (node (ref "IC3") (pin "6") (pinfunction "RC1/CN45/RPI38_6") (pintype "bidirectional"))
      (node (ref "U1") (pin "27") (pinfunction "DIN_27") (pintype "bidirectional"))
    )
    (net (code "54") (name "DOOR2_L") (class "Default")
      (node (ref "IC3") (pin "50") (pinfunction "CN18/RP17/RF5_50") (pintype "bidirectional"))
      (node (ref "R29") (pin "2") (pinfunction "1_2") (pintype "passive"))
      (node (ref "R29") (pin "3") (pinfunction "1_3") (pintype "passive"))
    )
    (net (code "55") (name "DOOR2_L_SW") (class "Default")
      (node (ref "C36") (pin "1") (pinfunction "1_1") (pintype "passive"))
      (node (ref "J19") (pin "2") (pinfunction "2_2") (pintype "bidirectional"))
      (node (ref "R27") (pin "2") (pinfunction "2_2") (pintype "passive"))
      (node (ref "R29") (pin "7") (pinfunction "2_7") (pintype "passive"))
    )
    (net (code "56") (name "DOOR2_R") (class "Default")
      (node (ref "IC3") (pin "55") (pinfunction "CN72/RPI45/RF6_55") (pintype "bidirectional"))
      (node (ref "R29") (pin "1") (pinfunction "1_1") (pintype "passive"))
      (node (ref "R29") (pin "4") (pinfunction "1_4") (pintype "passive"))
    )
    (net (code "57") (name "DOOR2_R_SW") (class "Default")
      (node (ref "C47") (pin "1") (pinfunction "1_1") (pintype "passive"))
      (node (ref "J19") (pin "4") (pinfunction "4_4") (pintype "bidirectional"))
      (node (ref "R28") (pin "2") (pinfunction "2_2") (pintype "passive"))
      (node (ref "R29") (pin "8") (pinfunction "2_8") (pintype "passive"))
    )
    (net (code "58") (name "DOOR_L") (class "Default")
      (node (ref "IC3") (pin "73") (pinfunction "RC13/SOSCI/CN1_73") (pintype "bidirectional"))
      (node (ref "R21") (pin "2") (pinfunction "1_2") (pintype "passive"))
      (node (ref "R21") (pin "3") (pinfunction "1_3") (pintype "passive"))
    )
    (net (code "59") (name "DOOR_L_SW") (class "Default")
      (node (ref "C25") (pin "1") (pinfunction "1_1") (pintype "passive"))
      (node (ref "J19") (pin "6") (pinfunction "6_6") (pintype "bidirectional"))
      (node (ref "R18") (pin "2") (pinfunction "2_2") (pintype "passive"))
      (node (ref "R21") (pin "7") (pinfunction "2_7") (pintype "passive"))
    )
    (net (code "60") (name "DOOR_ON") (class "Default")
      (node (ref "IC3") (pin "87") (pinfunction "CN68/RF0_87") (pintype "bidirectional"))
      (node (ref "Q5") (pin "5") (pinfunction "Q1G_5") (pintype "input"))
      (node (ref "R20") (pin "7") (pinfunction "2_7") (pintype "passive"))
    )
    (net (code "61") (name "DOOR_R") (class "Default")
      (node (ref "IC3") (pin "91") (pinfunction "RA6/CN39_91") (pintype "bidirectional"))
      (node (ref "R21") (pin "1") (pinfunction "1_1") (pintype "passive"))
      (node (ref "R21") (pin "4") (pinfunction "1_4") (pintype "passive"))
    )
    (net (code "62") (name "DOOR_R_SW") (class "Default")
      (node (ref "C26") (pin "1") (pinfunction "1_1") (pintype "passive"))
      (node (ref "J19") (pin "8") (pinfunction "8_8") (pintype "bidirectional"))
      (node (ref "R19") (pin "2") (pinfunction "2_2") (pintype "passive"))
      (node (ref "R21") (pin "8") (pinfunction "2_8") (pintype "passive"))
    )
    (net (code "63") (name "DOUT_SM_B") (class "Default")
      (node (ref "IC3") (pin "7") (pinfunction "RC2/CN46/RPI39_7") (pintype "bidirectional"))
      (node (ref "U1") (pin "28") (pinfunction "DOUT_28") (pintype "bidirectional"))
    )
    (net (code "64") (name "ID1_L_N") (class "Default")
      (node (ref "C31") (pin "2") (pinfunction "2_2") (pintype "passive"))
      (node (ref "IC9") (pin "3") (pinfunction "FB_3") (pintype "input"))
      (node (ref "J14") (pin "1") (pinfunction "1_1") (pintype "passive"))
      (node (ref "J18") (pin "8") (pinfunction "8_8") (pintype "bidirectional"))
      (node (ref "R26") (pin "1") (pinfunction "1_1") (pintype "passive"))
    )
    (net (code "65") (name "ID_L_P") (class "Default")
      (node (ref "C31") (pin "1") (pinfunction "1_1") (pintype "passive"))
      (node (ref "C32") (pin "1") (pinfunction "1_1") (pintype "passive"))
      (node (ref "D3") (pin "A") (pinfunction "A_A") (pintype "passive"))
      (node (ref "J14") (pin "2") (pinfunction "2_2") (pintype "passive"))
      (node (ref "J18") (pin "7") (pinfunction "7_7") (pintype "bidirectional"))
      (node (ref "L3") (pin "2") (pinfunction "2_2") (pintype "passive"))
    )
    (net (code "66") (name "ID_PWM") (class "Default")
      (node (ref "IC3") (pin "51") (pinfunction "CN71/RP16/RF3_51") (pintype "bidirectional"))
      (node (ref "R23") (pin "1") (pinfunction "1_1") (pintype "passive"))
    )
    (net (code "67") (name "IOB") (class "Default")
      (node (ref "J10") (pin "C7") (pinfunction "C7_C7") (pintype "bidirectional"))
      (node (ref "U1") (pin "20") (pinfunction "IOB_20") (pintype "bidirectional"))
    )
    (net (code "68") (name "ISENSEA") (class "Default")
      (node (ref "IC19") (pin "1") (pinfunction "OUT_1") (pintype "output"))
      (node (ref "IC19") (pin "2") (pinfunction "-IN_2") (pintype "input"))
      (node (ref "IC3") (pin "43") (pinfunction "RB14/AN14/CN32/RP14_43") (pintype "bidirectional"))
    )
    (net (code "69") (name "ISEN_OP_EN") (class "Default")
      (node (ref "C134") (pin "1") (pinfunction "1_1") (pintype "passive"))
      (node (ref "IC19") (pin "8") (pinfunction "V+_8") (pintype "power_in"))
      (node (ref "IC3") (pin "68") (pinfunction "CN53/RP2/RD8_68") (pintype "bidirectional"))
    )
    (net (code "70") (name "LD_SM") (class "Default")
      (node (ref "IC3") (pin "9") (pinfunction "RC4/CN48/RPI41_9") (pintype "bidirectional"))
      (node (ref "U1") (pin "25") (pinfunction "/LD_25") (pintype "bidirectional"))
    )
    (net (code "71") (name "MICROPHONE") (class "Default")
      (node (ref "J17") (pin "2") (pinfunction "2_2") (pintype "bidirectional"))
      (node (ref "J48") (pin "2") (pinfunction "2_2") (pintype "passive"))
      (node (ref "R207") (pin "2") (pinfunction "2_2") (pintype "passive"))
      (node (ref "R208") (pin "1") (pinfunction "1_1") (pintype "passive"))
      (node (ref "U9") (pin "3") (pinfunction "+IN_3") (pintype "input"))
    )
    (net (code "72") (name "MIC_AMP_EN") (class "Default")
      (node (ref "IC3") (pin "96") (pinfunction "CN79/RG12_96") (pintype "bidirectional"))
      (node (ref "J49") (pin "1") (pinfunction "1_1") (pintype "passive"))
      (node (ref "Q24") (pin "1") (pinfunction "G_1") (pintype "passive"))
      (node (ref "R210") (pin "1") (pinfunction "1_1") (pintype "passive"))
      (node (ref "U9") (pin "5") (pinfunction "~{SHDN}_5") (pintype "power_in"))
    )
    (net (code "73") (name "N$5") (class "Default")
      (node (ref "J15") (pin "6") (pinfunction "6_6") (pintype "bidirectional"))
      (node (ref "J15") (pin "6A") (pinfunction "6_6A") (pintype "bidirectional"))
      (node (ref "J15") (pin "8") (pinfunction "8_8") (pintype "bidirectional"))
      (node (ref "J15") (pin "8A") (pinfunction "8_8A") (pintype "bidirectional"))
      (node (ref "R38") (pin "2") (pinfunction "2_2") (pintype "passive"))
    )
    (net (code "74") (name "N$10") (class "Default")
      (node (ref "IC19") (pin "3") (pinfunction "+IN_3") (pintype "input"))
      (node (ref "IC19") (pin "5") (pinfunction "+IN_5") (pintype "input"))
      (node (ref "Q14") (pin "3") (pinfunction "OUT_3") (pintype "output"))
    )
    (net (code "75") (name "N$41") (class "Default")
      (node (ref "J15") (pin "2") (pinfunction "2_2") (pintype "bidirectional"))
      (node (ref "J15") (pin "2A") (pinfunction "2_2A") (pintype "bidirectional"))
      (node (ref "J15") (pin "4") (pinfunction "4_4") (pintype "bidirectional"))
      (node (ref "J15") (pin "4A") (pinfunction "4_4A") (pintype "bidirectional"))
      (node (ref "R39") (pin "2") (pinfunction "2_2") (pintype "passive"))
    )
    (net (code "76") (name "Net-(C164-Pad1)") (class "Default")
      (node (ref "C164") (pin "1") (pinfunction "1_1") (pintype "passive"))
      (node (ref "R193") (pin "1") (pinfunction "1_1") (pintype "passive"))
    )
    (net (code "77") (name "Net-(C171-Pad1)") (class "Default")
      (node (ref "C171") (pin "1") (pinfunction "1_1") (pintype "passive"))
      (node (ref "R198") (pin "1") (pinfunction "1_1") (pintype "passive"))
      (node (ref "R199") (pin "2") (pinfunction "2_2") (pintype "passive"))
      (node (ref "U8") (pin "7") (pinfunction "AVCC_7") (pintype "power_in"))
    )
    (net (code "78") (name "Net-(C185-Pad2)") (class "Default")
      (node (ref "C185") (pin "2") (pinfunction "2_2") (pintype "passive"))
      (node (ref "R211") (pin "1") (pinfunction "1_1") (pintype "passive"))
    )
    (net (code "79") (name "Net-(D1-A1)") (class "Default")
      (node (ref "B1") (pin "+") (pinfunction "+_+") (pintype "passive"))
      (node (ref "D1") (pin "1") (pinfunction "A1_1") (pintype "passive"))
      (node (ref "TP7") (pin "P$1") (pinfunction "TP_P$1") (pintype "passive"))
    )
    (net (code "80") (name "Net-(D1-K)") (class "Default")
      (node (ref "C24") (pin "1") (pinfunction "1_1") (pintype "passive"))
      (node (ref "D1") (pin "3") (pinfunction "K_3") (pintype "passive"))
      (node (ref "IC7") (pin "14") (pinfunction "VDD_14") (pintype "power_in"))
    )
    (net (code "81") (name "Net-(D2-K)") (class "Default")
      (node (ref "C30") (pin "1") (pinfunction "1_1") (pintype "passive"))
      (node (ref "D2") (pin "C") (pinfunction "K_C") (pintype "passive"))
      (node (ref "D3") (pin "C") (pinfunction "K_C") (pintype "passive"))
      (node (ref "IC9") (pin "1") (pinfunction "BOOST_1") (pintype "input"))
    )
    (net (code "82") (name "Net-(D17-A)") (class "Default")
      (node (ref "D17") (pin "2") (pinfunction "A_2") (pintype "passive"))
      (node (ref "R151") (pin "1") (pinfunction "1_1") (pintype "passive"))
    )
    (net (code "83") (name "Net-(D17-K)") (class "Default")
      (node (ref "D17") (pin "1+") (pinfunction "K_1+") (pintype "passive"))
      (node (ref "IC18") (pin "22") (pinfunction "GPIO0_22") (pintype "output"))
    )
    (net (code "84") (name "Net-(D19-A)") (class "Default")
      (node (ref "D19") (pin "2") (pinfunction "A_2") (pintype "passive"))
      (node (ref "R152") (pin "1") (pinfunction "1_1") (pintype "passive"))
    )
    (net (code "85") (name "Net-(D19-K)") (class "Default")
      (node (ref "D19") (pin "1+") (pinfunction "K_1+") (pintype "passive"))
      (node (ref "IC18") (pin "23") (pinfunction "GPIO1_23") (pintype "output"))
    )
    (net (code "86") (name "Net-(D23-A)") (class "Default")
      (node (ref "D23") (pin "2") (pinfunction "A_2") (pintype "passive"))
      (node (ref "R175") (pin "1") (pinfunction "1_1") (pintype "passive"))
    )
    (net (code "87") (name "Net-(D24-A)") (class "Default")
      (node (ref "D24") (pin "2") (pinfunction "A_2") (pintype "passive"))
      (node (ref "R176") (pin "1") (pinfunction "1_1") (pintype "passive"))
    )
    (net (code "88") (name "Net-(IC1-VIN)") (class "Default")
      (node (ref "C23") (pin "1") (pinfunction "1_1") (pintype "passive"))
      (node (ref "C59") (pin "1") (pinfunction "1_1") (pintype "passive"))
      (node (ref "IC1") (pin "1") (pinfunction "VIN_1") (pintype "power_in"))
      (node (ref "R37") (pin "1") (pinfunction "1_1") (pintype "passive"))
    )
    (net (code "89") (name "Net-(IC3-AVDD)") (class "Default")
      (node (ref "C3") (pin "1") (pinfunction "1_1") (pintype "passive"))
      (node (ref "C7") (pin "1") (pinfunction "1_1") (pintype "passive"))
      (node (ref "IC3") (pin "30") (pinfunction "AVDD_30") (pintype "power_in"))
      (node (ref "R1") (pin "1") (pinfunction "1_1") (pintype "passive"))
    )
    (net (code "90") (name "Net-(IC3-OSC1{slash}CLKI{slash}RC12)") (class "Default")
      (node (ref "C18") (pin "2") (pinfunction "2_2") (pintype "passive"))
      (node (ref "IC3") (pin "63") (pinfunction "OSC1/CLKI/RC12_63") (pintype "bidirectional"))
      (node (ref "Q4") (pin "3") (pinfunction "2_3") (pintype "passive"))
    )
    (net (code "91") (name "Net-(IC3-OSC2{slash}CLKO{slash}RC15)") (class "Default")
      (node (ref "C19") (pin "2") (pinfunction "2_2") (pintype "passive"))
      (node (ref "IC3") (pin "64") (pinfunction "OSC2/CLKO/RC15_64") (pintype "bidirectional"))
      (node (ref "Q4") (pin "1") (pinfunction "1_1") (pintype "passive"))
    )
    (net (code "92") (name "Net-(IC3-RA4{slash}TDI{slash}CN37)") (class "Default")
      (node (ref "IC3") (pin "60") (pinfunction "RA4/TDI/CN37_60") (pintype "bidirectional"))
      (node (ref "TP2") (pin "P$1") (pinfunction "TP_P$1") (pintype "passive"))
    )
    (net (code "93") (name "Net-(IC3-RB10{slash}AN10{slash}CN28{slash}CVREF)") (class "Default")
      (node (ref "IC3") (pin "34") (pinfunction "RB10/AN10/CN28/CVREF_34") (pintype "bidirectional"))
      (node (ref "TP3") (pin "P$1") (pinfunction "TP_P$1") (pintype "passive"))
    )
    (net (code "94") (name "Net-(IC3-VDDCORE)") (class "Default")
      (node (ref "C10") (pin "2") (pinfunction "2_2") (pintype "passive"))
      (node (ref "C38") (pin "2") (pinfunction "2_2") (pintype "passive"))
      (node (ref "IC3") (pin "85") (pinfunction "VDDCORE_85") (pintype "passive"))
    )
    (net (code "95") (name "Net-(IC4-VDD)") (class "Default")
      (node (ref "C21") (pin "1") (pinfunction "1_1") (pintype "passive"))
      (node (ref "IC4") (pin "5") (pinfunction "VDD_5") (pintype "power_in"))
      (node (ref "J12") (pin "2") (pinfunction "2_2") (pintype "passive"))
      (node (ref "R15") (pin "1") (pinfunction "1_1") (pintype "passive"))
    )
    (net (code "96") (name "Net-(IC7-OSCI)") (class "Default")
      (node (ref "IC7") (pin "1") (pinfunction "OSCI_1") (pintype "input"))
      (node (ref "Q6") (pin "2") (pinfunction "2_2") (pintype "passive"))
    )
    (net (code "97") (name "Net-(IC7-OSCO)") (class "Default")
      (node (ref "IC7") (pin "2") (pinfunction "OSCO_2") (pintype "output"))
      (node (ref "Q6") (pin "1") (pinfunction "1_1") (pintype "passive"))
    )
    (net (code "98") (name "Net-(IC9-EN{slash}DIM)") (class "Default")
      (node (ref "C34") (pin "1") (pinfunction "1_1") (pintype "passive"))
      (node (ref "IC9") (pin "4") (pinfunction "EN/DIM_4") (pintype "input"))
      (node (ref "R23") (pin "2") (pinfunction "2_2") (pintype "passive"))
    )
    (net (code "99") (name "Net-(IC9-SW)") (class "Default")
      (node (ref "C30") (pin "2") (pinfunction "2_2") (pintype "passive"))
      (node (ref "D4") (pin "K") (pinfunction "K_K") (pintype "passive"))
      (node (ref "IC9") (pin "6") (pinfunction "SW_6") (pintype "output"))
      (node (ref "L3") (pin "1") (pinfunction "1_1") (pintype "passive"))
    )
    (net (code "100") (name "Net-(IC18-VCC30)") (class "Default")
      (node (ref "C121") (pin "2") (pinfunction "2_2") (pintype "passive"))
      (node (ref "IC18") (pin "17") (pinfunction "VCC30_17") (pintype "power_in"))
      (node (ref "IC18") (pin "4") (pinfunction "VCCIO_4") (pintype "power_in"))
      (node (ref "TP60") (pin "P$1") (pinfunction "TP_P$1") (pintype "passive"))
    )
    (net (code "101") (name "Net-(IC19B--IN)") (class "Default")
      (node (ref "IC19") (pin "6") (pinfunction "-IN_6") (pintype "input"))
      (node (ref "IC19") (pin "7") (pinfunction "OUT_7") (pintype "output"))
    )
    (net (code "102") (name "Net-(IC21-ITH)") (class "Default")
      (node (ref "IC21") (pin "2") (pinfunction "ITH_2") (pintype "input"))
      (node (ref "R193") (pin "2") (pinfunction "2_2") (pintype "passive"))
    )
    (net (code "103") (name "Net-(IC21-PGATE)") (class "Default")
      (node (ref "IC21") (pin "5") (pinfunction "PGATE_5") (pintype "output"))
      (node (ref "Q23") (pin "1") (pinfunction "G_1") (pintype "passive"))
    )
    (net (code "104") (name "Net-(IC21-SENSE)") (class "Default")
      (node (ref "C155") (pin "2") (pinfunction "2_2") (pintype "passive"))
      (node (ref "IC21") (pin "7") (pinfunction "SENSE_7") (pintype "input"))
      (node (ref "Q23") (pin "2") (pinfunction "S_2") (pintype "passive"))
      (node (ref "R189") (pin "1") (pinfunction "1_1") (pintype "passive"))
    )
    (net (code "105") (name "Net-(IC21-VFB)") (class "Default")
      (node (ref "C160") (pin "1") (pinfunction "1_1") (pintype "passive"))
      (node (ref "IC21") (pin "3") (pinfunction "VFB_3") (pintype "input"))
      (node (ref "R194") (pin "2") (pinfunction "2_2") (pintype "passive"))
      (node (ref "R197") (pin "1") (pinfunction "1_1") (pintype "passive"))
    )
    (net (code "106") (name "Net-(J45-Pad2)") (class "Default")
      (node (ref "J45") (pin "2") (pinfunction "2_2") (pintype "passive"))
      (node (ref "R46") (pin "2") (pinfunction "2_2") (pintype "passive"))
    )
    (net (code "107") (name "Net-(J45-Pad3)") (class "Default")
      (node (ref "J45") (pin "3") (pinfunction "3_3") (pintype "passive"))
      (node (ref "R45") (pin "2") (pinfunction "2_2") (pintype "passive"))
    )
    (net (code "108") (name "Net-(Q2-Q2G)") (class "Default")
      (node (ref "Q2") (pin "6") (pinfunction "Q2G_6") (pintype "input"))
      (node (ref "R3") (pin "2") (pinfunction "2_2") (pintype "passive"))
    )
    (net (code "109") (name "Net-(Q5-Q2D1)") (class "Default")
      (node (ref "Q5") (pin "2") (pinfunction "Q2D1_2") (pintype "bidirectional"))
      (node (ref "Q5") (pin "3") (pinfunction "Q2D2_3") (pintype "bidirectional"))
      (node (ref "R18") (pin "1") (pinfunction "1_1") (pintype "passive"))
      (node (ref "R19") (pin "1") (pinfunction "1_1") (pintype "passive"))
      (node (ref "R27") (pin "1") (pinfunction "1_1") (pintype "passive"))
      (node (ref "R28") (pin "1") (pinfunction "1_1") (pintype "passive"))
    )
    (net (code "110") (name "Net-(Q5-Q2G)") (class "Default")
      (node (ref "Q5") (pin "6") (pinfunction "Q2G_6") (pintype "input"))
      (node (ref "R20") (pin "3") (pinfunction "1_3") (pintype "passive"))
    )
    (net (code "111") (name "Net-(Q14-VIN+)") (class "Default")
      (node (ref "C187") (pin "+") (pinfunction "+_+") (pintype "passive"))
      (node (ref "D32") (pin "C") (pinfunction "C_C") (pintype "passive"))
      (node (ref "F3") (pin "2") (pinfunction "2_2") (pintype "passive"))
      (node (ref "Q14") (pin "5") (pinfunction "VIN+_5") (pintype "input"))
      (node (ref "R154") (pin "1") (pinfunction "1_1") (pintype "passive"))
      (node (ref "R40") (pin "1") (pinfunction "1_1") (pintype "passive"))
      (node (ref "R41") (pin "1") (pinfunction "1_1") (pintype "passive"))
      (node (ref "TP63") (pin "TP") (pinfunction "TP_TP") (pintype "input"))
    )
    (net (code "112") (name "Net-(Q15A-D)") (class "Default")
      (node (ref "Q15") (pin "7") (pinfunction "D_7") (pintype "passive"))
      (node (ref "Q15") (pin "8") (pinfunction "D1_8") (pintype "passive"))
      (node (ref "R159") (pin "1") (pinfunction "1_1") (pintype "passive"))
    )
    (net (code "113") (name "Net-(Q15B-D)") (class "Default")
      (node (ref "C122") (pin "1") (pinfunction "1_1") (pintype "passive"))
      (node (ref "C123") (pin "1") (pinfunction "1_1") (pintype "passive"))
      (node (ref "C125") (pin "1") (pinfunction "1_1") (pintype "passive"))
      (node (ref "Q15") (pin "5") (pinfunction "D_5") (pintype "passive"))
      (node (ref "Q15") (pin "6") (pinfunction "D1_6") (pintype "passive"))
      (node (ref "R157") (pin "2") (pinfunction "2_2") (pintype "passive"))
      (node (ref "R42") (pin "1") (pinfunction "1_1") (pintype "passive"))
      (node (ref "R43") (pin "1") (pinfunction "1_1") (pintype "passive"))
      (node (ref "U6") (pin "7") (pinfunction "VIN_7") (pintype "power_in"))
    )
    (net (code "114") (name "Net-(Q15B-G)") (class "Default")
      (node (ref "Q15") (pin "4") (pinfunction "G_4") (pintype "passive"))
      (node (ref "R156") (pin "1") (pinfunction "1_1") (pintype "passive"))
      (node (ref "R159") (pin "2") (pinfunction "2_2") (pintype "passive"))
    )
    (net (code "115") (name "Net-(Q18A-D)") (class "Default")
      (node (ref "Q18") (pin "7") (pinfunction "D_7") (pintype "passive"))
      (node (ref "Q18") (pin "8") (pinfunction "D1_8") (pintype "passive"))
      (node (ref "R173") (pin "2") (pinfunction "2_2") (pintype "passive"))
    )
    (net (code "116") (name "Net-(Q18B-D)") (class "Default")
      (node (ref "C136") (pin "1") (pinfunction "1_1") (pintype "passive"))
      (node (ref "C137") (pin "1") (pinfunction "1_1") (pintype "passive"))
      (node (ref "C139") (pin "1") (pinfunction "1_1") (pintype "passive"))
      (node (ref "Q18") (pin "5") (pinfunction "D_5") (pintype "passive"))
      (node (ref "Q18") (pin "6") (pinfunction "D1_6") (pintype "passive"))
      (node (ref "R171") (pin "2") (pinfunction "2_2") (pintype "passive"))
      (node (ref "R44") (pin "1") (pinfunction "1_1") (pintype "passive"))
      (node (ref "U7") (pin "7") (pinfunction "VIN_7") (pintype "power_in"))
    )
    (net (code "117") (name "Net-(Q18B-G)") (class "Default")
      (node (ref "Q18") (pin "4") (pinfunction "G_4") (pintype "passive"))
      (node (ref "R170") (pin "2") (pinfunction "2_2") (pintype "passive"))
      (node (ref "R173") (pin "1") (pinfunction "1_1") (pintype "passive"))
    )
    (net (code "118") (name "Net-(Q23-D)") (class "Default")
      (node (ref "D30") (pin "K") (pinfunction "K_K") (pintype "passive"))
      (node (ref "L14") (pin "1") (pinfunction "1_1") (pintype "passive"))
      (node (ref "Q23") (pin "3") (pinfunction "D_3") (pintype "passive"))
    )
    (net (code "119") (name "Net-(Q24-D)") (class "Default")
      (node (ref "Q24") (pin "3") (pinfunction "D_3") (pintype "passive"))
      (node (ref "R208") (pin "2") (pinfunction "2_2") (pintype "passive"))
    )
    (net (code "120") (name "Net-(R199-Pad1)") (class "Default")
      (node (ref "R199") (pin "1") (pinfunction "1_1") (pintype "passive"))
      (node (ref "U8") (pin "14") (pinfunction "AVCC_14") (pintype "power_in"))
    )
    (net (code "121") (name "Net-(TP69-TP)") (class "Default")
      (node (ref "R204") (pin "2") (pinfunction "2_2") (pintype "passive"))
      (node (ref "TP69") (pin "1") (pinfunction "TP_1") (pintype "passive"))
    )
    (net (code "122") (name "Net-(U1--UNDERV)") (class "Default")
      (node (ref "R12") (pin "1") (pinfunction "1_1") (pintype "passive"))
      (node (ref "U1") (pin "23") (pinfunction "-UNDERV_23") (pintype "bidirectional"))
    )
    (net (code "123") (name "Net-(U1-C+)") (class "Default")
      (node (ref "C15") (pin "2") (pinfunction "2_2") (pintype "passive"))
      (node (ref "U1") (pin "14") (pinfunction "C+_14") (pintype "bidirectional"))
    )
    (net (code "124") (name "Net-(U1-C-)") (class "Default")
      (node (ref "C15") (pin "1") (pinfunction "1_1") (pintype "passive"))
      (node (ref "U1") (pin "11") (pinfunction "C-_11") (pintype "bidirectional"))
    )
    (net (code "125") (name "Net-(U1-CLKB)") (class "Default")
      (node (ref "J10") (pin "C3") (pinfunction "C3_C3") (pintype "bidirectional"))
      (node (ref "U1") (pin "18") (pinfunction "CLKB_18") (pintype "bidirectional"))
    )
    (net (code "126") (name "Net-(U1-CPO)") (class "Default")
      (node (ref "C20") (pin "2") (pinfunction "2_2") (pintype "passive"))
      (node (ref "U1") (pin "15") (pinfunction "CPO_15") (pintype "bidirectional"))
    )
    (net (code "127") (name "Net-(U1-NC{slash}-NO)") (class "Default")
      (node (ref "R13") (pin "2") (pinfunction "2_2") (pintype "passive"))
      (node (ref "U1") (pin "22") (pinfunction "NC/-NO_22") (pintype "bidirectional"))
    )
    (net (code "128") (name "Net-(U1-RSTB)") (class "Default")
      (node (ref "J10") (pin "C2") (pinfunction "C2_C2") (pintype "bidirectional"))
      (node (ref "U1") (pin "19") (pinfunction "RSTB_19") (pintype "bidirectional"))
    )
    (net (code "129") (name "Net-(U1-VCCB)") (class "Default")
      (node (ref "J10") (pin "C1") (pinfunction "C1_C1") (pintype "bidirectional"))
      (node (ref "U1") (pin "17") (pinfunction "VCCB_17") (pintype "bidirectional"))
    )
    (net (code "130") (name "Net-(U3-AIN0)") (class "Default")
      (node (ref "C39") (pin "1") (pinfunction "1_1") (pintype "passive"))
      (node (ref "R33") (pin "1") (pinfunction "1_1") (pintype "passive"))
      (node (ref "R34") (pin "2") (pinfunction "2_2") (pintype "passive"))
      (node (ref "U3") (pin "4") (pinfunction "AIN0_4") (pintype "bidirectional"))
    )
    (net (code "131") (name "Net-(U3-AIN2)") (class "Default")
      (node (ref "C41") (pin "1") (pinfunction "1_1") (pintype "passive"))
      (node (ref "R35") (pin "1") (pinfunction "1_1") (pintype "passive"))
      (node (ref "R36") (pin "2") (pinfunction "2_2") (pintype "passive"))
      (node (ref "U3") (pin "6") (pinfunction "AIN2_6") (pintype "bidirectional"))
    )
    (net (code "132") (name "Net-(U9--IN)") (class "Default")
      (node (ref "C185") (pin "1") (pinfunction "1_1") (pintype "passive"))
      (node (ref "C186") (pin "1") (pinfunction "1_1") (pintype "passive"))
      (node (ref "R209") (pin "2") (pinfunction "2_2") (pintype "passive"))
      (node (ref "U9") (pin "4") (pinfunction "-IN_4") (pintype "input"))
    )
    (net (code "133") (name "Net-(U9-OUT)") (class "Default")
      (node (ref "C183") (pin "1") (pinfunction "1_1") (pintype "passive"))
      (node (ref "C184") (pin "1") (pinfunction "1_1") (pintype "passive"))
      (node (ref "C186") (pin "2") (pinfunction "2_2") (pintype "passive"))
      (node (ref "R209") (pin "1") (pinfunction "1_1") (pintype "passive"))
      (node (ref "U9") (pin "1") (pinfunction "OUT_1") (pintype "output"))
    )
    (net (code "134") (name "OUTN_UNF") (class "Default")
      (node (ref "C178") (pin "2") (pinfunction "2_2") (pintype "passive"))
      (node (ref "L16") (pin "2") (pinfunction "2_2") (pintype "passive"))
      (node (ref "U8") (pin "23") (pinfunction "OUTN_23") (pintype "output"))
      (node (ref "U8") (pin "25") (pinfunction "OUTN_25") (pintype "output"))
    )
    (net (code "135") (name "OUTP_UNF") (class "Default")
      (node (ref "C173") (pin "2") (pinfunction "2_2") (pintype "passive"))
      (node (ref "L15") (pin "2") (pinfunction "2_2") (pintype "passive"))
      (node (ref "U8") (pin "18") (pinfunction "OUTP_18") (pintype "output"))
      (node (ref "U8") (pin "20") (pinfunction "OUTP_20") (pintype "output"))
    )
    (net (code "136") (name "OUT_S1") (class "Default")
      (node (ref "D23") (pin "1+") (pinfunction "K_1+") (pintype "passive"))
      (node (ref "D25") (pin "A") (pinfunction "A_A") (pintype "passive"))
      (node (ref "J15") (pin "12") (pinfunction "12_12") (pintype "bidirectional"))
      (node (ref "J15") (pin "12A") (pinfunction "12_12A") (pintype "bidirectional"))
      (node (ref "Q20") (pin "3") (pinfunction "D_3") (pintype "passive"))
    )
    (net (code "137") (name "OUT_S2") (class "Default")
      (node (ref "D24") (pin "1+") (pinfunction "K_1+") (pintype "passive"))
      (node (ref "D26") (pin "A") (pinfunction "A_A") (pintype "passive"))
      (node (ref "J16") (pin "2") (pinfunction "2_2") (pintype "bidirectional"))
      (node (ref "J16") (pin "2A") (pinfunction "2_2A") (pintype "bidirectional"))
      (node (ref "Q21") (pin "3") (pinfunction "D_3") (pintype "passive"))
    )
    (net (code "138") (name "P12V") (class "Default")
      (node (ref "C128") (pin "1") (pinfunction "1_1") (pintype "passive"))
      (node (ref "C129") (pin "1") (pinfunction "1_1") (pintype "passive"))
      (node (ref "C130") (pin "1") (pinfunction "1_1") (pintype "passive"))
      (node (ref "C165") (pin "1") (pinfunction "1_1") (pintype "passive"))
      (node (ref "C166") (pin "1") (pinfunction "1_1") (pintype "passive"))
      (node (ref "C167") (pin "1") (pinfunction "1_1") (pintype "passive"))
      (node (ref "C168") (pin "1") (pinfunction "1_1") (pintype "passive"))
      (node (ref "C169") (pin "1") (pinfunction "1_1") (pintype "passive"))
      (node (ref "C170") (pin "1") (pinfunction "1_1") (pintype "passive"))
      (node (ref "C44") (pin "+") (pinfunction "+_+") (pintype "passive"))
      (node (ref "D20") (pin "K") (pinfunction "K_K") (pintype "passive"))
      (node (ref "J18") (pin "3") (pinfunction "3_3") (pintype "bidirectional"))
      (node (ref "J50") (pin "3") (pinfunction "3_3") (pintype "bidirectional"))
      (node (ref "J50") (pin "4") (pinfunction "4_4") (pintype "bidirectional"))
      (node (ref "Q16") (pin "1_2") (pinfunction "VIN_1_2") (pintype "passive"))
      (node (ref "R160") (pin "2") (pinfunction "2_2") (pintype "passive"))
      (node (ref "R198") (pin "2") (pinfunction "2_2") (pintype "passive"))
      (node (ref "TP61") (pin "TP") (pinfunction "TP_TP") (pintype "input"))
      (node (ref "U8") (pin "15") (pinfunction "PVCC_15") (pintype "power_in"))
      (node (ref "U8") (pin "16") (pinfunction "PVCC_16") (pintype "power_in"))
      (node (ref "U8") (pin "27") (pinfunction "PVCC_27") (pintype "power_in"))
      (node (ref "U8") (pin "28") (pinfunction "PVCC_28") (pintype "power_in"))
    )
    (net (code "139") (name "PGC") (class "Default")
      (node (ref "IC3") (pin "26") (pinfunction "RB6/AN6/PGC2/RP6_26") (pintype "bidirectional"))
      (node (ref "J11") (pin "5") (pinfunction "5_5") (pintype "passive"))
    )
    (net (code "140") (name "PGD") (class "Default")
      (node (ref "IC3") (pin "27") (pinfunction "RB7/AN7/PGD2/RP7_27") (pintype "bidirectional"))
      (node (ref "J11") (pin "4") (pinfunction "4_4") (pintype "passive"))
    )
    (net (code "141") (name "PHOTOCELL") (class "Default")
      (node (ref "R7") (pin "2") (pinfunction "2_2") (pintype "passive"))
      (node (ref "R8") (pin "2") (pinfunction "2_2") (pintype "passive"))
      (node (ref "TP6") (pin "P$1") (pinfunction "TP_P$1") (pintype "passive"))
    )
    (net (code "142") (name "PHOTO_PIN") (class "Default")
      (node (ref "IC3") (pin "24") (pinfunction "RB1/AN1/CN3/PGC1/RP1_24") (pintype "bidirectional"))
      (node (ref "R8") (pin "1") (pinfunction "1_1") (pintype "passive"))
    )
    (net (code "143") (name "PHOTO_PWR") (class "Default")
      (node (ref "IC3") (pin "25") (pinfunction "RB0/AN0/CN2/PGD1/RP0_25") (pintype "bidirectional"))
      (node (ref "R7") (pin "1") (pinfunction "1_1") (pintype "passive"))
    )
    (net (code "144") (name "PIC_INT") (class "Default")
      (node (ref "IC3") (pin "38") (pinfunction "RA1/TCK_38") (pintype "bidirectional"))
      (node (ref "J1") (pin "3") (pinfunction "3_3") (pintype "passive"))
    )
    (net (code "145") (name "RTC_CS") (class "Default")
      (node (ref "IC3") (pin "79") (pinfunction "CN57/RPI42/RD12_79") (pintype "bidirectional"))
      (node (ref "IC7") (pin "6") (pinfunction "CE_6") (pintype "input"))
      (node (ref "R22") (pin "2") (pinfunction "2_2") (pintype "passive"))
    )
    (net (code "146") (name "RTC_INT") (class "Default")
      (node (ref "IC3") (pin "80") (pinfunction "CN19/RD13_80") (pintype "bidirectional"))
      (node (ref "IC7") (pin "5") (pinfunction "/INT_5") (pintype "output"))
    )
    (net (code "147") (name "SBC_5V_VBUS") (class "Default")
      (node (ref "C114") (pin "2") (pinfunction "2_2") (pintype "passive"))
      (node (ref "C115") (pin "2") (pinfunction "2_2") (pintype "passive"))
      (node (ref "IC18") (pin "19") (pinfunction "/RESET_19") (pintype "bidirectional"))
      (node (ref "IC18") (pin "20") (pinfunction "VCC5I_20") (pintype "power_in"))
      (node (ref "J41") (pin "3") (pinfunction "3_3") (pintype "passive"))
      (node (ref "R151") (pin "2") (pinfunction "2_2") (pintype "passive"))
      (node (ref "R152") (pin "2") (pinfunction "2_2") (pintype "passive"))
      (node (ref "X2") (pin "1") (pinfunction "1_1") (pintype "passive"))
    )
    (net (code "148") (name "SBC_LINL") (class "Default")
      (node (ref "C184") (pin "2") (pinfunction "2_2") (pintype "passive"))
      (node (ref "J17") (pin "4") (pinfunction "4_4") (pintype "bidirectional"))
      (node (ref "J47") (pin "6") (pinfunction "6_6") (pintype "passive"))
    )
    (net (code "149") (name "SBC_LINR") (class "Default")
      (node (ref "C183") (pin "2") (pinfunction "2_2") (pintype "passive"))
      (node (ref "J17") (pin "5") (pinfunction "5_5") (pintype "bidirectional"))
      (node (ref "J47") (pin "2") (pinfunction "2_2") (pintype "passive"))
    )
    (net (code "150") (name "SBC_LOUTL") (class "Default")
      (node (ref "C175") (pin "1") (pinfunction "1_1") (pintype "passive"))
      (node (ref "J17") (pin "7") (pinfunction "7_7") (pintype "bidirectional"))
      (node (ref "J47") (pin "5") (pinfunction "5_5") (pintype "passive"))
    )
    (net (code "151") (name "SBC_LOUTR") (class "Default")
      (node (ref "C174") (pin "1") (pinfunction "1_1") (pintype "passive"))
      (node (ref "J17") (pin "8") (pinfunction "8_8") (pintype "bidirectional"))
      (node (ref "J47") (pin "1") (pinfunction "1_1") (pintype "passive"))
    )
    (net (code "152") (name "SBC_USB_B_D_N") (class "Default")
      (node (ref "IC18") (pin "16") (pinfunction "USBDM_16") (pintype "bidirectional"))
      (node (ref "X2") (pin "2") (pinfunction "2_2") (pintype "passive"))
    )
    (net (code "153") (name "SBC_USB_B_D_P") (class "Default")
      (node (ref "IC18") (pin "15") (pinfunction "USBDP_15") (pintype "bidirectional"))
      (node (ref "X2") (pin "3") (pinfunction "3_3") (pintype "passive"))
    )
    (net (code "154") (name "SCL1") (class "Default")
      (node (ref "IC3") (pin "57") (pinfunction "RG2/SCL1/CN83_57") (pintype "bidirectional"))
      (node (ref "IC5") (pin "2") (pinfunction "SCL_2") (pintype "input"))
      (node (ref "IC6") (pin "6") (pinfunction "SCL_6") (pintype "input"))
      (node (ref "J8") (pin "16") (pinfunction "16_16") (pintype "passive"))
      (node (ref "R30") (pin "2") (pinfunction "2_2") (pintype "passive"))
      (node (ref "R32") (pin "1") (pinfunction "1_1") (pintype "passive"))
      (node (ref "U3") (pin "1") (pinfunction "ADDR_1") (pintype "bidirectional"))
      (node (ref "U3") (pin "10") (pinfunction "SCL_10") (pintype "bidirectional"))
    )
    (net (code "155") (name "SCLK1") (class "Default")
      (node (ref "IC3") (pin "77") (pinfunction "CN51/RP23/RD2_77") (pintype "bidirectional"))
      (node (ref "IC7") (pin "10") (pinfunction "SCL_10") (pintype "input"))
      (node (ref "IC8") (pin "6") (pinfunction "C_6") (pintype "input"))
    )
    (net (code "156") (name "SCLK2") (class "Default")
      (node (ref "IC3") (pin "10") (pinfunction "RG6/CN8/RP21_10") (pintype "bidirectional"))
      (node (ref "J1") (pin "5") (pinfunction "5_5") (pintype "passive"))
      (node (ref "J8") (pin "12") (pinfunction "12_12") (pintype "passive"))
      (node (ref "U1") (pin "31") (pinfunction "ASYNC_31") (pintype "bidirectional"))
    )
    (net (code "157") (name "SCLK_SM_B") (class "Default")
      (node (ref "IC3") (pin "8") (pinfunction "RC3/CN47/RPI40_8") (pintype "bidirectional"))
      (node (ref "U1") (pin "26") (pinfunction "SCLK_26") (pintype "bidirectional"))
    )
    (net (code "158") (name "SDA1") (class "Default")
      (node (ref "IC3") (pin "56") (pinfunction "RG3/SDA1/CN84_56") (pintype "bidirectional"))
      (node (ref "IC5") (pin "1") (pinfunction "SDA_1") (pintype "bidirectional"))
      (node (ref "IC6") (pin "5") (pinfunction "SDA_5") (pintype "bidirectional"))
      (node (ref "J8") (pin "15") (pinfunction "15_15") (pintype "passive"))
      (node (ref "R25") (pin "2") (pinfunction "2_2") (pintype "passive"))
      (node (ref "R31") (pin "1") (pinfunction "1_1") (pintype "passive"))
      (node (ref "U3") (pin "9") (pinfunction "SDA_9") (pintype "bidirectional"))
    )
    (net (code "159") (name "SDI1") (class "Default")
      (node (ref "IC3") (pin "72") (pinfunction "CN49/RP11/RD0_72") (pintype "bidirectional"))
      (node (ref "IC7") (pin "8") (pinfunction "SDO_8") (pintype "output"))
      (node (ref "IC8") (pin "2") (pinfunction "Q_2") (pintype "bidirectional"))
    )
    (net (code "160") (name "SDI2") (class "Default")
      (node (ref "IC3") (pin "11") (pinfunction "RG7/CN9/RP26_11") (pintype "bidirectional"))
      (node (ref "J1") (pin "8") (pinfunction "8_8") (pintype "passive"))
      (node (ref "J8") (pin "11") (pinfunction "11_11") (pintype "passive"))
    )
    (net (code "161") (name "SDO1") (class "Default")
      (node (ref "IC3") (pin "76") (pinfunction "CN50/RP24/RD1_76") (pintype "bidirectional"))
      (node (ref "IC7") (pin "9") (pinfunction "SDI_9") (pintype "input"))
      (node (ref "IC8") (pin "5") (pinfunction "D_5") (pintype "input"))
    )
    (net (code "162") (name "SDO2") (class "Default")
      (node (ref "IC3") (pin "12") (pinfunction "CN10/RP19/RG8_12") (pintype "bidirectional"))
      (node (ref "J1") (pin "6") (pinfunction "6_6") (pintype "passive"))
      (node (ref "J8") (pin "14") (pinfunction "14_14") (pintype "passive"))
    )
    (net (code "163") (name "SMB_SCL") (class "Default")
      (node (ref "D31") (pin "6") (pinfunction "AK_6") (pintype "passive"))
      (node (ref "IC3") (pin "66") (pinfunction "RA14/RPI36/CN43_66") (pintype "bidirectional"))
      (node (ref "R190") (pin "1") (pinfunction "1_1") (pintype "passive"))
      (node (ref "R46") (pin "1") (pinfunction "1_1") (pintype "passive"))
    )
    (net (code "164") (name "SMB_SDA") (class "Default")
      (node (ref "D31") (pin "3") (pinfunction "AK_3") (pintype "passive"))
      (node (ref "IC3") (pin "67") (pinfunction "RA15/RPI35/CN44_67") (pintype "bidirectional"))
      (node (ref "R187") (pin "1") (pinfunction "1_1") (pintype "passive"))
      (node (ref "R45") (pin "1") (pinfunction "1_1") (pintype "passive"))
    )
    (net (code "165") (name "SM_C4A") (class "Default")
      (node (ref "J3") (pin "2") (pinfunction "2_2") (pintype "bidirectional"))
      (node (ref "U1") (pin "4") (pinfunction "C4A_4") (pintype "bidirectional"))
      (node (ref "X1") (pin "2") (pinfunction "1_2") (pintype "passive"))
    )
    (net (code "166") (name "SM_C8A") (class "Default")
      (node (ref "J3") (pin "1") (pinfunction "1_1") (pintype "bidirectional"))
      (node (ref "U1") (pin "3") (pinfunction "C8A_3") (pintype "bidirectional"))
      (node (ref "X1") (pin "1") (pinfunction "1_1") (pintype "passive"))
    )
    (net (code "167") (name "SM_CLK_A") (class "Default")
      (node (ref "J3") (pin "4") (pinfunction "4_4") (pintype "bidirectional"))
      (node (ref "U1") (pin "7") (pinfunction "CLKA_7") (pintype "bidirectional"))
      (node (ref "X1") (pin "4") (pinfunction "1_4") (pintype "passive"))
    )
    (net (code "168") (name "SM_DATA") (class "Default")
      (node (ref "IC3") (pin "14") (pinfunction "CN11/RP27/RG9_14") (pintype "bidirectional"))
      (node (ref "U1") (pin "29") (pinfunction "DATA_29") (pintype "bidirectional"))
    )
    (net (code "169") (name "SM_DET_A") (class "Default")
      (node (ref "J3") (pin "10") (pinfunction "10_10") (pintype "bidirectional"))
      (node (ref "U1") (pin "2") (pinfunction "PRESA_2") (pintype "bidirectional"))
      (node (ref "X1") (pin "10") (pinfunction "1_10") (pintype "passive"))
    )
    (net (code "170") (name "SM_IO_A") (class "Default")
      (node (ref "J3") (pin "3") (pinfunction "3_3") (pintype "bidirectional"))
      (node (ref "U1") (pin "5") (pinfunction "IOA_5") (pintype "bidirectional"))
      (node (ref "X1") (pin "3") (pinfunction "1_3") (pintype "passive"))
    )
    (net (code "171") (name "SM_RST") (class "Default")
      (node (ref "IC3") (pin "5") (pinfunction "CN65/SDA3/RE7_5") (pintype "bidirectional"))
      (node (ref "U1") (pin "30") (pinfunction "RIN_30") (pintype "bidirectional"))
    )
    (net (code "172") (name "SM_RST_A") (class "Default")
      (node (ref "J3") (pin "6") (pinfunction "6_6") (pintype "bidirectional"))
      (node (ref "U1") (pin "6") (pinfunction "RSTA_6") (pintype "bidirectional"))
      (node (ref "X1") (pin "6") (pinfunction "1_6") (pintype "passive"))
    )
    (net (code "173") (name "SM_SYNC") (class "Default")
      (node (ref "IC3") (pin "4") (pinfunction "CN64/SCL3/RE6_4") (pintype "bidirectional"))
      (node (ref "U1") (pin "32") (pinfunction "SYNC_32") (pintype "bidirectional"))
    )
    (net (code "174") (name "SM_VCC_A") (class "Default")
      (node (ref "J3") (pin "9") (pinfunction "9_9") (pintype "bidirectional"))
      (node (ref "U1") (pin "8") (pinfunction "VCCA_8") (pintype "bidirectional"))
      (node (ref "X1") (pin "9") (pinfunction "1_9") (pintype "passive"))
    )
    (net (code "175") (name "SPKR1_P") (class "Default")
      (node (ref "C176") (pin "1") (pinfunction "1_1") (pintype "passive"))
      (node (ref "J17") (pin "11") (pinfunction "11_11") (pintype "bidirectional"))
      (node (ref "J4") (pin "1") (pinfunction "1_1") (pintype "passive"))
      (node (ref "L15") (pin "1") (pinfunction "1_1") (pintype "passive"))
    )
    (net (code "176") (name "SPKR_N") (class "Default")
      (node (ref "C179") (pin "1") (pinfunction "1_1") (pintype "passive"))
      (node (ref "J17") (pin "10") (pinfunction "10_10") (pintype "bidirectional"))
      (node (ref "J4") (pin "2") (pinfunction "2_2") (pintype "passive"))
      (node (ref "L16") (pin "1") (pinfunction "1_1") (pintype "passive"))
    )
    (net (code "177") (name "STRIKE_EN") (class "Default")
      (node (ref "IC3") (pin "47") (pinfunction "CN20/RPI43/RD14_47") (pintype "bidirectional"))
      (node (ref "Q18") (pin "2") (pinfunction "G_2") (pintype "passive"))
      (node (ref "R174") (pin "1") (pinfunction "1_1") (pintype "passive"))
      (node (ref "R179") (pin "2") (pinfunction "2_2") (pintype "passive"))
      (node (ref "U7") (pin "15") (pinfunction "EN_15") (pintype "input"))
    )
    (net (code "178") (name "STR_BOOT") (class "Default")
      (node (ref "C140") (pin "1") (pinfunction "1_1") (pintype "passive"))
      (node (ref "U7") (pin "11") (pinfunction "BOOT_11") (pintype "passive"))
    )
    (net (code "179") (name "STR_COMP") (class "Default")
      (node (ref "C146") (pin "1") (pinfunction "1_1") (pintype "passive"))
      (node (ref "R181") (pin "2") (pinfunction "2_2") (pintype "passive"))
      (node (ref "U7") (pin "3") (pinfunction "COMP_3") (pintype "passive"))
    )
    (net (code "180") (name "STR_FB") (class "Default")
      (node (ref "R177") (pin "1") (pinfunction "1_1") (pintype "passive"))
      (node (ref "R185") (pin "2") (pinfunction "2_2") (pintype "passive"))
      (node (ref "U7") (pin "4") (pinfunction "FB_4") (pintype "input"))
    )
    (net (code "181") (name "STR_FEED") (class "Default")
      (node (ref "L12") (pin "2") (pinfunction "2_2") (pintype "passive"))
      (node (ref "R172") (pin "2") (pinfunction "2_2") (pintype "passive"))
      (node (ref "R44") (pin "2") (pinfunction "2_2") (pintype "passive"))
    )
    (net (code "182") (name "STR_HDRV") (class "Default")
      (node (ref "R178") (pin "2") (pinfunction "2_2") (pintype "passive"))
      (node (ref "U7") (pin "13") (pinfunction "HDRV_13") (pintype "output"))
    )
    (net (code "183") (name "STR_HG1") (class "Default")
      (node (ref "Q19") (pin "3") (pinfunction "TG_3") (pintype "passive"))
      (node (ref "R178") (pin "1") (pinfunction "1_1") (pintype "passive"))
    )
    (net (code "184") (name "STR_ISNS+") (class "Default")
      (node (ref "C138") (pin "1") (pinfunction "1_1") (pintype "passive"))
      (node (ref "R171") (pin "1") (pinfunction "1_1") (pintype "passive"))
      (node (ref "U7") (pin "6") (pinfunction "ISNS+_6") (pintype "input"))
    )
    (net (code "185") (name "STR_ISNS-") (class "Default")
      (node (ref "C138") (pin "2") (pinfunction "2_2") (pintype "passive"))
      (node (ref "R172") (pin "1") (pinfunction "1_1") (pintype "passive"))
      (node (ref "U7") (pin "5") (pinfunction "ISNS-_5") (pintype "input"))
    )
    (net (code "186") (name "STR_L") (class "Default")
      (node (ref "D22") (pin "A") (pinfunction "A_A") (pintype "passive"))
      (node (ref "L12") (pin "1") (pinfunction "1_1") (pintype "passive"))
      (node (ref "Q19") (pin "6") (pinfunction "VSW_6") (pintype "passive"))
      (node (ref "Q19") (pin "7") (pinfunction "VSW_7") (pintype "passive"))
      (node (ref "Q19") (pin "8") (pinfunction "VSW_8") (pintype "passive"))
    )
    (net (code "187") (name "STR_LDRV") (class "Default")
      (node (ref "R180") (pin "2") (pinfunction "2_2") (pintype "passive"))
      (node (ref "U7") (pin "8") (pinfunction "LDRV_8") (pintype "output"))
    )
    (net (code "188") (name "STR_LG1") (class "Default")
      (node (ref "Q19") (pin "5") (pinfunction "BG_5") (pintype "passive"))
      (node (ref "R180") (pin "1") (pinfunction "1_1") (pintype "passive"))
    )
    (net (code "189") (name "STR_PG") (class "Default")
      (node (ref "IC3") (pin "74") (pinfunction "RC14/SOSCO/CN0/RPI37_74") (pintype "bidirectional"))
      (node (ref "R186") (pin "1") (pinfunction "1_1") (pintype "passive"))
      (node (ref "U7") (pin "14") (pinfunction "PGOOD_14") (pintype "open_collector"))
    )
    (net (code "190") (name "STR_RC") (class "Default")
      (node (ref "C148") (pin "1") (pinfunction "1_1") (pintype "passive"))
      (node (ref "R181") (pin "1") (pinfunction "1_1") (pintype "passive"))
    )
    (net (code "191") (name "STR_RT") (class "Default")
      (node (ref "R182") (pin "2") (pinfunction "2_2") (pintype "passive"))
      (node (ref "U7") (pin "1") (pinfunction "RT/CLK_1") (pintype "passive"))
    )
    (net (code "192") (name "STR_SS") (class "Default")
      (node (ref "C147") (pin "1") (pinfunction "1_1") (pintype "passive"))
      (node (ref "U7") (pin "2") (pinfunction "SS_2") (pintype "passive"))
    )
    (net (code "193") (name "STR_SW") (class "Default")
      (node (ref "C140") (pin "2") (pinfunction "2_2") (pintype "passive"))
      (node (ref "Q19") (pin "4") (pinfunction "TGR_4") (pintype "passive"))
      (node (ref "U7") (pin "12") (pinfunction "SW_12") (pintype "output"))
    )
    (net (code "194") (name "STR_VCC") (class "Default")
      (node (ref "C141") (pin "1") (pinfunction "1_1") (pintype "passive"))
      (node (ref "U7") (pin "10") (pinfunction "VCC_10") (pintype "output"))
    )
    (net (code "195") (name "U1RX") (class "Default")
      (node (ref "IC18") (pin "1") (pinfunction "TXD_1") (pintype "output"))
      (node (ref "IC3") (pin "70") (pinfunction "CN55/RP3/RD10_70") (pintype "bidirectional"))
      (node (ref "J41") (pin "4") (pinfunction "4_4") (pintype "passive"))
    )
    (net (code "196") (name "U1TX") (class "Default")
      (node (ref "IC18") (pin "5") (pinfunction "RXD_5") (pintype "input"))
      (node (ref "IC3") (pin "71") (pinfunction "CN56/RP12/RD11_71") (pintype "bidirectional"))
      (node (ref "J41") (pin "5") (pinfunction "5_5") (pintype "passive"))
    )
    (net (code "197") (name "U2CTL") (class "Default")
      (node (ref "IC2") (pin "2") (pinfunction "/RE_2") (pintype "input"))
      (node (ref "IC2") (pin "3") (pinfunction "DE_3") (pintype "input"))
      (node (ref "IC3") (pin "19") (pinfunction "RPI34/CN67/RE9_19") (pintype "bidirectional"))
    )
    (net (code "198") (name "U2RX") (class "Default")
      (node (ref "IC2") (pin "1") (pinfunction "R_1") (pintype "output"))
      (node (ref "IC3") (pin "81") (pinfunction "CN13/RP25/RD4_81") (pintype "bidirectional"))
    )
    (net (code "199") (name "U2TX") (class "Default")
      (node (ref "IC2") (pin "4") (pinfunction "D_4") (pintype "input"))
      (node (ref "IC3") (pin "82") (pinfunction "CN14/RP20/RD5_82") (pintype "bidirectional"))
    )
    (net (code "200") (name "U3RX") (class "Default")
      (node (ref "IC3") (pin "23") (pinfunction "RB2/AN2/CN4/RP13_23") (pintype "bidirectional"))
      (node (ref "J2") (pin "3") (pinfunction "3_3") (pintype "passive"))
      (node (ref "JP1") (pin "3") (pinfunction "3_3") (pintype "passive"))
    )
    (net (code "201") (name "U3TX") (class "Default")
      (node (ref "IC3") (pin "33") (pinfunction "RB9/AN9/CN27/RP9_33") (pintype "bidirectional"))
      (node (ref "J2") (pin "4") (pinfunction "4_4") (pintype "passive"))
      (node (ref "JP1") (pin "4") (pinfunction "4_4") (pintype "passive"))
    )
    (net (code "202") (name "US-S_O") (class "Default")
      (node (ref "IC3") (pin "78") (pinfunction "CN52/RP22/RD3_78") (pintype "bidirectional"))
      (node (ref "J18") (pin "11") (pinfunction "11_11") (pintype "bidirectional"))
      (node (ref "J30") (pin "5") (pinfunction "SERIAL_5") (pintype "bidirectional"))
    )
    (net (code "203") (name "USRF_EN") (class "Default")
      (node (ref "IC3") (pin "97") (pinfunction "CN80/RG13_97") (pintype "bidirectional"))
      (node (ref "J18") (pin "12") (pinfunction "12_12") (pintype "bidirectional"))
      (node (ref "J30") (pin "4") (pinfunction "EN_4") (pintype "bidirectional"))
    )
    (net (code "204") (name "VACT") (class "Default")
      (node (ref "C142") (pin "1") (pinfunction "1_1") (pintype "passive"))
      (node (ref "C143") (pin "1") (pinfunction "1_1") (pintype "passive"))
      (node (ref "C144") (pin "1") (pinfunction "1_1") (pintype "passive"))
      (node (ref "C145") (pin "1") (pinfunction "1_1") (pintype "passive"))
      (node (ref "C43") (pin "+") (pinfunction "+_+") (pintype "passive"))
      (node (ref "D21") (pin "+") (pinfunction "C_+") (pintype "passive"))
      (node (ref "D22") (pin "K") (pinfunction "K_K") (pintype "passive"))
      (node (ref "D25") (pin "C") (pinfunction "K_C") (pintype "passive"))
      (node (ref "D26") (pin "C") (pinfunction "K_C") (pintype "passive"))
      (node (ref "J15") (pin "11") (pinfunction "11_11") (pintype "bidirectional"))
      (node (ref "J15") (pin "11A") (pinfunction "11_11A") (pintype "bidirectional"))
      (node (ref "J16") (pin "1") (pinfunction "1_1") (pintype "bidirectional"))
      (node (ref "J16") (pin "1A") (pinfunction "1_1A") (pintype "bidirectional"))
      (node (ref "J18") (pin "1") (pinfunction "1_1") (pintype "bidirectional"))
      (node (ref "Q19") (pin "1_2") (pinfunction "VIN_1_2") (pintype "passive"))
      (node (ref "R175") (pin "2") (pinfunction "2_2") (pintype "passive"))
      (node (ref "R176") (pin "2") (pinfunction "2_2") (pintype "passive"))
      (node (ref "R177") (pin "2") (pinfunction "2_2") (pintype "passive"))
      (node (ref "TP62") (pin "TP") (pinfunction "TP_TP") (pintype "input"))
    )
    (net (code "205") (name "VPS_ON") (class "Default")
      (node (ref "IC3") (pin "100") (pinfunction "CN62/RE4_100") (pintype "bidirectional"))
      (node (ref "Q2") (pin "5") (pinfunction "Q1G_5") (pintype "input"))
      (node (ref "R5") (pin "2") (pinfunction "2_2") (pintype "passive"))
    )
    (net (code "206") (name "VPS_PWR") (class "Default")
      (node (ref "J7") (pin "5") (pinfunction "5_5") (pintype "passive"))
      (node (ref "J9") (pin "5") (pinfunction "5_5") (pintype "passive"))
      (node (ref "Q2") (pin "2") (pinfunction "Q2D1_2") (pintype "bidirectional"))
      (node (ref "Q2") (pin "3") (pinfunction "Q2D2_3") (pintype "bidirectional"))
      (node (ref "R4") (pin "2") (pinfunction "2_2") (pintype "passive"))
    )
    (net (code "207") (name "VPS_SEN") (class "Default")
      (node (ref "IC3") (pin "99") (pinfunction "CN61/RE3_99") (pintype "bidirectional"))
      (node (ref "R4") (pin "1") (pinfunction "1_1") (pintype "passive"))
      (node (ref "R6") (pin "2") (pinfunction "2_2") (pintype "passive"))
    )
    (net (code "208") (name "VREF2.5") (class "Default")
      (node (ref "C4") (pin "1") (pinfunction "1_1") (pintype "passive"))
      (node (ref "IC1") (pin "2") (pinfunction "VOUT_2") (pintype "output"))
      (node (ref "IC3") (pin "29") (pinfunction "RA10/VR+/CN42_29") (pintype "bidirectional"))
      (node (ref "TP1") (pin "P$1") (pinfunction "TP_P$1") (pintype "passive"))
    )
    (net (code "209") (name "VSOLAR") (class "Default")
      (node (ref "J1") (pin "2") (pinfunction "2_2") (pintype "passive"))
    )
    (net (code "210") (name "XB_RTS") (class "Default")
      (node (ref "IC3") (pin "48") (pinfunction "CN21/RP5/RD15_48") (pintype "bidirectional"))
      (node (ref "J2") (pin "7") (pinfunction "7_7") (pintype "passive"))
    )
    (net (code "211") (name "XB_SLEEP") (class "Default")
      (node (ref "IC3") (pin "22") (pinfunction "RB3/AN3/CN5_22") (pintype "bidirectional"))
      (node (ref "J2") (pin "5") (pinfunction "5_5") (pintype "passive"))
      (node (ref "JP1") (pin "5") (pinfunction "5_5") (pintype "passive"))
    )
    (net (code "212") (name "unconnected-(B1-+-Pad+2)") (class "Default")
      (node (ref "B1") (pin "+2") (pinfunction "+_+2") (pintype "passive"))
    )
    (net (code "213") (name "unconnected-(IC3-CN15{slash}RD6-Pad83)") (class "Default")
      (node (ref "IC3") (pin "83") (pinfunction "CN15/RD6_83") (pintype "bidirectional"))
    )
    (net (code "214") (name "unconnected-(IC3-CN17{slash}RP10{slash}RF4-Pad49)") (class "Default")
      (node (ref "IC3") (pin "49") (pinfunction "CN17/RP10/RF4_49") (pintype "bidirectional"))
    )
    (net (code "215") (name "unconnected-(IC3-CN58{slash}RE0-Pad93)") (class "Default")
      (node (ref "IC3") (pin "93") (pinfunction "CN58/RE0_93") (pintype "bidirectional"))
    )
    (net (code "216") (name "unconnected-(IC3-CN60{slash}RE2-Pad98)") (class "Default")
      (node (ref "IC3") (pin "98") (pinfunction "CN60/RE2_98") (pintype "bidirectional"))
    )
    (net (code "217") (name "unconnected-(IC3-CN69{slash}RF1-Pad88)") (class "Default")
      (node (ref "IC3") (pin "88") (pinfunction "CN69/RF1_88") (pintype "bidirectional"))
    )
    (net (code "218") (name "unconnected-(IC3-CN73{slash}RPI44{slash}RF7-Pad54)") (class "Default")
      (node (ref "IC3") (pin "54") (pinfunction "CN73/RPI44/RF7_54") (pintype "bidirectional"))
    )
    (net (code "219") (name "unconnected-(IC3-CN76{slash}RP31{slash}RF13-Pad39)") (class "Default")
      (node (ref "IC3") (pin "39") (pinfunction "CN76/RP31/RF13_39") (pintype "bidirectional"))
    )
    (net (code "220") (name "unconnected-(IC3-RA2{slash}SCL2-Pad58)") (class "Default")
      (node (ref "IC3") (pin "58") (pinfunction "RA2/SCL2_58") (pintype "bidirectional"))
    )
    (net (code "221") (name "unconnected-(IC3-RA3{slash}SDA2-Pad59)") (class "Default")
      (node (ref "IC3") (pin "59") (pinfunction "RA3/SDA2_59") (pintype "bidirectional"))
    )
    (net (code "222") (name "unconnected-(IC3-RB8{slash}AN8{slash}CN26{slash}RP8-Pad32)") (class "Default")
      (node (ref "IC3") (pin "32") (pinfunction "RB8/AN8/CN26/RP8_32") (pintype "bidirectional"))
    )
    (net (code "223") (name "unconnected-(IC3-RB11{slash}AN11{slash}CN29-Pad35)") (class "Default")
      (node (ref "IC3") (pin "35") (pinfunction "RB11/AN11/CN29_35") (pintype "bidirectional"))
    )
    (net (code "224") (name "unconnected-(IC3-RB15{slash}AN15{slash}CN12{slash}RP29-Pad44)") (class "Default")
      (node (ref "IC3") (pin "44") (pinfunction "RB15/AN15/CN12/RP29_44") (pintype "bidirectional"))
    )
    (net (code "225") (name "unconnected-(IC5-OS-Pad3)") (class "Default")
      (node (ref "IC5") (pin "3") (pinfunction "OS_3") (pintype "output"))
    )
    (net (code "226") (name "unconnected-(IC7-CLKOUT-Pad13)") (class "Default")
      (node (ref "IC7") (pin "13") (pinfunction "CLKOUT_13") (pintype "output"))
    )
    (net (code "227") (name "unconnected-(IC7-TEST-Pad4)") (class "Default")
      (node (ref "IC7") (pin "4") (pinfunction "TEST_4") (pintype "output"))
    )
    (net (code "228") (name "unconnected-(IC18-AVCC-NC-Pad24)") (class "Default")
      (node (ref "IC18") (pin "24") (pinfunction "AVCC-NC_24") (pintype "no_connect"))
    )
    (net (code "229") (name "unconnected-(IC18-GPIO2-Pad13)") (class "Default")
      (node (ref "IC18") (pin "13") (pinfunction "GPIO2_13") (pintype "output"))
    )
    (net (code "230") (name "unconnected-(IC18-GPIO3-Pad14)") (class "Default")
      (node (ref "IC18") (pin "14") (pinfunction "GPIO3_14") (pintype "bidirectional"))
    )
    (net (code "231") (name "unconnected-(IC18-OSCI-Pad27)") (class "Default")
      (node (ref "IC18") (pin "27") (pinfunction "OSCI_27") (pintype "bidirectional"))
    )
    (net (code "232") (name "unconnected-(IC18-OSCO-Pad28)") (class "Default")
      (node (ref "IC18") (pin "28") (pinfunction "OSCO_28") (pintype "output"))
    )
    (net (code "233") (name "unconnected-(IC18-VCC3I-NC-Pad8)") (class "Default")
      (node (ref "IC18") (pin "8") (pinfunction "VCC3I-NC_8") (pintype "no_connect"))
    )
    (net (code "234") (name "unconnected-(IC18-{slash}DCD-Pad10)") (class "Default")
      (node (ref "IC18") (pin "10") (pinfunction "/DCD_10") (pintype "bidirectional"))
    )
    (net (code "235") (name "unconnected-(IC18-{slash}DSR-Pad9)") (class "Default")
      (node (ref "IC18") (pin "9") (pinfunction "/DSR_9") (pintype "bidirectional"))
    )
    (net (code "236") (name "unconnected-(IC18-{slash}DTR-Pad2)") (class "Default")
      (node (ref "IC18") (pin "2") (pinfunction "/DTR_2") (pintype "output"))
    )
    (net (code "237") (name "unconnected-(IC18-{slash}RI-Pad6)") (class "Default")
      (node (ref "IC18") (pin "6") (pinfunction "/RI_6") (pintype "bidirectional"))
    )
    (net (code "238") (name "unconnected-(IC18-{slash}SLEEP-Pad12)") (class "Default")
      (node (ref "IC18") (pin "12") (pinfunction "/SLEEP_12") (pintype "bidirectional"))
    )
    (net (code "239") (name "unconnected-(J8-Pad1)") (class "Default")
      (node (ref "J8") (pin "1") (pinfunction "1_1") (pintype "passive"))
    )
    (net (code "240") (name "unconnected-(J8-Pad2)") (class "Default")
      (node (ref "J8") (pin "2") (pinfunction "2_2") (pintype "passive"))
    )
    (net (code "241") (name "unconnected-(J8-Pad3)") (class "Default")
      (node (ref "J8") (pin "3") (pinfunction "3_3") (pintype "passive"))
    )
    (net (code "242") (name "unconnected-(J8-Pad4)") (class "Default")
      (node (ref "J8") (pin "4") (pinfunction "4_4") (pintype "passive"))
    )
    (net (code "243") (name "unconnected-(J8-Pad5)") (class "Default")
      (node (ref "J8") (pin "5") (pinfunction "5_5") (pintype "passive"))
    )
    (net (code "244") (name "unconnected-(J8-Pad6)") (class "Default")
      (node (ref "J8") (pin "6") (pinfunction "6_6") (pintype "passive"))
    )
    (net (code "245") (name "unconnected-(J8-Pad7)") (class "Default")
      (node (ref "J8") (pin "7") (pinfunction "7_7") (pintype "passive"))
    )
    (net (code "246") (name "unconnected-(J8-Pad8)") (class "Default")
      (node (ref "J8") (pin "8") (pinfunction "8_8") (pintype "passive"))
    )
    (net (code "247") (name "unconnected-(J10-PadC4)") (class "Default")
      (node (ref "J10") (pin "C4") (pinfunction "C4_C4") (pintype "bidirectional"))
    )
    (net (code "248") (name "unconnected-(J10-PadC6)") (class "Default")
      (node (ref "J10") (pin "C6") (pinfunction "C6_C6") (pintype "bidirectional"))
    )
    (net (code "249") (name "unconnected-(J10-PadC8)") (class "Default")
      (node (ref "J10") (pin "C8") (pinfunction "C8_C8") (pintype "bidirectional"))
    )
    (net (code "250") (name "unconnected-(J30-AN{slash}O-Pad3)") (class "Default")
      (node (ref "J30") (pin "3") (pinfunction "AN/O_3") (pintype "bidirectional"))
    )
    (net (code "251") (name "unconnected-(J30-PWM-Pad2)") (class "Default")
      (node (ref "J30") (pin "2") (pinfunction "PWM_2") (pintype "bidirectional"))
    )
    (net (code "252") (name "unconnected-(J30-TEMP(NC)-Pad1)") (class "Default")
      (node (ref "J30") (pin "1") (pinfunction "TEMP(NC)_1") (pintype "bidirectional"))
    )
    (net (code "253") (name "unconnected-(J47-Pad7)") (class "Default")
      (node (ref "J47") (pin "7") (pinfunction "7_7") (pintype "passive"))
    )
    (net (code "254") (name "unconnected-(J47-Pad8)") (class "Default")
      (node (ref "J47") (pin "8") (pinfunction "8_8") (pintype "passive"))
    )
    (net (code "255") (name "unconnected-(J47-Pad9)") (class "Default")
      (node (ref "J47") (pin "9") (pinfunction "9_9") (pintype "passive"))
    )
    (net (code "256") (name "unconnected-(J47-Pad10)") (class "Default")
      (node (ref "J47") (pin "10") (pinfunction "10_10") (pintype "passive"))
    )
    (net (code "257") (name "unconnected-(JP1-Pad8)") (class "Default")
      (node (ref "JP1") (pin "8") (pinfunction "8_8") (pintype "passive"))
    )
    (net (code "258") (name "unconnected-(Q3-Pad4)") (class "Default")
      (node (ref "Q3") (pin "4") (pinfunction "4_4") (pintype "passive"))
    )
    (net (code "259") (name "unconnected-(U1-NC-Pad16)") (class "Default")
      (node (ref "U1") (pin "16") (pinfunction "NC_16") (pintype "bidirectional"))
    )
    (net (code "260") (name "unconnected-(U3-ALERT{slash}RDY-Pad2)") (class "Default")
      (node (ref "U3") (pin "2") (pinfunction "ALERT/RDY_2") (pintype "bidirectional"))
    )
    (net (code "261") (name "unconnected-(U8-NC-Pad13)") (class "Default")
      (node (ref "U8") (pin "13") (pinfunction "NC_13") (pintype "no_connect"))
    )
    (net (code "262") (name "unconnected-(X1F-1-Pad5)") (class "Default")
      (node (ref "X1") (pin "5") (pinfunction "1_5") (pintype "passive"))
    )
    (net (code "263") (name "{slash}3.3V1_ON") (class "Default")
      (node (ref "IC3") (pin "95") (pinfunction "CN81/RG14_95") (pintype "bidirectional"))
      (node (ref "Q7") (pin "2") (pinfunction "G_2") (pintype "passive"))
    )
    (net (code "264") (name "{slash}3.3V2_ON") (class "Default")
      (node (ref "IC3") (pin "94") (pinfunction "CN59/RE1_94") (pintype "bidirectional"))
      (node (ref "Q7") (pin "5") (pinfunction "G_5") (pintype "passive"))
    )
    (net (code "265") (name "{slash}3.3V3_ON") (class "Default")
      (node (ref "IC3") (pin "61") (pinfunction "RA5/TDO/CN38_61") (pintype "bidirectional"))
    )
    (net (code "266") (name "{slash}CL_CS1") (class "Default")
      (node (ref "IC3") (pin "1") (pinfunction "CN82/RG15_1") (pintype "bidirectional"))
      (node (ref "TP10") (pin "P$1") (pinfunction "TP_P$1") (pintype "passive"))
    )
    (net (code "267") (name "{slash}CL_CS2") (class "Default")
      (node (ref "IC3") (pin "17") (pinfunction "RA0/TMS_17") (pintype "bidirectional"))
      (node (ref "J1") (pin "7") (pinfunction "7_7") (pintype "passive"))
    )
    (net (code "268") (name "{slash}CTS") (class "Default")
      (node (ref "IC18") (pin "11") (pinfunction "/CTS_11") (pintype "bidirectional"))
      (node (ref "J41") (pin "2") (pinfunction "2_2") (pintype "passive"))
    )
    (net (code "269") (name "{slash}FMEM1_CS") (class "Default")
      (node (ref "IC3") (pin "28") (pinfunction "RA9/VR-/CN41_28") (pintype "bidirectional"))
      (node (ref "IC8") (pin "1") (pinfunction "/S_1") (pintype "input"))
      (node (ref "R24") (pin "2") (pinfunction "2_2") (pintype "passive"))
    )
    (net (code "270") (name "{slash}MCLR") (class "Default")
      (node (ref "IC3") (pin "13") (pinfunction "MCLR_13") (pintype "input"))
      (node (ref "IC4") (pin "4") (pinfunction "GP2/T0CK_4") (pintype "bidirectional"))
      (node (ref "J11") (pin "1") (pinfunction "1_1") (pintype "passive"))
      (node (ref "R14") (pin "1") (pinfunction "1_1") (pintype "passive"))
    )
    (net (code "271") (name "{slash}MCLR2") (class "Default")
      (node (ref "IC4") (pin "6") (pinfunction "GP3/MCLR_6") (pintype "bidirectional"))
      (node (ref "J12") (pin "1") (pinfunction "1_1") (pintype "passive"))
    )
    (net (code "272") (name "{slash}RAM_CS") (class "Default")
      (node (ref "IC3") (pin "3") (pinfunction "CN63/RE5_3") (pintype "bidirectional"))
      (node (ref "J8") (pin "13") (pinfunction "13_13") (pintype "passive"))
    )
    (net (code "273") (name "{slash}RTS") (class "Default")
      (node (ref "IC18") (pin "3") (pinfunction "/RTS_3") (pintype "output"))
      (node (ref "J41") (pin "6") (pinfunction "6_6") (pintype "passive"))
    )
    (net (code "274") (name "{slash}SM_FAULT") (class "Default")
      (node (ref "IC3") (pin "21") (pinfunction "RB4/AN4/CN6/RP28_21") (pintype "bidirectional"))
      (node (ref "U1") (pin "24") (pinfunction "-FAULT_24") (pintype "bidirectional"))
    )
    (net (code "275") (name "{slash}XB_RESET") (class "Default")
      (node (ref "IC3") (pin "18") (pinfunction "RPI33/CN66/RE8_18") (pintype "bidirectional"))
      (node (ref "J2") (pin "6") (pinfunction "6_6") (pintype "passive"))
      (node (ref "JP1") (pin "7") (pinfunction "7_7") (pintype "passive"))
    )
  )
)
